# tc08-6u.net
KiCad netlist of a schematic drawn in EAGLE
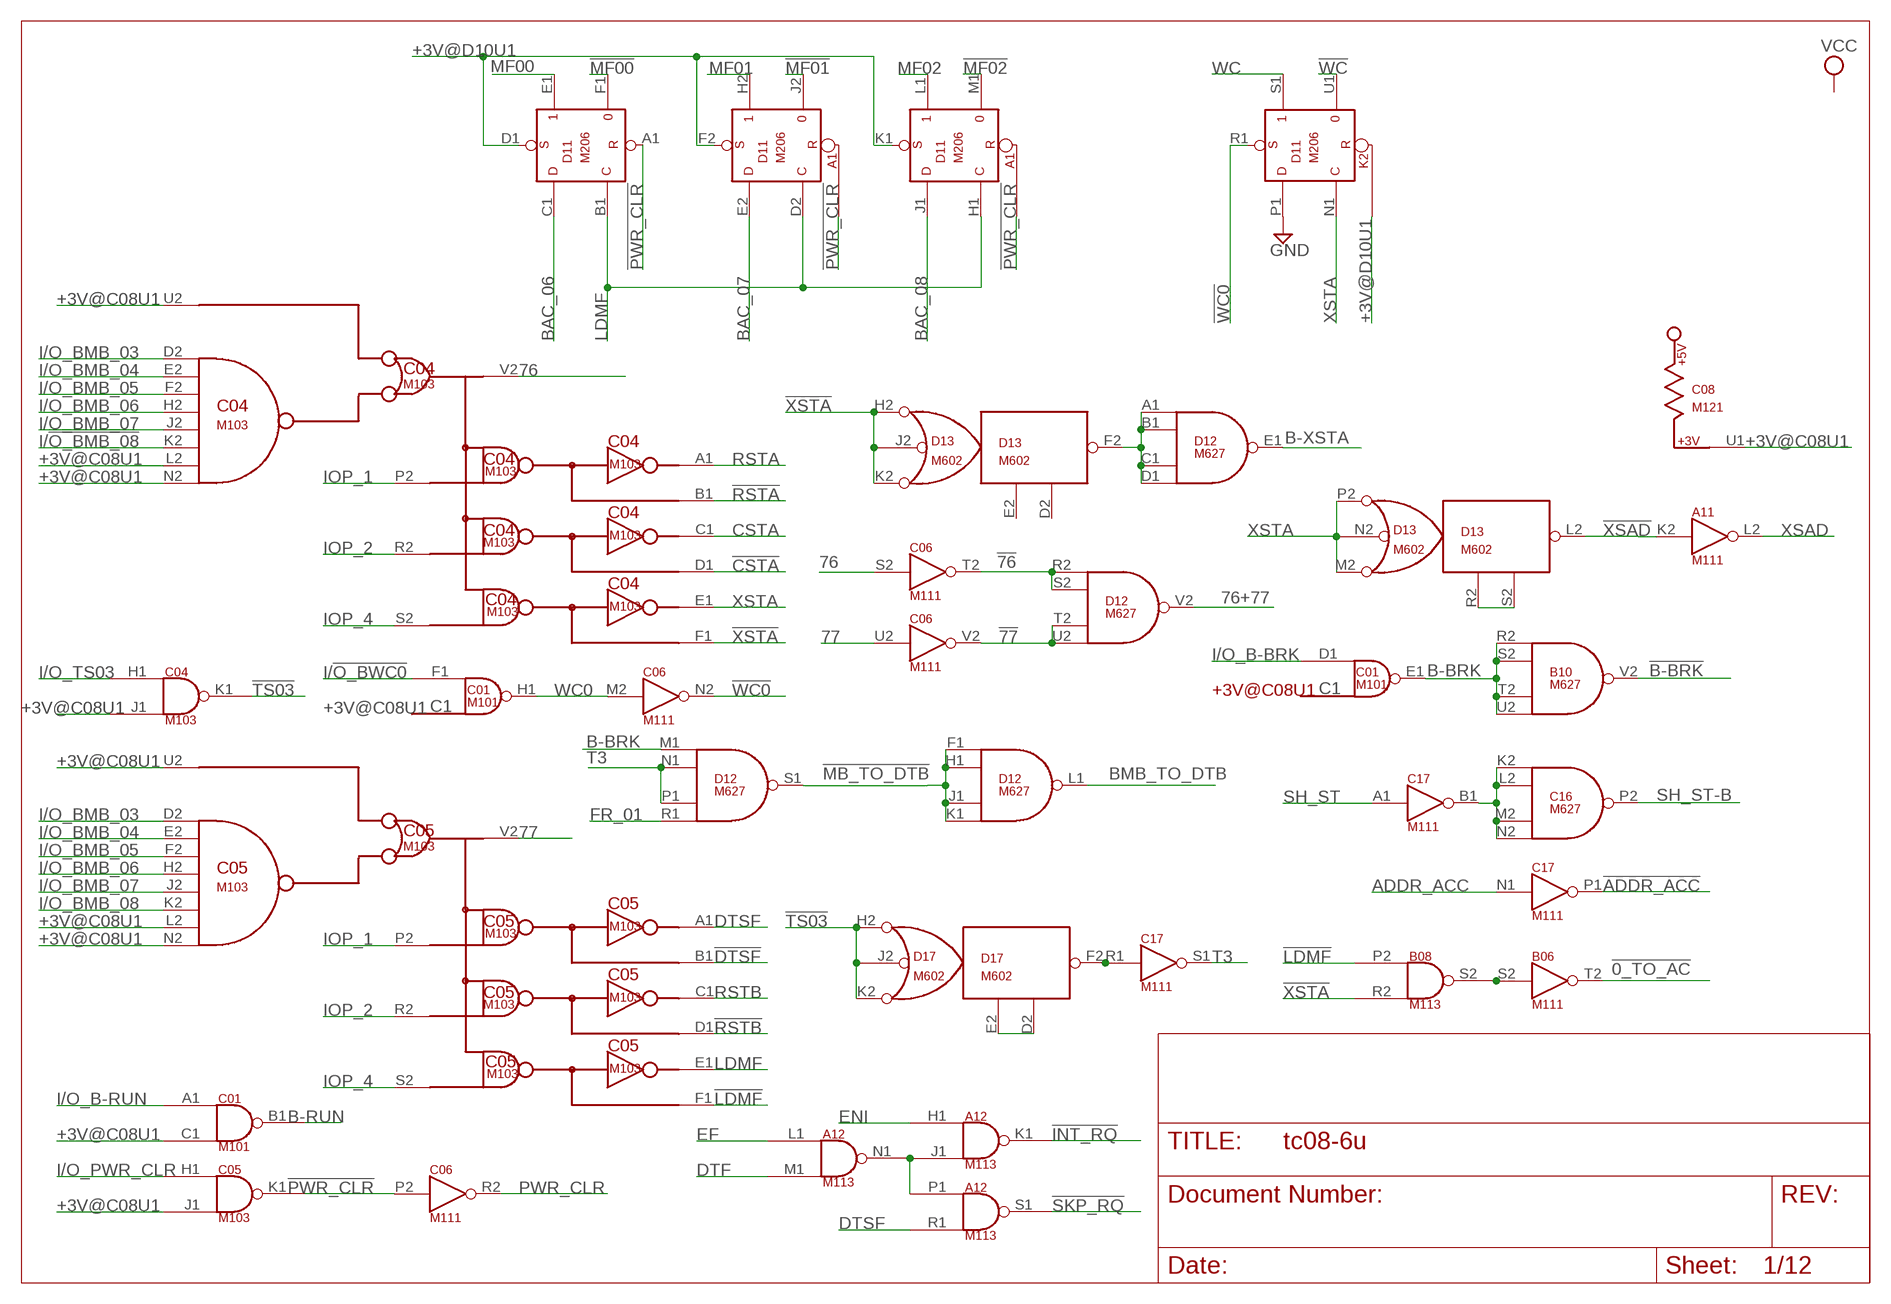
[diagram p0: schematic, sheet 1]
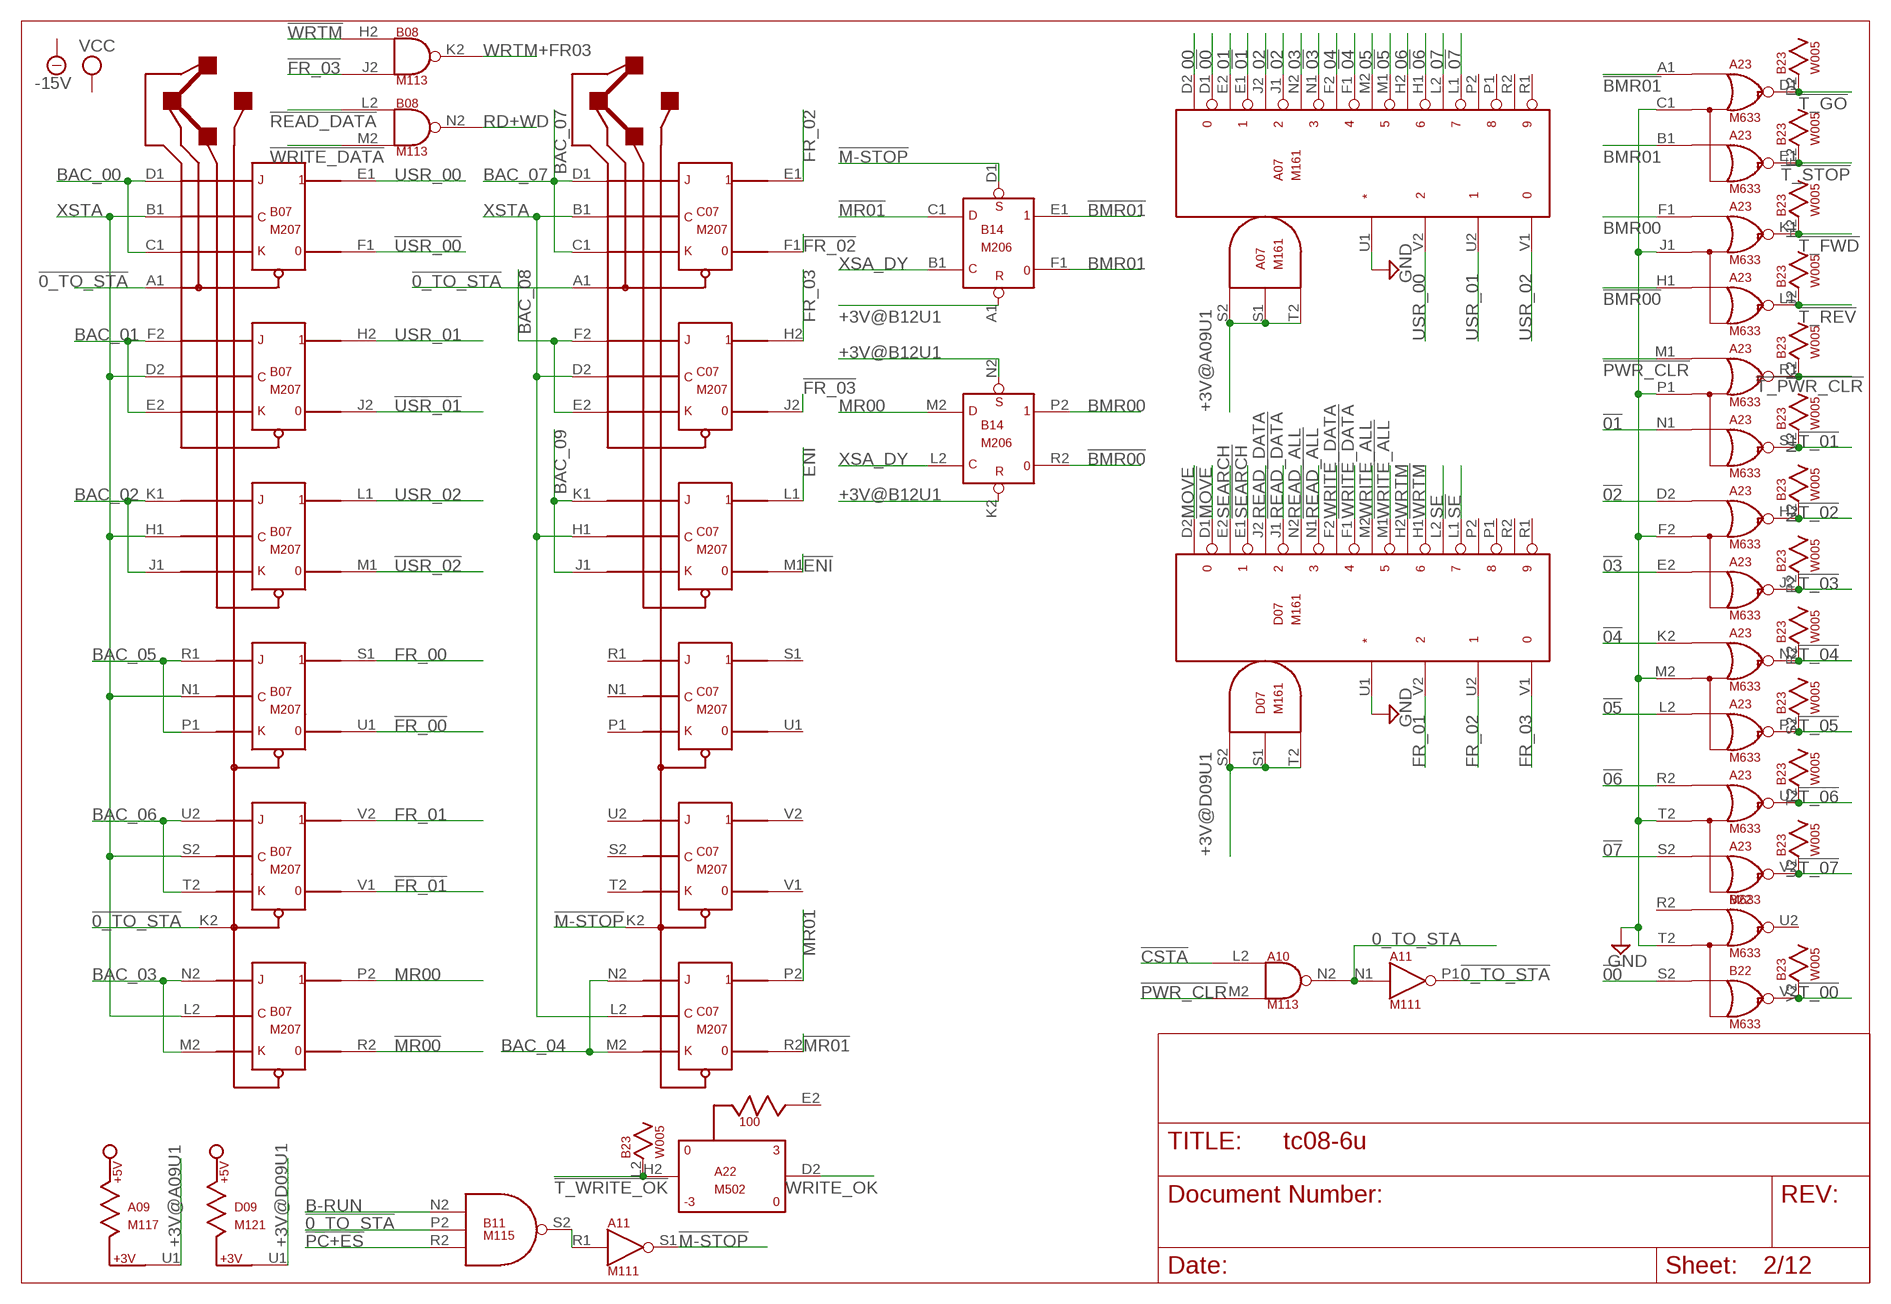
[diagram p1: schematic, sheet 2]
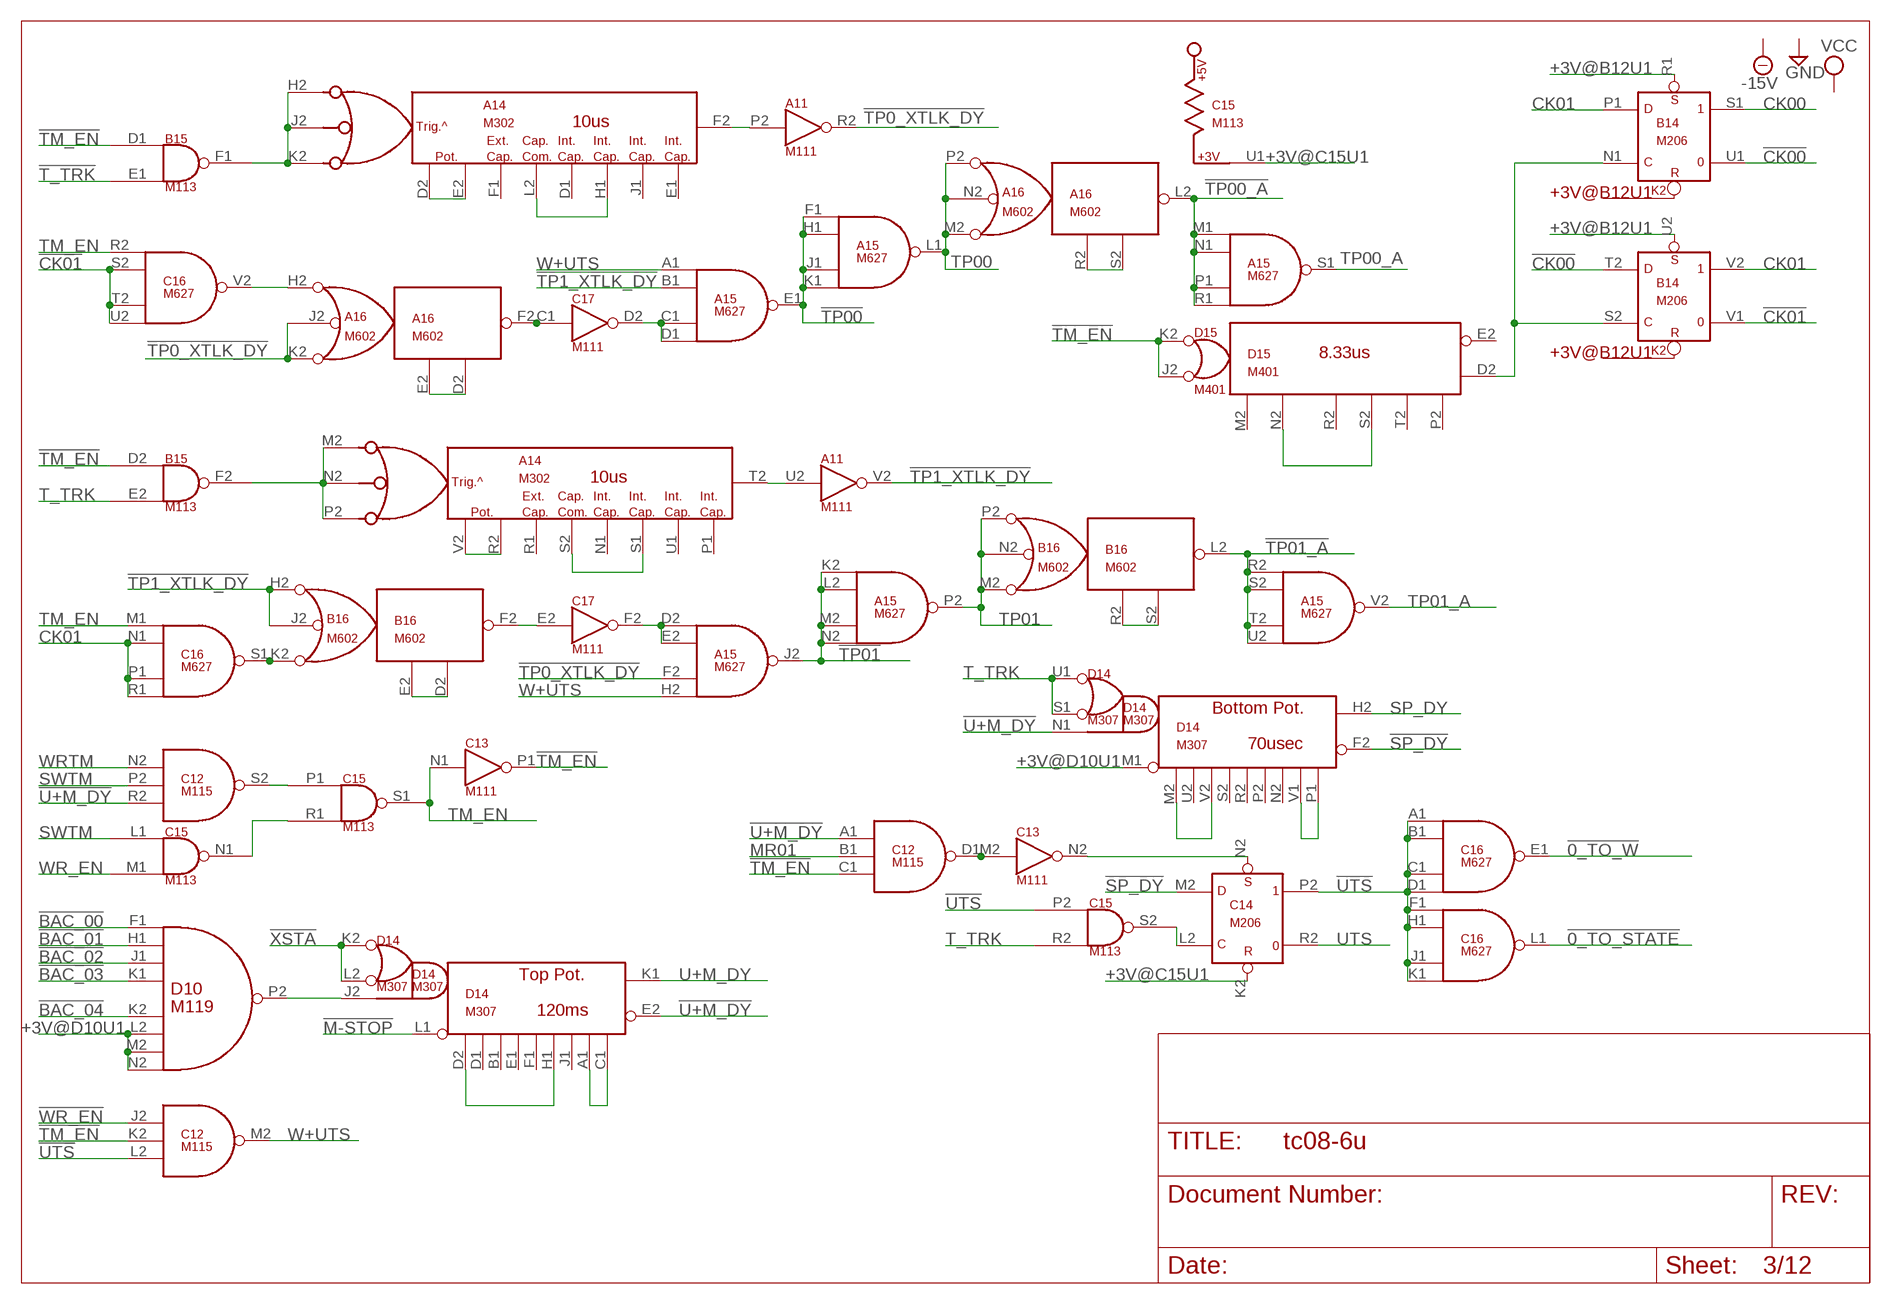
[diagram p2: schematic, sheet 3]
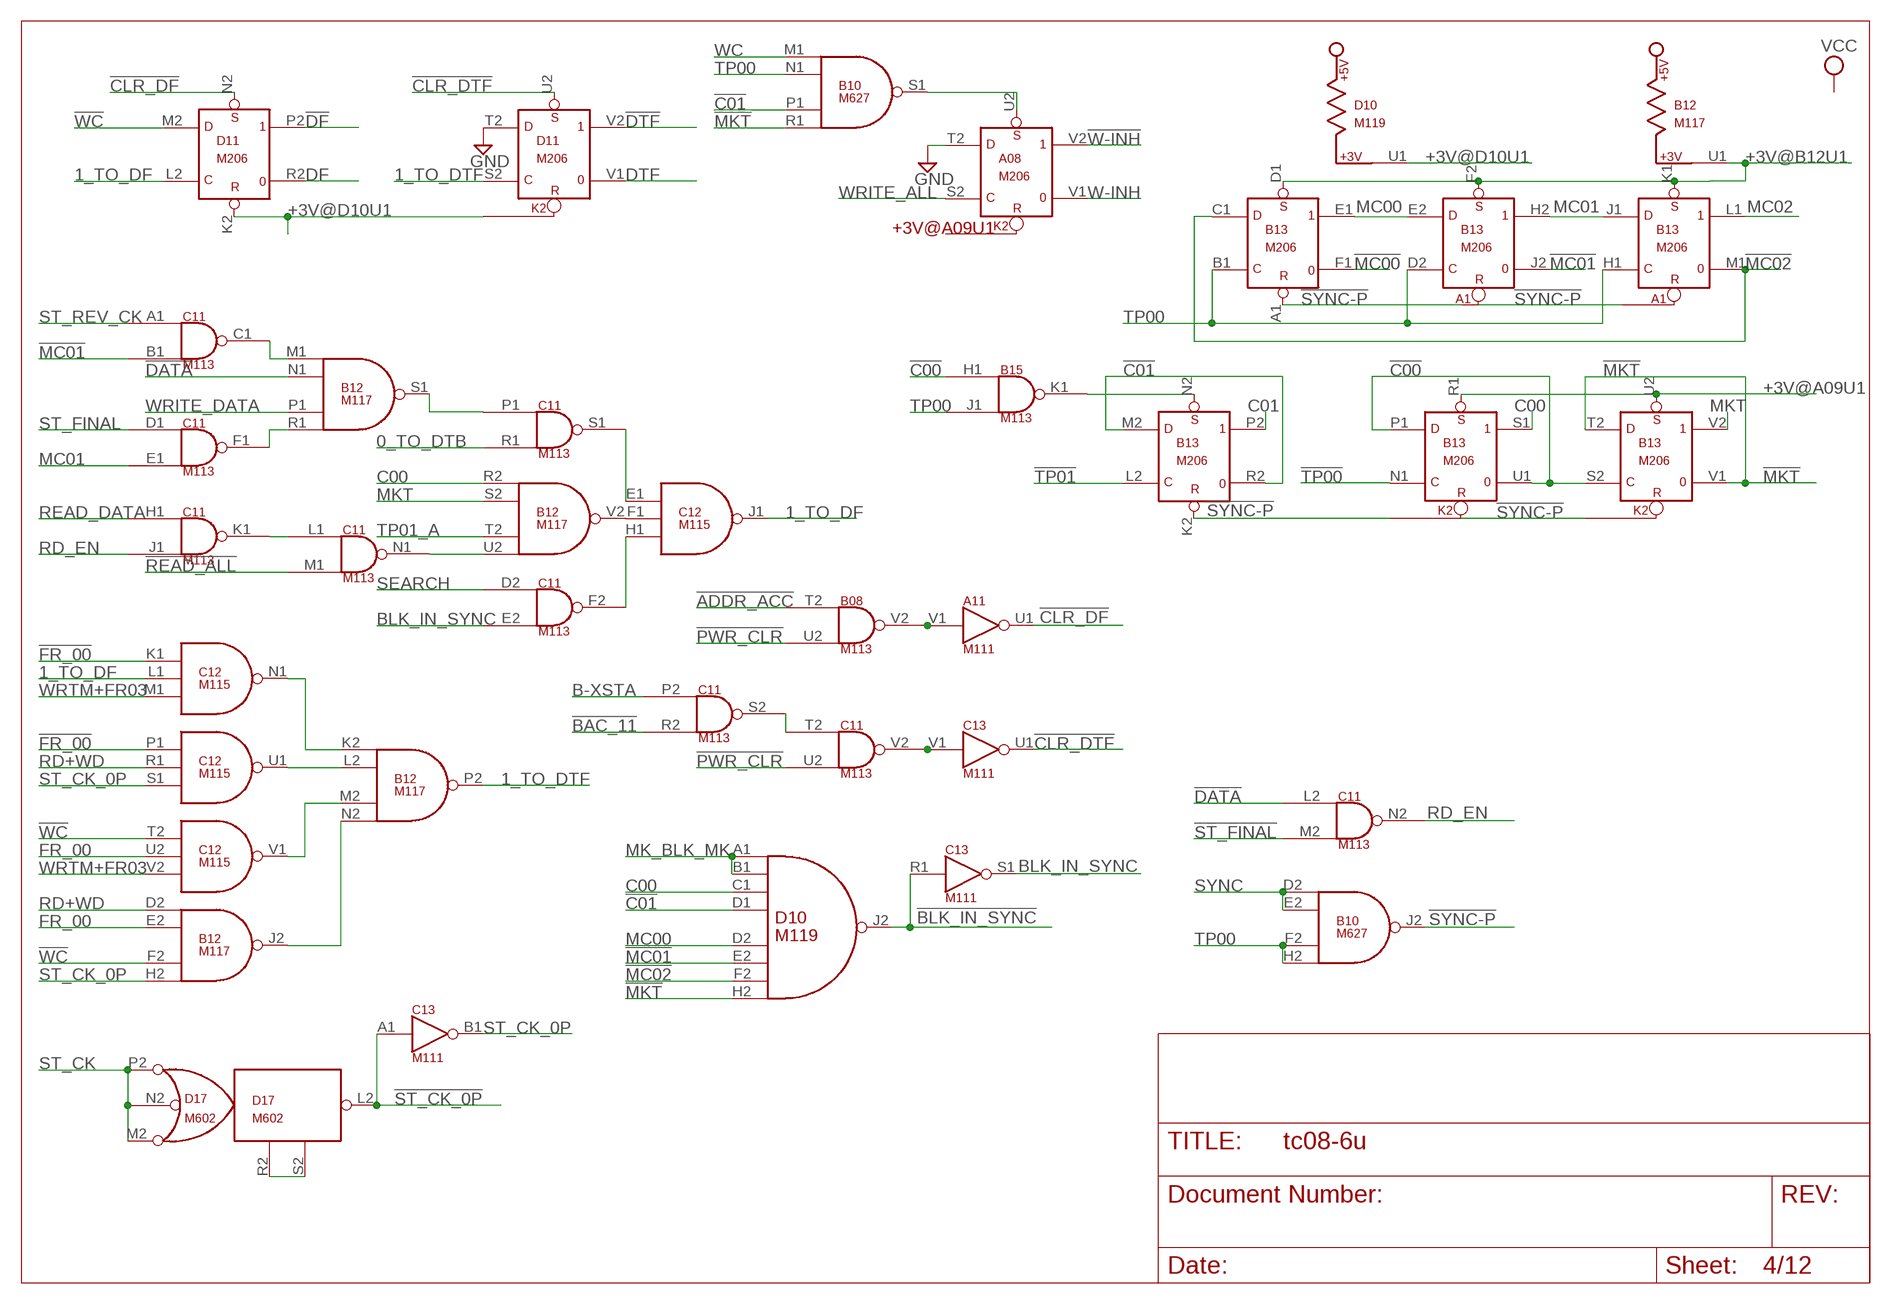
[diagram p3: schematic, sheet 4]
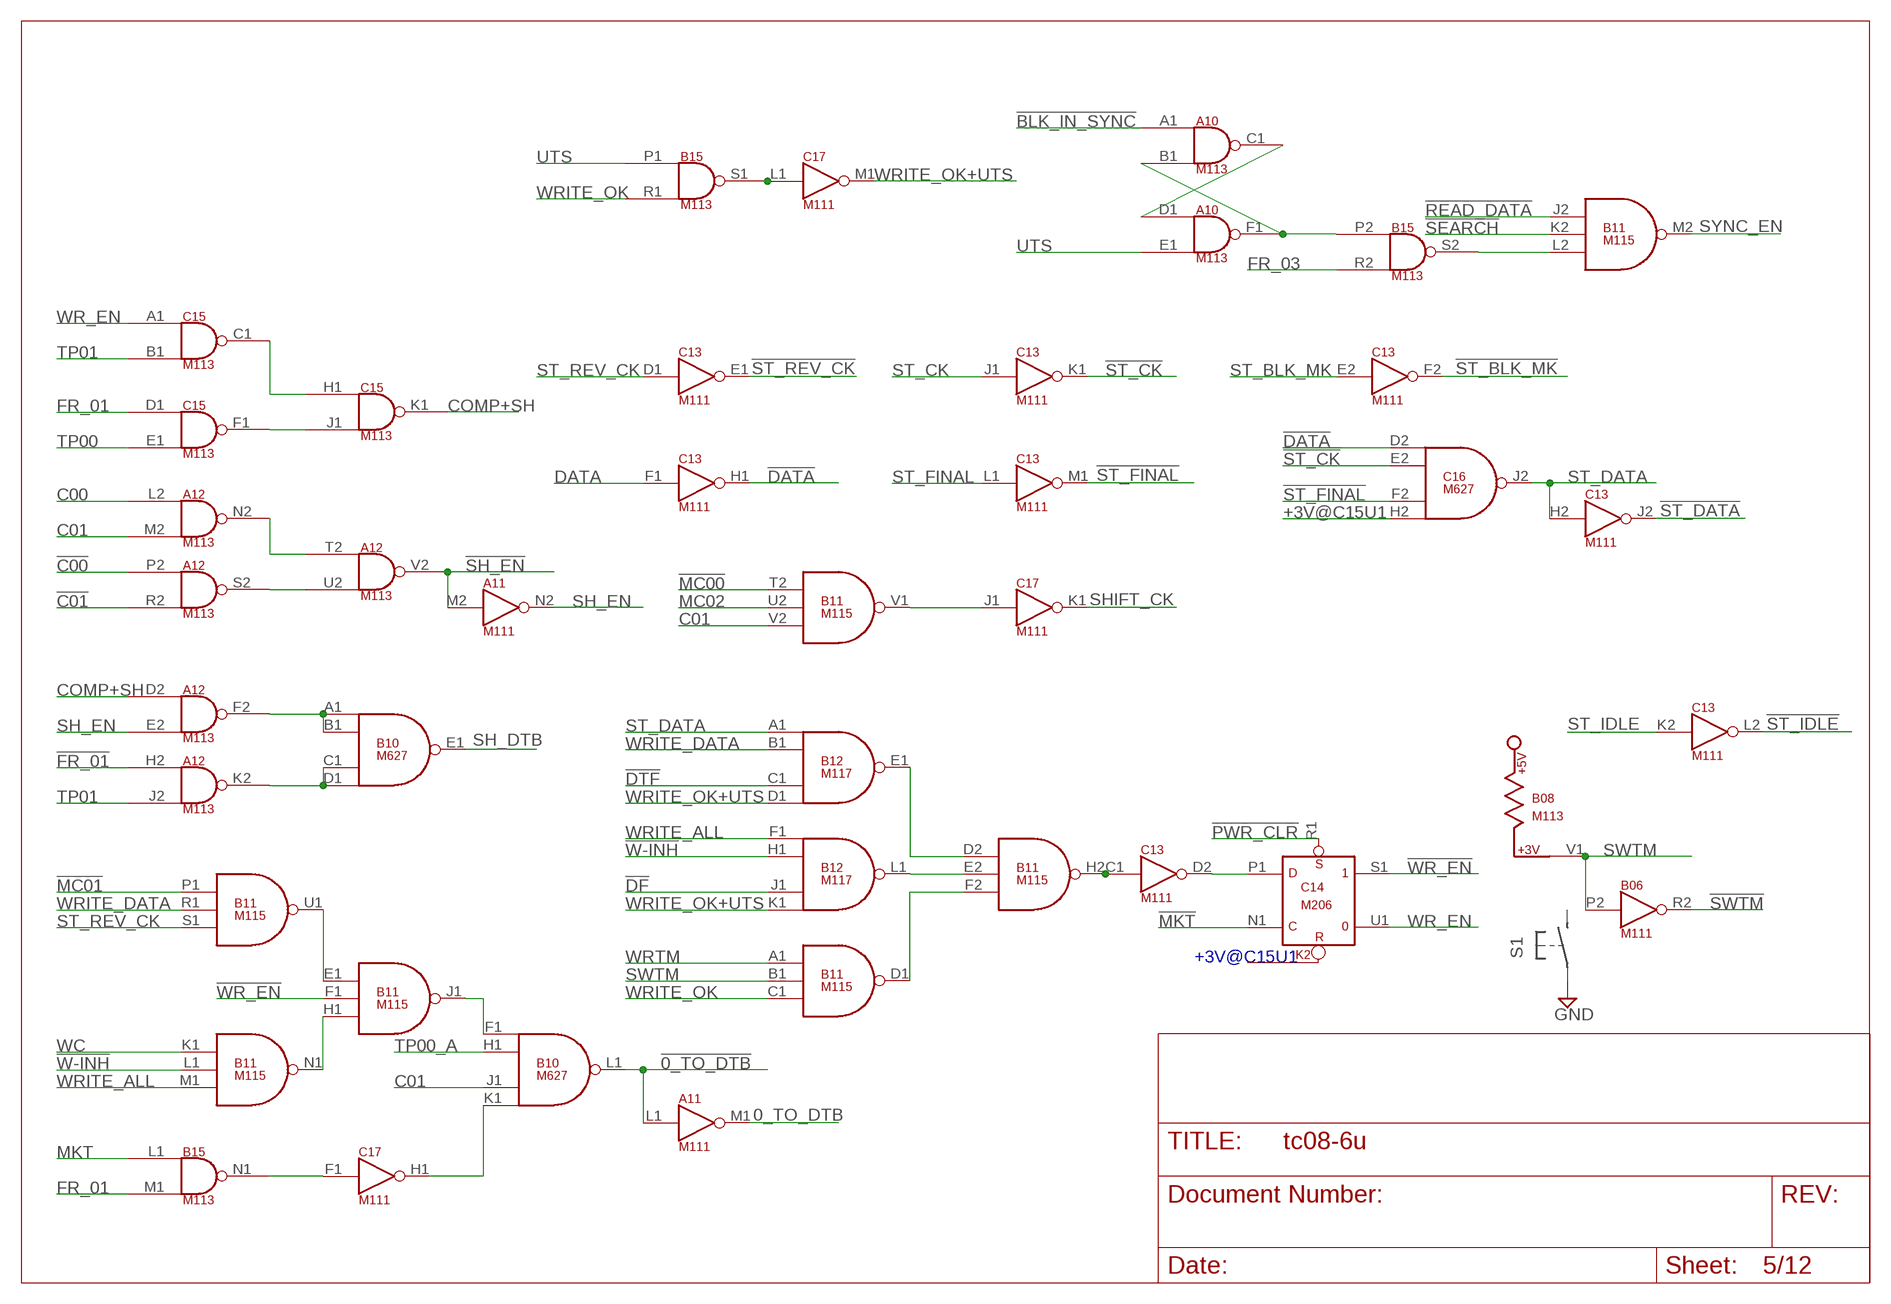
[diagram p4: schematic, sheet 5]
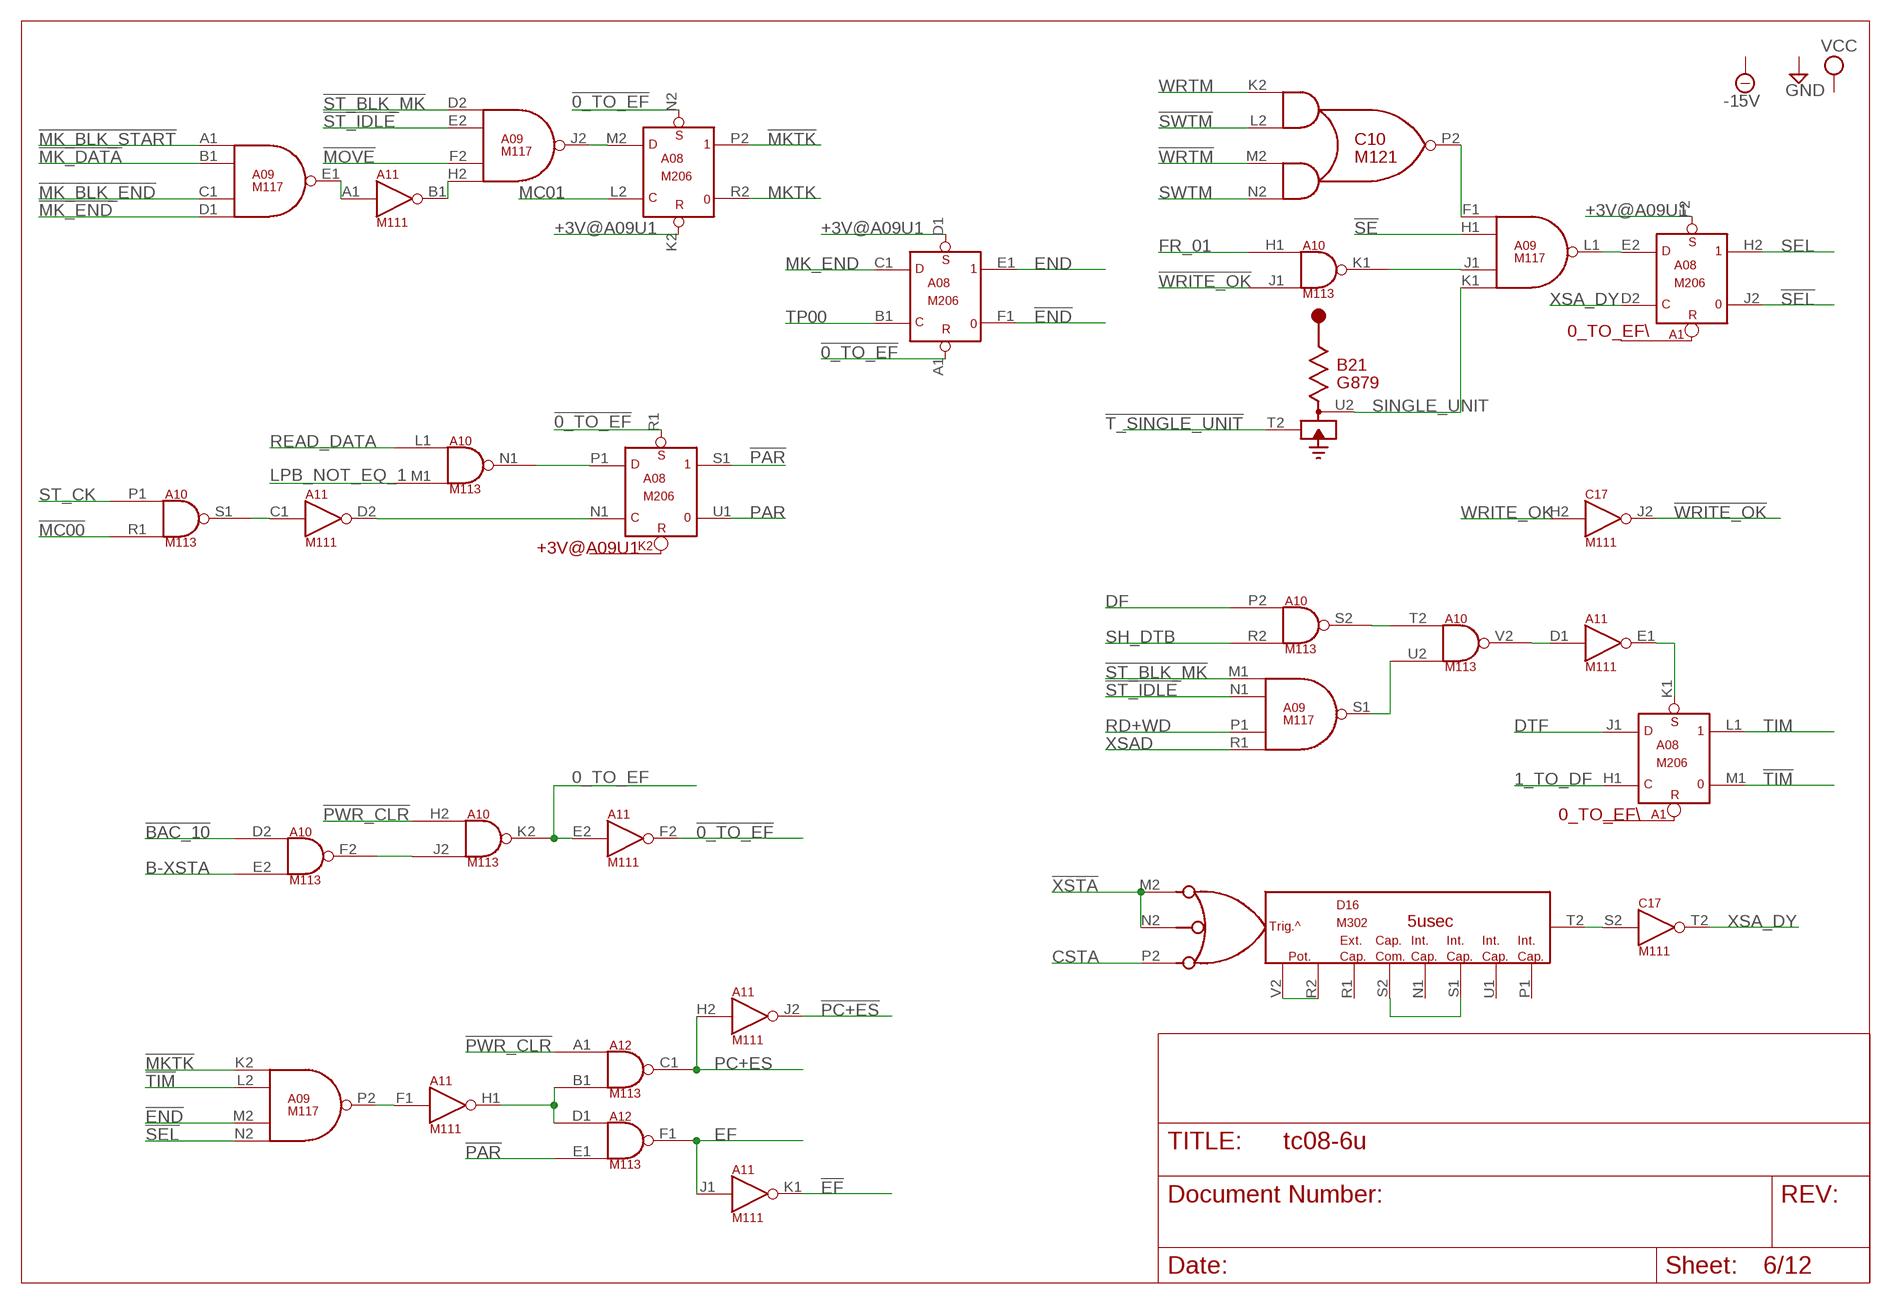
[diagram p5: schematic, sheet 6]
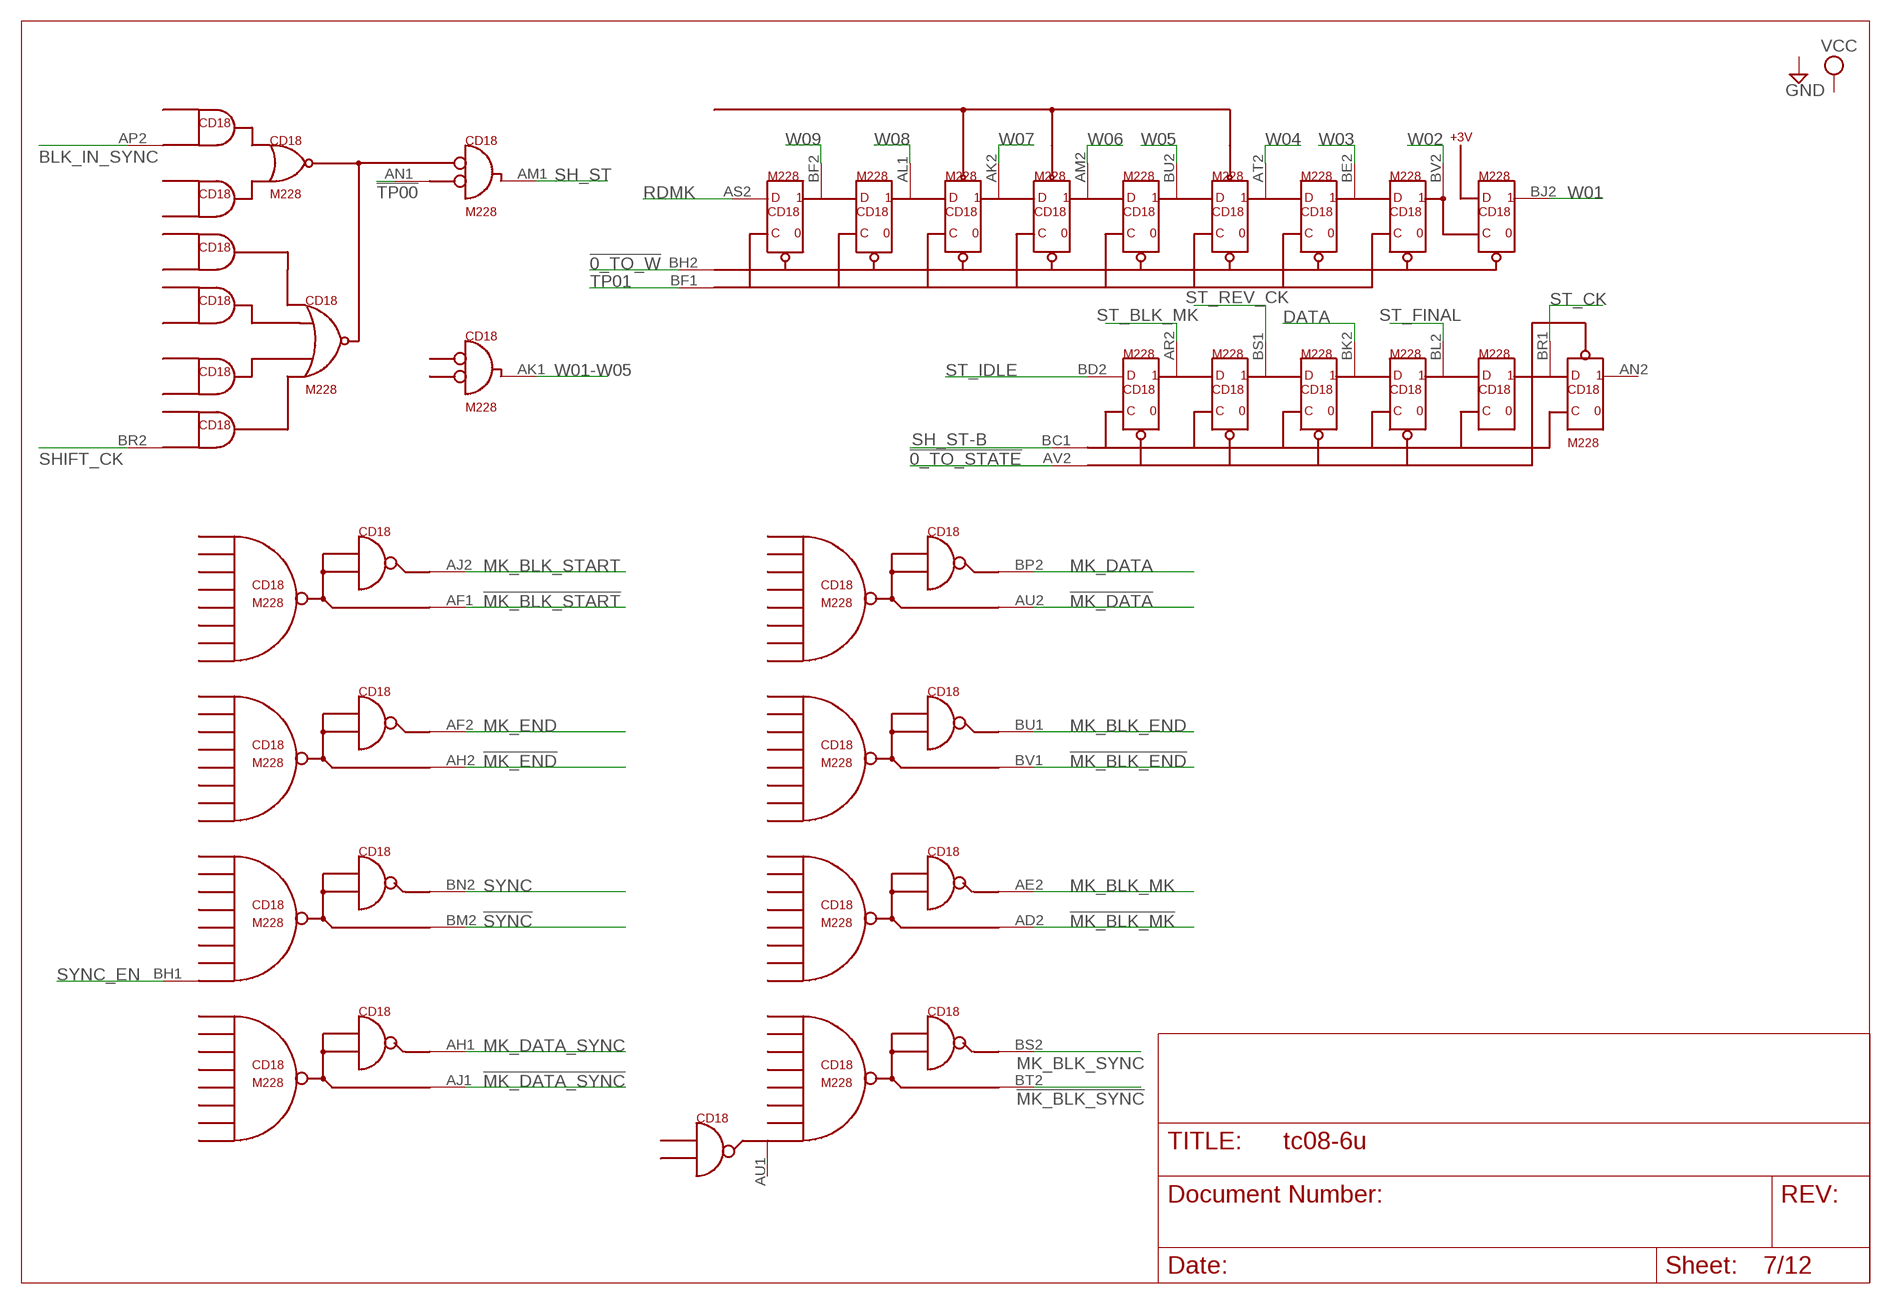
[diagram p6: schematic, sheet 7]
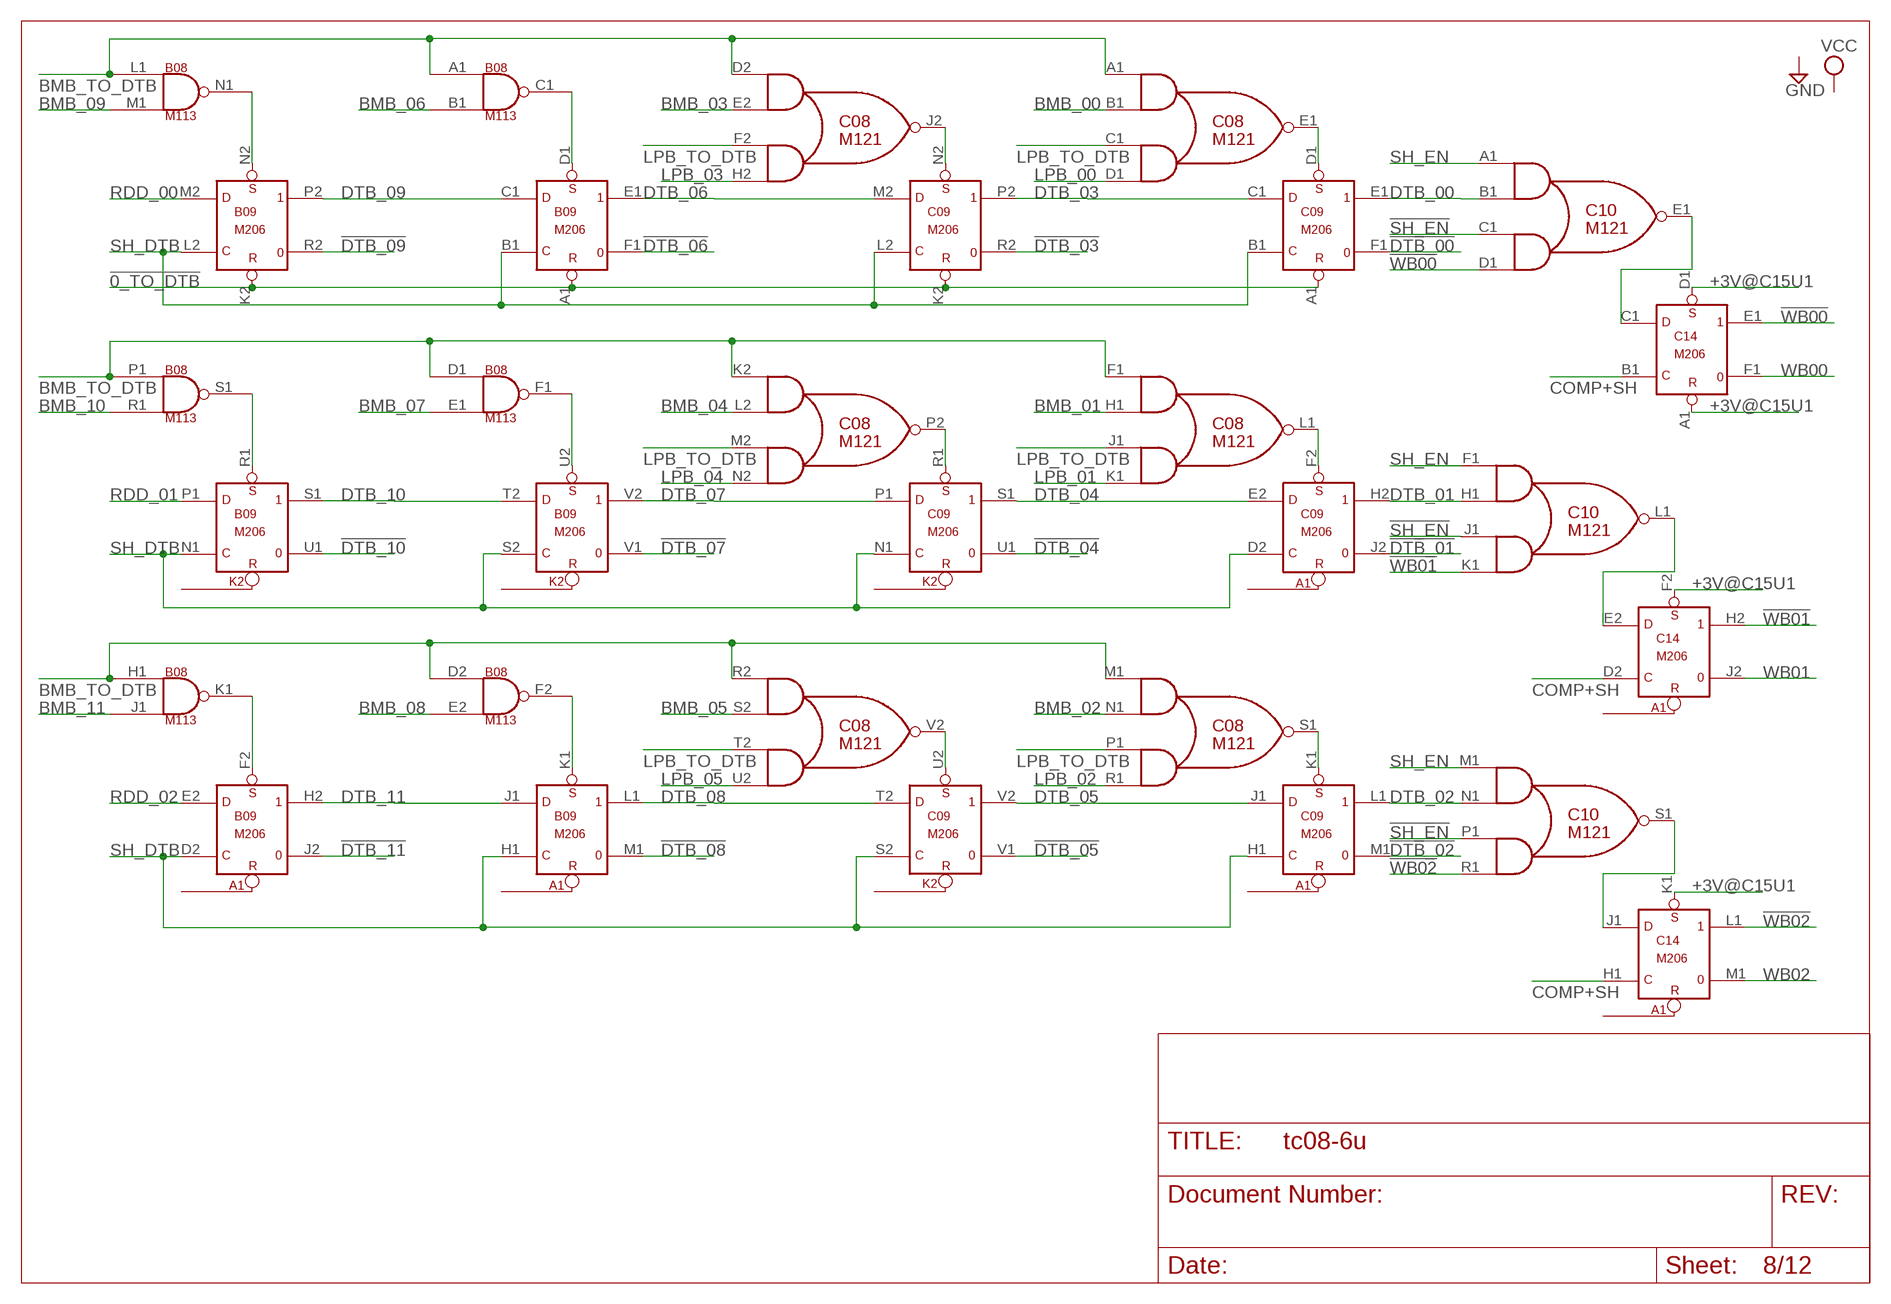
[diagram p7: schematic, sheet 8]
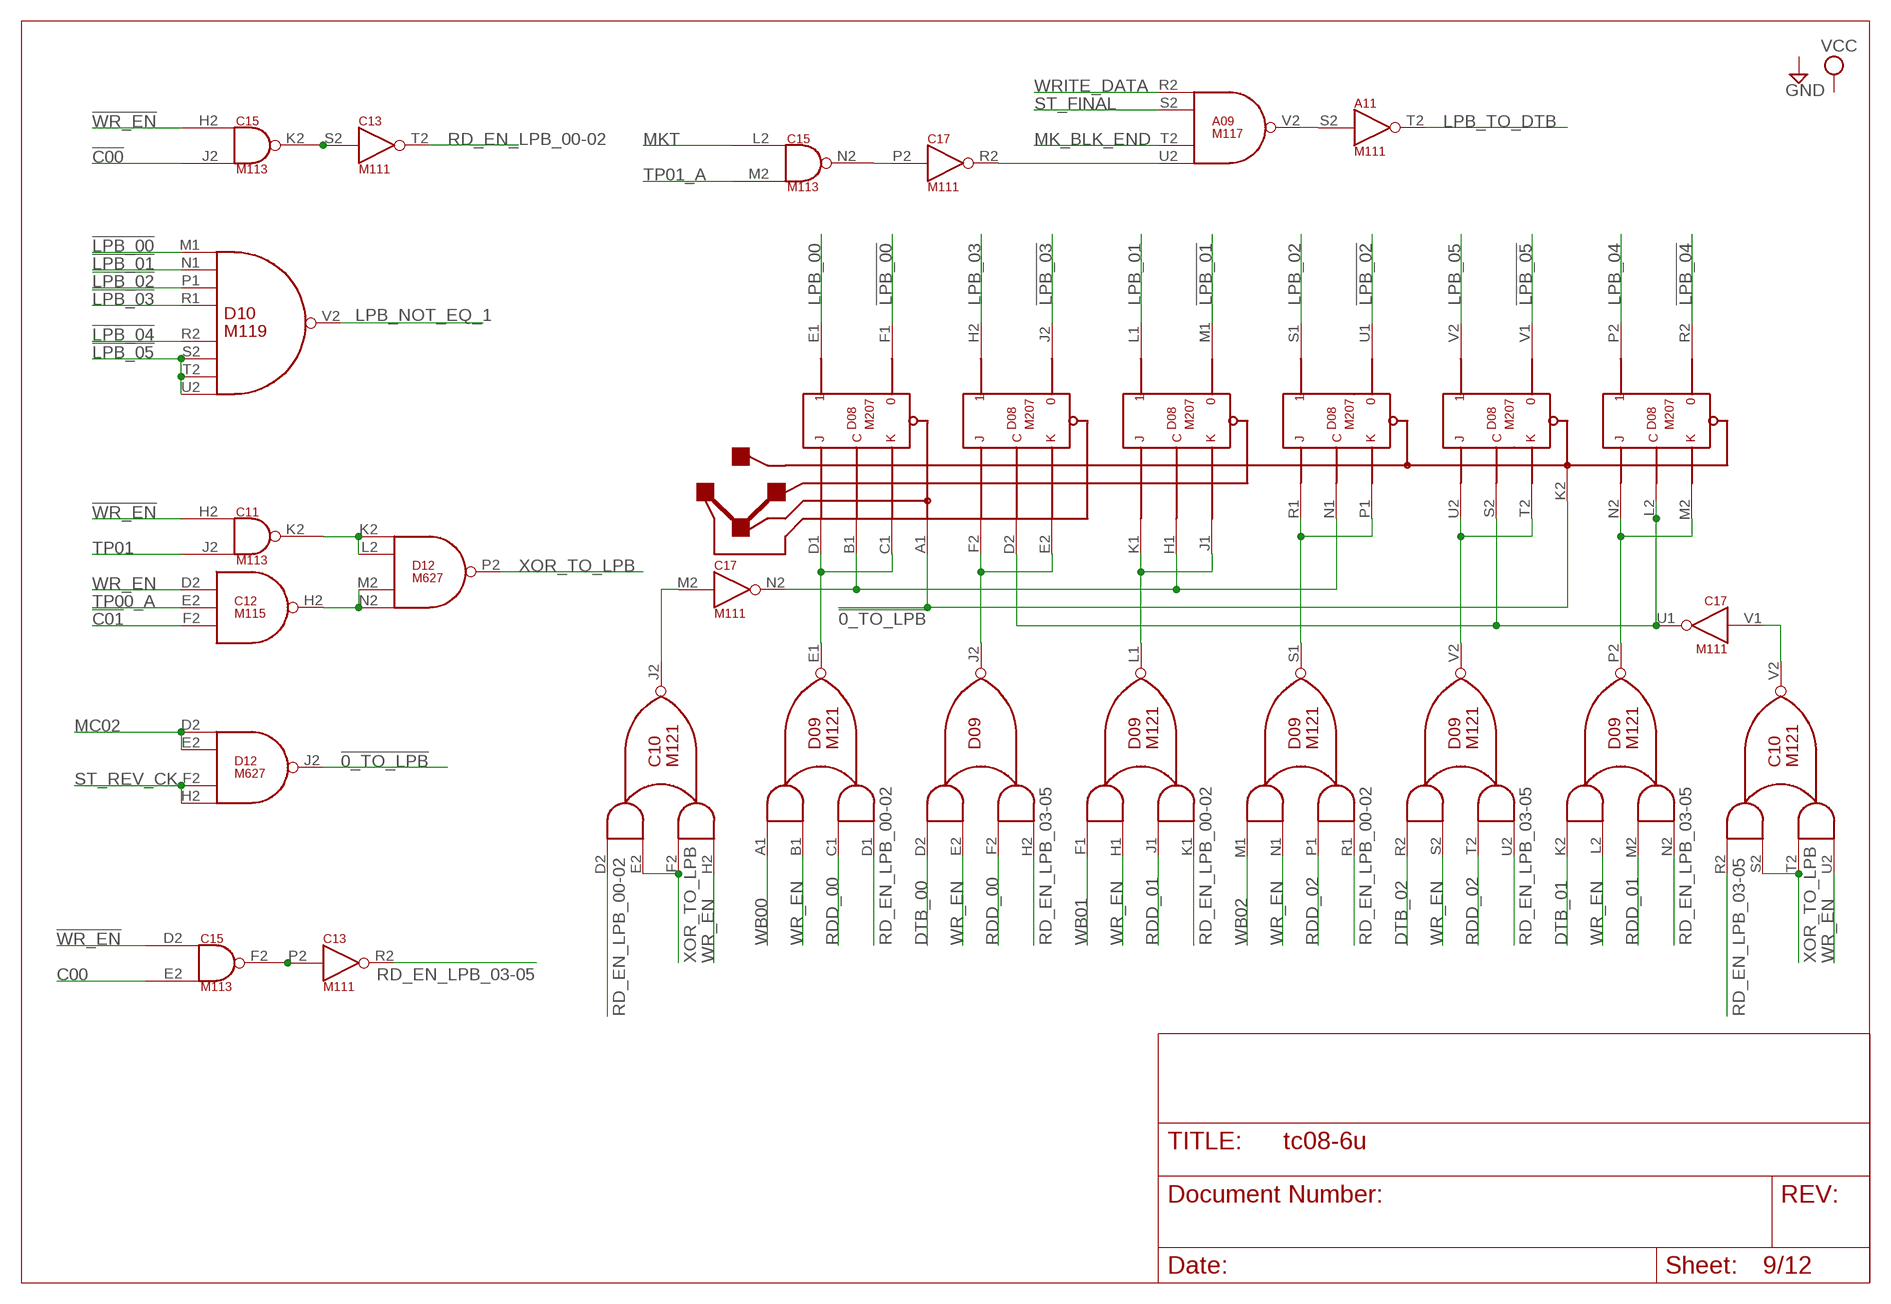
[diagram p8: schematic, sheet 9]
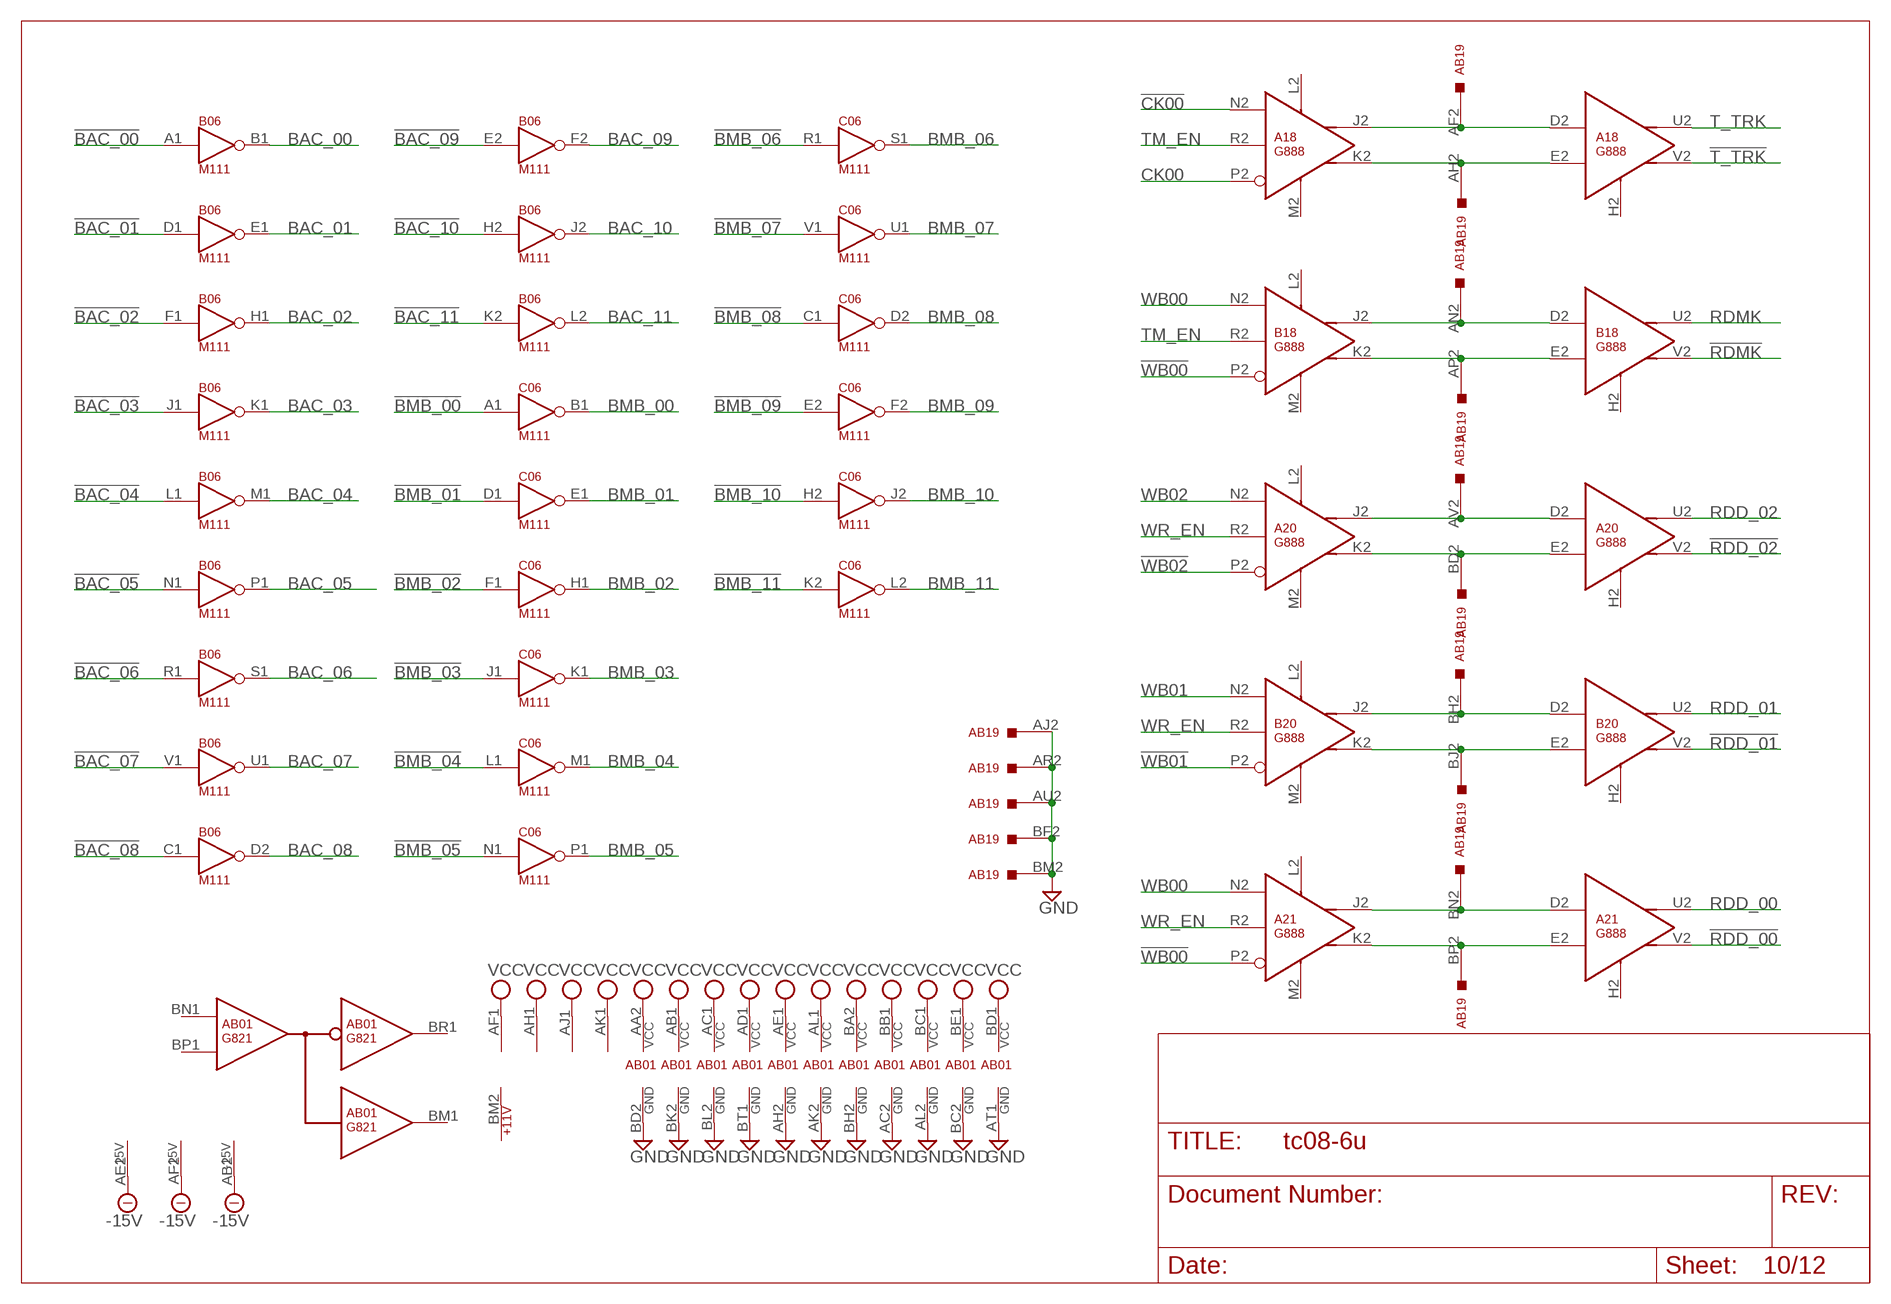
[diagram p9: schematic, sheet 10]
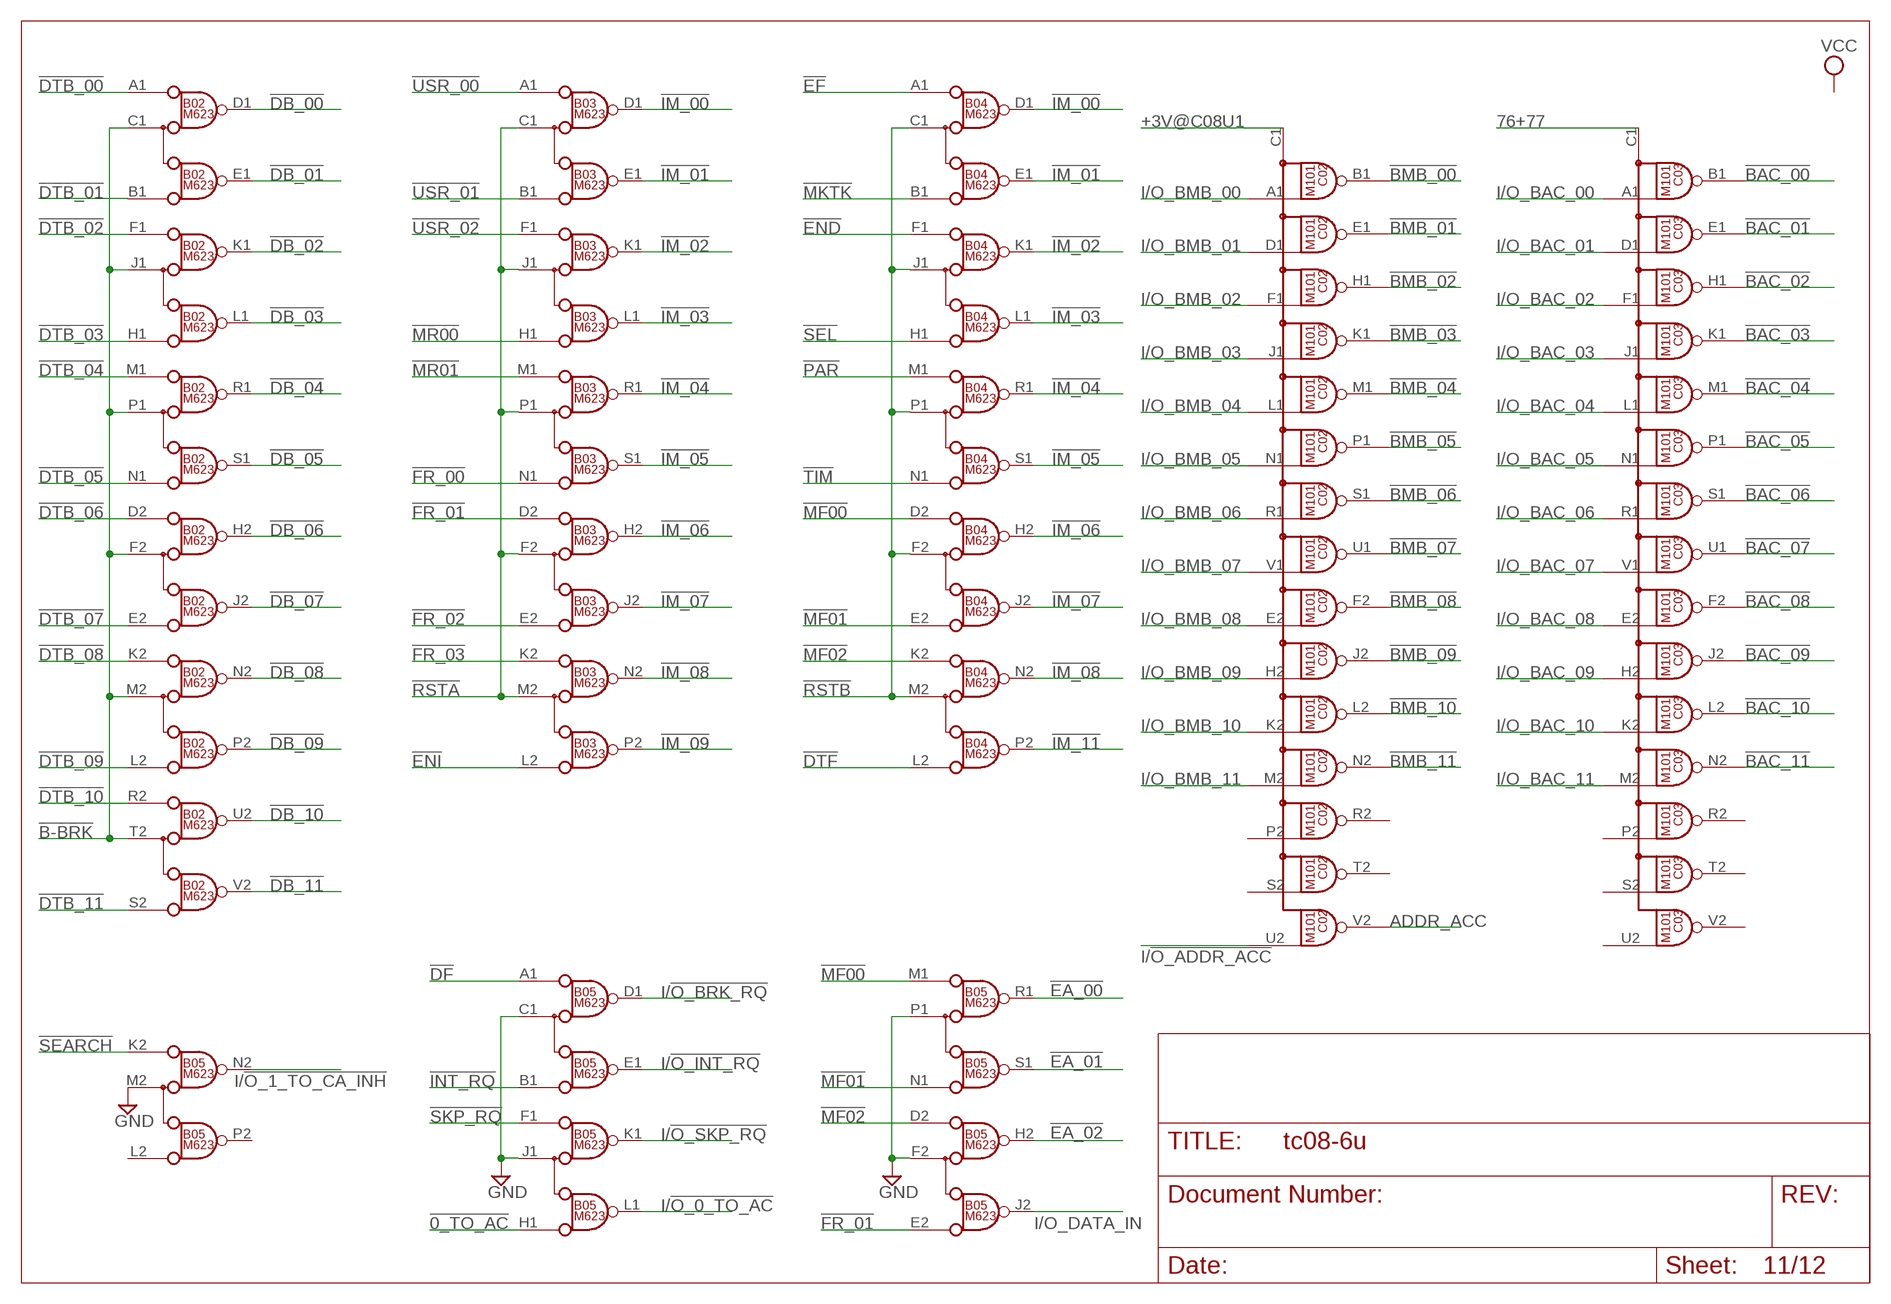
[diagram p10: schematic, sheet 11]
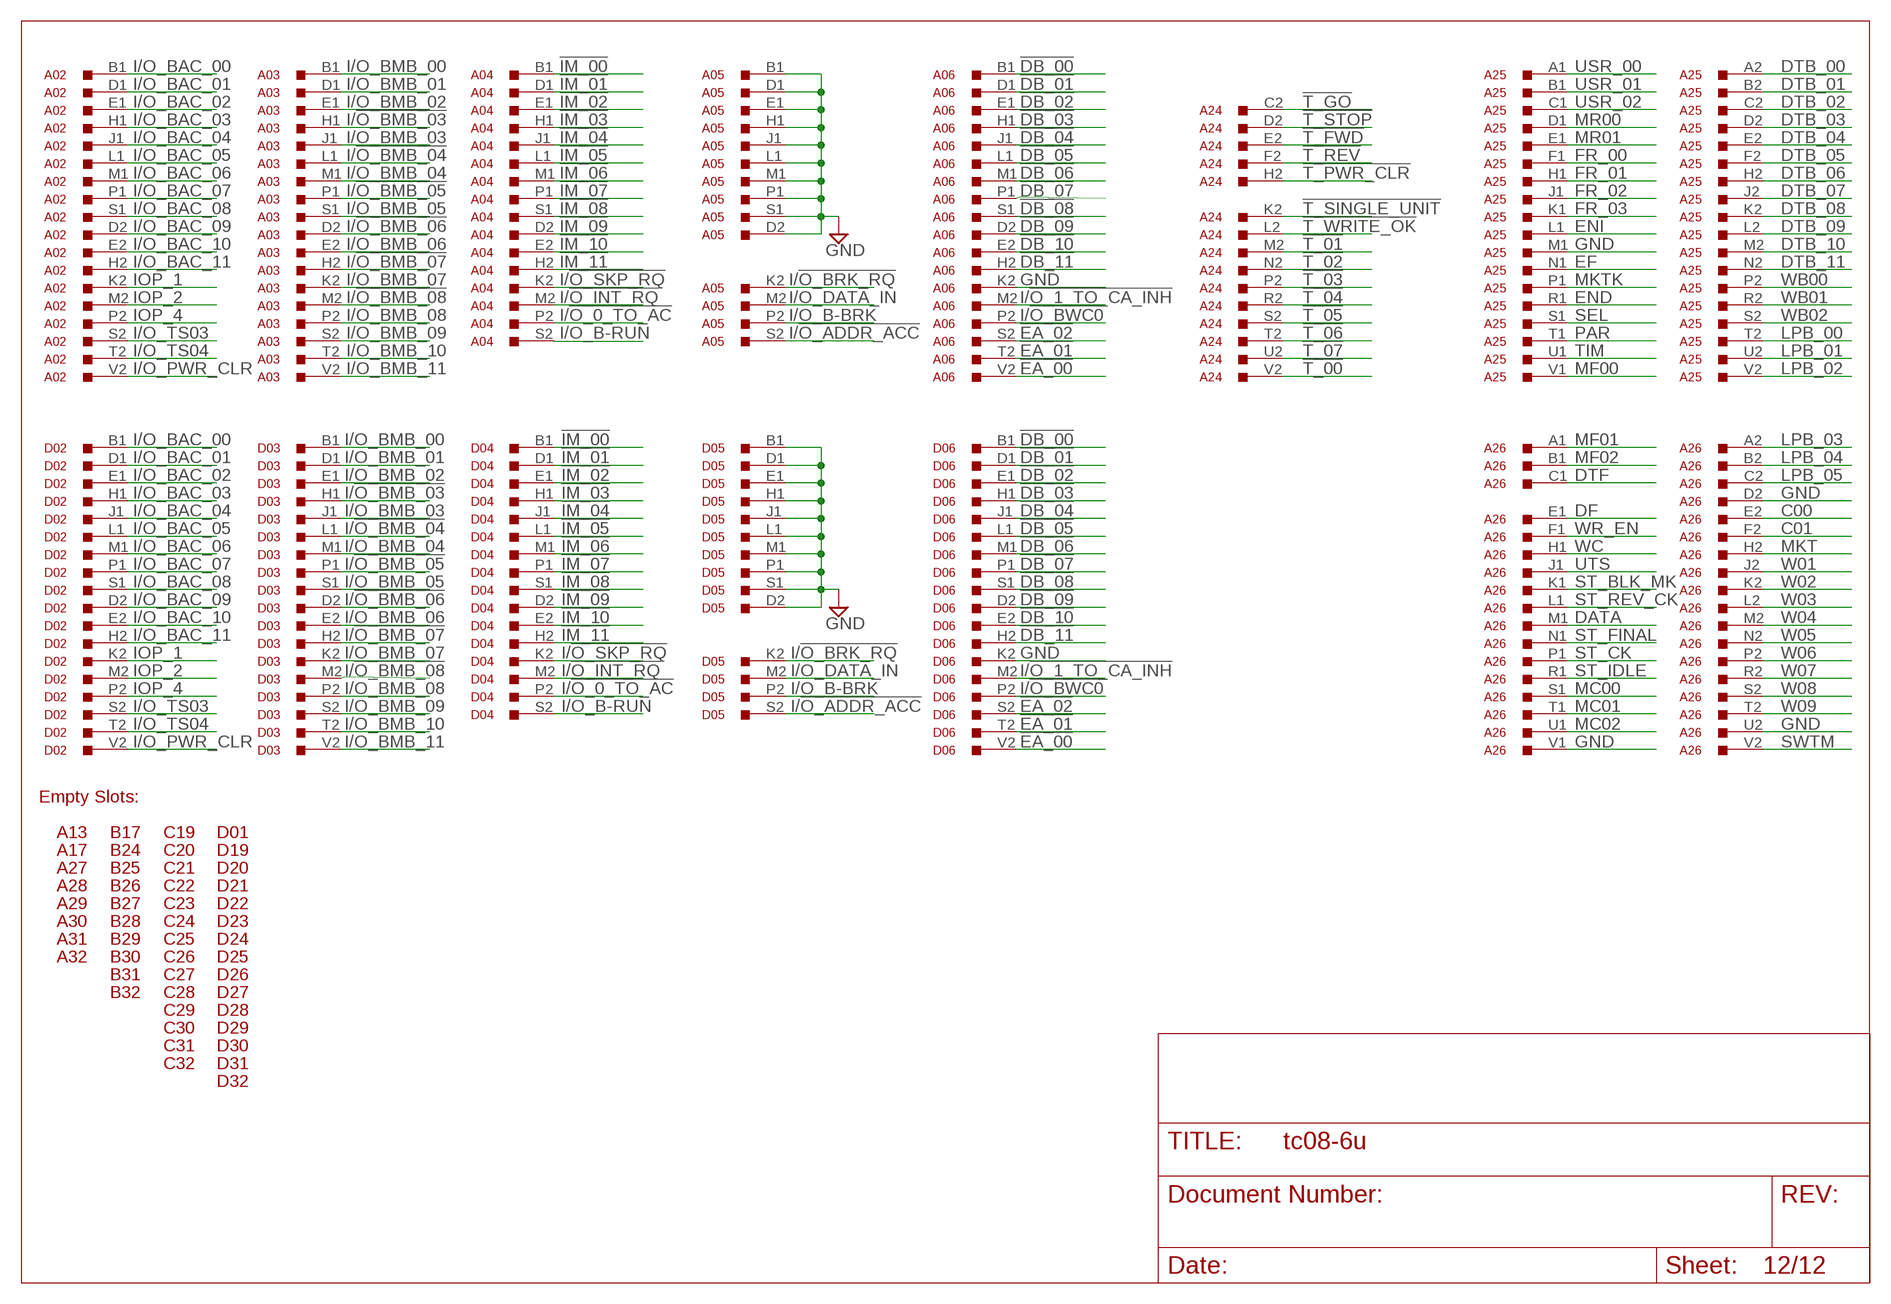
[diagram p11: schematic, sheet 12]

(export (version "E")
  (design (tool "Eeschema 10.0.6"))
  (components
    (comp (ref "A11")
      (value "M111")
      (footprint "eagle-import:H807")
      (libsource (lib "eagle-import") (part "M111"))
    )
    (comp (ref "A12")
      (value "M113")
      (footprint "eagle-import:H807")
      (libsource (lib "eagle-import") (part "M113"))
    )
    (comp (ref "B06")
      (value "M111")
      (footprint "eagle-import:H807")
      (libsource (lib "eagle-import") (part "M111"))
    )
    (comp (ref "B08")
      (value "M113")
      (footprint "eagle-import:H807")
      (libsource (lib "eagle-import") (part "M113"))
    )
    (comp (ref "B10")
      (value "M627")
      (footprint "eagle-import:H807")
      (libsource (lib "eagle-import") (part "M627"))
    )
    (comp (ref "C01")
      (value "M101")
      (footprint "eagle-import:H807")
      (libsource (lib "eagle-import") (part "M101"))
    )
    (comp (ref "C04")
      (value "M103")
      (footprint "eagle-import:H807")
      (libsource (lib "eagle-import") (part "M103"))
    )
    (comp (ref "C05")
      (value "M103")
      (footprint "eagle-import:H807")
      (libsource (lib "eagle-import") (part "M103"))
    )
    (comp (ref "C06")
      (value "M111")
      (footprint "eagle-import:H807")
      (libsource (lib "eagle-import") (part "M111"))
    )
    (comp (ref "C08")
      (value "M121")
      (footprint "eagle-import:H807")
      (libsource (lib "eagle-import") (part "M121"))
    )
    (comp (ref "C16")
      (value "M627")
      (footprint "eagle-import:H807")
      (libsource (lib "eagle-import") (part "M627"))
    )
    (comp (ref "C17")
      (value "M111")
      (footprint "eagle-import:H807")
      (libsource (lib "eagle-import") (part "M111"))
    )
    (comp (ref "D11")
      (value "M206")
      (footprint "eagle-import:H807")
      (libsource (lib "eagle-import") (part "M206X"))
    )
    (comp (ref "D12")
      (value "M627")
      (footprint "eagle-import:H807")
      (libsource (lib "eagle-import") (part "M627"))
    )
    (comp (ref "D13")
      (value "M602")
      (footprint "eagle-import:H807")
      (libsource (lib "eagle-import") (part "M602"))
    )
    (comp (ref "D17")
      (value "M602")
      (footprint "eagle-import:H807")
      (libsource (lib "eagle-import") (part "M602"))
    )
    (comp (ref "A14")
      (value "M302")
      (footprint "eagle-import:H807")
      (libsource (lib "eagle-import") (part "M302"))
    )
    (comp (ref "A15")
      (value "M627")
      (footprint "eagle-import:H807")
      (libsource (lib "eagle-import") (part "M627"))
    )
    (comp (ref "A16")
      (value "M602")
      (footprint "eagle-import:H807")
      (libsource (lib "eagle-import") (part "M602"))
    )
    (comp (ref "B14")
      (value "M206")
      (footprint "eagle-import:H807")
      (libsource (lib "eagle-import") (part "M206X"))
    )
    (comp (ref "B15")
      (value "M113")
      (footprint "eagle-import:H807")
      (libsource (lib "eagle-import") (part "M113"))
    )
    (comp (ref "B16")
      (value "M602")
      (footprint "eagle-import:H807")
      (libsource (lib "eagle-import") (part "M602"))
    )
    (comp (ref "C12")
      (value "M115")
      (footprint "eagle-import:H807")
      (libsource (lib "eagle-import") (part "M115"))
    )
    (comp (ref "C13")
      (value "M111")
      (footprint "eagle-import:H807")
      (libsource (lib "eagle-import") (part "M111"))
    )
    (comp (ref "C14")
      (value "M206")
      (footprint "eagle-import:H807")
      (libsource (lib "eagle-import") (part "M206X"))
    )
    (comp (ref "C15")
      (value "M113")
      (footprint "eagle-import:H807")
      (libsource (lib "eagle-import") (part "M113"))
    )
    (comp (ref "D10")
      (value "M119")
      (footprint "eagle-import:H807")
      (libsource (lib "eagle-import") (part "M119"))
    )
    (comp (ref "D14")
      (value "M307")
      (footprint "eagle-import:H807")
      (libsource (lib "eagle-import") (part "M307"))
    )
    (comp (ref "D15")
      (value "M401")
      (footprint "eagle-import:H807")
      (libsource (lib "eagle-import") (part "M401"))
    )
    (comp (ref "B09")
      (value "M206")
      (footprint "eagle-import:H807")
      (libsource (lib "eagle-import") (part "M206X"))
    )
    (comp (ref "C09")
      (value "M206")
      (footprint "eagle-import:H807")
      (libsource (lib "eagle-import") (part "M206X"))
    )
    (comp (ref "C10")
      (value "M121")
      (footprint "eagle-import:H807")
      (libsource (lib "eagle-import") (part "M121"))
    )
    (comp (ref "A10")
      (value "M113")
      (footprint "eagle-import:H807")
      (libsource (lib "eagle-import") (part "M113"))
    )
    (comp (ref "B11")
      (value "M115")
      (footprint "eagle-import:H807")
      (libsource (lib "eagle-import") (part "M115"))
    )
    (comp (ref "B12")
      (value "M117")
      (footprint "eagle-import:H807")
      (libsource (lib "eagle-import") (part "M117"))
    )
    (comp (ref "A08")
      (value "M206")
      (footprint "eagle-import:H807")
      (libsource (lib "eagle-import") (part "M206X"))
    )
    (comp (ref "A09")
      (value "M117")
      (footprint "eagle-import:H807")
      (libsource (lib "eagle-import") (part "M117"))
    )
    (comp (ref "B21")
      (value "G879")
      (footprint "eagle-import:H807")
      (libsource (lib "eagle-import") (part "G879"))
    )
    (comp (ref "D16")
      (value "M302")
      (footprint "eagle-import:H807")
      (libsource (lib "eagle-import") (part "M302"))
    )
    (comp (ref "A02")
      (value "M903")
      (footprint "eagle-import:H807")
      (libsource (lib "eagle-import") (part "M903"))
    )
    (comp (ref "A03")
      (value "M903")
      (footprint "eagle-import:H807")
      (libsource (lib "eagle-import") (part "M903"))
    )
    (comp (ref "A04")
      (value "M903")
      (footprint "eagle-import:H807")
      (libsource (lib "eagle-import") (part "M903"))
    )
    (comp (ref "A05")
      (value "M903")
      (footprint "eagle-import:H807")
      (libsource (lib "eagle-import") (part "M903"))
    )
    (comp (ref "A06")
      (value "M903")
      (footprint "eagle-import:H807")
      (libsource (lib "eagle-import") (part "M903"))
    )
    (comp (ref "A13")
      (value "H807")
      (footprint "eagle-import:H807")
      (libsource (lib "eagle-import") (part "H807"))
    )
    (comp (ref "A17")
      (value "H807")
      (footprint "eagle-import:H807")
      (libsource (lib "eagle-import") (part "H807"))
    )
    (comp (ref "A24")
      (value "W023")
      (footprint "eagle-import:H807")
      (libsource (lib "eagle-import") (part "W023"))
    )
    (comp (ref "A25")
      (value "M916")
      (footprint "eagle-import:H807")
      (libsource (lib "eagle-import") (part "M916"))
    )
    (comp (ref "A26")
      (value "M916")
      (footprint "eagle-import:H807")
      (libsource (lib "eagle-import") (part "M916"))
    )
    (comp (ref "A27")
      (value "H807")
      (footprint "eagle-import:H807")
      (libsource (lib "eagle-import") (part "H807"))
    )
    (comp (ref "A28")
      (value "H807")
      (footprint "eagle-import:H807")
      (libsource (lib "eagle-import") (part "H807"))
    )
    (comp (ref "A29")
      (value "H807")
      (footprint "eagle-import:H807")
      (libsource (lib "eagle-import") (part "H807"))
    )
    (comp (ref "A30")
      (value "H807")
      (footprint "eagle-import:H807")
      (libsource (lib "eagle-import") (part "H807"))
    )
    (comp (ref "A31")
      (value "H807")
      (footprint "eagle-import:H807")
      (libsource (lib "eagle-import") (part "H807"))
    )
    (comp (ref "A32")
      (value "H807")
      (footprint "eagle-import:H807")
      (libsource (lib "eagle-import") (part "H807"))
    )
    (comp (ref "B17")
      (value "H807")
      (footprint "eagle-import:H807")
      (libsource (lib "eagle-import") (part "H807"))
    )
    (comp (ref "B24")
      (value "H807")
      (footprint "eagle-import:H807")
      (libsource (lib "eagle-import") (part "H807"))
    )
    (comp (ref "B25")
      (value "H807")
      (footprint "eagle-import:H807")
      (libsource (lib "eagle-import") (part "H807"))
    )
    (comp (ref "B26")
      (value "H807")
      (footprint "eagle-import:H807")
      (libsource (lib "eagle-import") (part "H807"))
    )
    (comp (ref "B27")
      (value "H807")
      (footprint "eagle-import:H807")
      (libsource (lib "eagle-import") (part "H807"))
    )
    (comp (ref "B28")
      (value "H807")
      (footprint "eagle-import:H807")
      (libsource (lib "eagle-import") (part "H807"))
    )
    (comp (ref "B29")
      (value "H807")
      (footprint "eagle-import:H807")
      (libsource (lib "eagle-import") (part "H807"))
    )
    (comp (ref "B30")
      (value "H807")
      (footprint "eagle-import:H807")
      (libsource (lib "eagle-import") (part "H807"))
    )
    (comp (ref "B31")
      (value "H807")
      (footprint "eagle-import:H807")
      (libsource (lib "eagle-import") (part "H807"))
    )
    (comp (ref "B32")
      (value "H807")
      (footprint "eagle-import:H807")
      (libsource (lib "eagle-import") (part "H807"))
    )
    (comp (ref "C19")
      (value "H807")
      (footprint "eagle-import:H807")
      (libsource (lib "eagle-import") (part "H807"))
    )
    (comp (ref "C20")
      (value "H807")
      (footprint "eagle-import:H807")
      (libsource (lib "eagle-import") (part "H807"))
    )
    (comp (ref "C21")
      (value "H807")
      (footprint "eagle-import:H807")
      (libsource (lib "eagle-import") (part "H807"))
    )
    (comp (ref "C22")
      (value "H807")
      (footprint "eagle-import:H807")
      (libsource (lib "eagle-import") (part "H807"))
    )
    (comp (ref "C23")
      (value "H807")
      (footprint "eagle-import:H807")
      (libsource (lib "eagle-import") (part "H807"))
    )
    (comp (ref "C24")
      (value "H807")
      (footprint "eagle-import:H807")
      (libsource (lib "eagle-import") (part "H807"))
    )
    (comp (ref "C25")
      (value "H807")
      (footprint "eagle-import:H807")
      (libsource (lib "eagle-import") (part "H807"))
    )
    (comp (ref "C26")
      (value "H807")
      (footprint "eagle-import:H807")
      (libsource (lib "eagle-import") (part "H807"))
    )
    (comp (ref "C27")
      (value "H807")
      (footprint "eagle-import:H807")
      (libsource (lib "eagle-import") (part "H807"))
    )
    (comp (ref "C28")
      (value "H807")
      (footprint "eagle-import:H807")
      (libsource (lib "eagle-import") (part "H807"))
    )
    (comp (ref "C29")
      (value "H807")
      (footprint "eagle-import:H807")
      (libsource (lib "eagle-import") (part "H807"))
    )
    (comp (ref "C30")
      (value "H807")
      (footprint "eagle-import:H807")
      (libsource (lib "eagle-import") (part "H807"))
    )
    (comp (ref "C31")
      (value "H807")
      (footprint "eagle-import:H807")
      (libsource (lib "eagle-import") (part "H807"))
    )
    (comp (ref "C32")
      (value "H807")
      (footprint "eagle-import:H807")
      (libsource (lib "eagle-import") (part "H807"))
    )
    (comp (ref "D01")
      (value "H807")
      (footprint "eagle-import:H807")
      (libsource (lib "eagle-import") (part "H807"))
    )
    (comp (ref "D02")
      (value "M903")
      (footprint "eagle-import:H807")
      (libsource (lib "eagle-import") (part "M903"))
    )
    (comp (ref "D03")
      (value "M903")
      (footprint "eagle-import:H807")
      (libsource (lib "eagle-import") (part "M903"))
    )
    (comp (ref "D04")
      (value "M903")
      (footprint "eagle-import:H807")
      (libsource (lib "eagle-import") (part "M903"))
    )
    (comp (ref "D05")
      (value "M903")
      (footprint "eagle-import:H807")
      (libsource (lib "eagle-import") (part "M903"))
    )
    (comp (ref "D06")
      (value "M903")
      (footprint "eagle-import:H807")
      (libsource (lib "eagle-import") (part "M903"))
    )
    (comp (ref "D19")
      (value "H807")
      (footprint "eagle-import:H807")
      (libsource (lib "eagle-import") (part "H807"))
    )
    (comp (ref "D20")
      (value "H807")
      (footprint "eagle-import:H807")
      (libsource (lib "eagle-import") (part "H807"))
    )
    (comp (ref "D21")
      (value "H807")
      (footprint "eagle-import:H807")
      (libsource (lib "eagle-import") (part "H807"))
    )
    (comp (ref "D22")
      (value "H807")
      (footprint "eagle-import:H807")
      (libsource (lib "eagle-import") (part "H807"))
    )
    (comp (ref "D23")
      (value "H807")
      (footprint "eagle-import:H807")
      (libsource (lib "eagle-import") (part "H807"))
    )
    (comp (ref "D24")
      (value "H807")
      (footprint "eagle-import:H807")
      (libsource (lib "eagle-import") (part "H807"))
    )
    (comp (ref "D25")
      (value "H807")
      (footprint "eagle-import:H807")
      (libsource (lib "eagle-import") (part "H807"))
    )
    (comp (ref "D26")
      (value "H807")
      (footprint "eagle-import:H807")
      (libsource (lib "eagle-import") (part "H807"))
    )
    (comp (ref "D27")
      (value "H807")
      (footprint "eagle-import:H807")
      (libsource (lib "eagle-import") (part "H807"))
    )
    (comp (ref "D28")
      (value "H807")
      (footprint "eagle-import:H807")
      (libsource (lib "eagle-import") (part "H807"))
    )
    (comp (ref "D29")
      (value "H807")
      (footprint "eagle-import:H807")
      (libsource (lib "eagle-import") (part "H807"))
    )
    (comp (ref "D30")
      (value "H807")
      (footprint "eagle-import:H807")
      (libsource (lib "eagle-import") (part "H807"))
    )
    (comp (ref "D31")
      (value "H807")
      (footprint "eagle-import:H807")
      (libsource (lib "eagle-import") (part "H807"))
    )
    (comp (ref "D32")
      (value "H807")
      (footprint "eagle-import:H807")
      (libsource (lib "eagle-import") (part "H807"))
    )
    (comp (ref "A07")
      (value "M161")
      (footprint "eagle-import:H807")
      (libsource (lib "eagle-import") (part "M161"))
    )
    (comp (ref "A22")
      (value "M502")
      (footprint "eagle-import:H807")
      (libsource (lib "eagle-import") (part "M502"))
    )
    (comp (ref "A23")
      (value "M633")
      (footprint "eagle-import:H807")
      (libsource (lib "eagle-import") (part "M633"))
    )
    (comp (ref "B07")
      (value "M207")
      (footprint "eagle-import:H807")
      (libsource (lib "eagle-import") (part "M207"))
    )
    (comp (ref "B22")
      (value "M633")
      (footprint "eagle-import:H807")
      (libsource (lib "eagle-import") (part "M633"))
    )
    (comp (ref "B23")
      (value "W005")
      (footprint "eagle-import:H807")
      (libsource (lib "eagle-import") (part "W005"))
    )
    (comp (ref "C07")
      (value "M207")
      (footprint "eagle-import:H807")
      (libsource (lib "eagle-import") (part "M207"))
    )
    (comp (ref "D07")
      (value "M161")
      (footprint "eagle-import:H807")
      (libsource (lib "eagle-import") (part "M161"))
    )
    (comp (ref "D09")
      (value "M121")
      (footprint "eagle-import:H807")
      (libsource (lib "eagle-import") (part "M121"))
    )
    (comp (ref "A18")
      (value "G888")
      (footprint "eagle-import:H807")
      (libsource (lib "eagle-import") (part "G888"))
    )
    (comp (ref "A20")
      (value "G888")
      (footprint "eagle-import:H807")
      (libsource (lib "eagle-import") (part "G888"))
    )
    (comp (ref "A21")
      (value "G888")
      (footprint "eagle-import:H807")
      (libsource (lib "eagle-import") (part "G888"))
    )
    (comp (ref "AB01")
      (value "G821")
      (footprint "eagle-import:H807-2")
      (libsource (lib "eagle-import") (part "G821"))
    )
    (comp (ref "AB19")
      (value "W032")
      (footprint "eagle-import:H807-2")
      (libsource (lib "eagle-import") (part "W032"))
    )
    (comp (ref "B18")
      (value "G888")
      (footprint "eagle-import:H807")
      (libsource (lib "eagle-import") (part "G888"))
    )
    (comp (ref "B20")
      (value "G888")
      (footprint "eagle-import:H807")
      (libsource (lib "eagle-import") (part "G888"))
    )
    (comp (ref "B13")
      (value "M206")
      (footprint "eagle-import:H807")
      (libsource (lib "eagle-import") (part "M206X"))
    )
    (comp (ref "C11")
      (value "M113")
      (footprint "eagle-import:H807")
      (libsource (lib "eagle-import") (part "M113"))
    )
    (comp (ref "D08")
      (value "M207")
      (footprint "eagle-import:H807")
      (libsource (lib "eagle-import") (part "M207"))
    )
    (comp (ref "CD18")
      (value "M228")
      (footprint "eagle-import:H807-2")
      (libsource (lib "eagle-import") (part "M228"))
    )
    (comp (ref "B02")
      (value "M623")
      (footprint "eagle-import:H807")
      (libsource (lib "eagle-import") (part "M623"))
    )
    (comp (ref "B03")
      (value "M623")
      (footprint "eagle-import:H807")
      (libsource (lib "eagle-import") (part "M623"))
    )
    (comp (ref "B04")
      (value "M623")
      (footprint "eagle-import:H807")
      (libsource (lib "eagle-import") (part "M623"))
    )
    (comp (ref "B05")
      (value "M623")
      (footprint "eagle-import:H807")
      (libsource (lib "eagle-import") (part "M623"))
    )
    (comp (ref "C02")
      (value "M101")
      (footprint "eagle-import:H807")
      (libsource (lib "eagle-import") (part "M101-ARRAY"))
    )
    (comp (ref "C03")
      (value "M101")
      (footprint "eagle-import:H807")
      (libsource (lib "eagle-import") (part "M101-ARRAY"))
    )
  )
  (nets
    (net (code "1") (name "+3V@A09U1") (class "Default")
      (node (ref "A07") (pin "S1") (pinfunction "EN2_S1") (pintype "input"))
      (node (ref "A07") (pin "S2") (pinfunction "EN1_S2") (pintype "input"))
      (node (ref "A07") (pin "T2") (pinfunction "EN3_T2") (pintype "input"))
      (node (ref "A08") (pin "D1") (pinfunction "S_D1") (pintype "input"))
      (node (ref "A08") (pin "F2") (pinfunction "S_F2") (pintype "input"))
      (node (ref "A08") (pin "K2") (pinfunction "R_K2") (pintype "input"))
      (node (ref "A09") (pin "U1") (pinfunction "P$1_U1") (pintype "passive"))
      (node (ref "B13") (pin "R1") (pinfunction "S_R1") (pintype "input"))
      (node (ref "B13") (pin "U2") (pinfunction "S_U2") (pintype "input"))
    )
    (net (code "2") (name "+3V@B12U1") (class "Default")
      (node (ref "B12") (pin "U1") (pinfunction "P$1_U1") (pintype "passive"))
      (node (ref "B13") (pin "D1") (pinfunction "S_D1") (pintype "input"))
      (node (ref "B13") (pin "F2") (pinfunction "S_F2") (pintype "input"))
      (node (ref "B13") (pin "K1") (pinfunction "S_K1") (pintype "input"))
      (node (ref "B14") (pin "A1") (pinfunction "R_A1") (pintype "input"))
      (node (ref "B14") (pin "K2") (pinfunction "R_K2") (pintype "input"))
      (node (ref "B14") (pin "N2") (pinfunction "S_N2") (pintype "input"))
      (node (ref "B14") (pin "R1") (pinfunction "S_R1") (pintype "input"))
      (node (ref "B14") (pin "U2") (pinfunction "S_U2") (pintype "input"))
    )
    (net (code "3") (name "+3V@C08U1") (class "Default")
      (node (ref "C01") (pin "C1") (pinfunction "IN2_C1") (pintype "input"))
      (node (ref "C02") (pin "C1") (pinfunction "ENABLE_C1") (pintype "input"))
      (node (ref "C04") (pin "J1") (pinfunction "IN2_J1") (pintype "input"))
      (node (ref "C04") (pin "L2") (pinfunction "L2_L2") (pintype "input"))
      (node (ref "C04") (pin "N2") (pinfunction "N2_N2") (pintype "input"))
      (node (ref "C04") (pin "U2") (pinfunction "U2_U2") (pintype "input"))
      (node (ref "C05") (pin "J1") (pinfunction "IN2_J1") (pintype "input"))
      (node (ref "C05") (pin "L2") (pinfunction "L2_L2") (pintype "input"))
      (node (ref "C05") (pin "N2") (pinfunction "N2_N2") (pintype "input"))
      (node (ref "C05") (pin "U2") (pinfunction "U2_U2") (pintype "input"))
      (node (ref "C08") (pin "U1") (pinfunction "P$1_U1") (pintype "passive"))
    )
    (net (code "4") (name "+3V@C15U1") (class "Default")
      (node (ref "C14") (pin "A1") (pinfunction "R_A1") (pintype "input"))
      (node (ref "C14") (pin "D1") (pinfunction "S_D1") (pintype "input"))
      (node (ref "C14") (pin "F2") (pinfunction "S_F2") (pintype "input"))
      (node (ref "C14") (pin "K1") (pinfunction "S_K1") (pintype "input"))
      (node (ref "C14") (pin "K2") (pinfunction "R_K2") (pintype "input"))
      (node (ref "C15") (pin "U1") (pinfunction "P$1_U1") (pintype "passive"))
      (node (ref "C16") (pin "H2") (pinfunction "IN4_H2") (pintype "input"))
    )
    (net (code "5") (name "+3V@D09U1") (class "Default")
      (node (ref "D07") (pin "S1") (pinfunction "EN2_S1") (pintype "input"))
      (node (ref "D07") (pin "S2") (pinfunction "EN1_S2") (pintype "input"))
      (node (ref "D07") (pin "T2") (pinfunction "EN3_T2") (pintype "input"))
      (node (ref "D09") (pin "U1") (pinfunction "P$1_U1") (pintype "passive"))
    )
    (net (code "6") (name "+3V@D10U1") (class "Default")
      (node (ref "D10") (pin "L2") (pinfunction "IN6_L2") (pintype "input"))
      (node (ref "D10") (pin "M2") (pinfunction "IN7_M2") (pintype "input"))
      (node (ref "D10") (pin "N2") (pinfunction "IN8_N2") (pintype "input"))
      (node (ref "D10") (pin "U1") (pinfunction "P$1_U1") (pintype "passive"))
      (node (ref "D11") (pin "D1") (pinfunction "S_D1") (pintype "input"))
      (node (ref "D11") (pin "F2") (pinfunction "S_F2") (pintype "input"))
      (node (ref "D11") (pin "K1") (pinfunction "S_K1") (pintype "input"))
      (node (ref "D11") (pin "K2") (pinfunction "R_K2") (pintype "input"))
      (node (ref "D14") (pin "M1") (pinfunction "M1_M1") (pintype "input"))
    )
    (net (code "7") (name "+11V") (class "Default")
      (node (ref "AB01") (pin "BM2") (pinfunction "+11V_BM2") (pintype "power_in"))
    )
    (net (code "8") (name "-15V") (class "Default")
      (node (ref "AB01") (pin "AB2") (pinfunction "-15V_AB2") (pintype "power_in"))
      (node (ref "AB01") (pin "AE2") (pinfunction "-15V_AE2") (pintype "power_in"))
      (node (ref "AB01") (pin "AF2") (pinfunction "-15V_AF2") (pintype "power_in"))
    )
    (net (code "9") (name "00") (class "Default")
      (node (ref "A07") (pin "D2") (pinfunction "O0_D2") (pintype "output"))
    )
    (net (code "10") (name "0_TO_DTB") (class "Default")
      (node (ref "A11") (pin "M1") (pinfunction "OUT_M1") (pintype "output"))
      (node (ref "C11") (pin "R1") (pinfunction "IN2_R1") (pintype "input"))
    )
    (net (code "11") (name "0_TO_EF") (class "Default")
      (node (ref "A10") (pin "K2") (pinfunction "OUT_K2") (pintype "output"))
      (node (ref "A11") (pin "E2") (pinfunction "IN_E2") (pintype "input"))
    )
    (net (code "12") (name "0_TO_STA") (class "Default")
      (node (ref "A10") (pin "N2") (pinfunction "OUT_N2") (pintype "output"))
      (node (ref "A11") (pin "N1") (pinfunction "IN_N1") (pintype "input"))
    )
    (net (code "13") (name "01") (class "Default")
      (node (ref "A07") (pin "E2") (pinfunction "O1_E2") (pintype "output"))
    )
    (net (code "14") (name "1_TO_DF") (class "Default")
      (node (ref "A08") (pin "H1") (pinfunction "C_H1") (pintype "input"))
      (node (ref "C12") (pin "J1") (pinfunction "OUT_J1") (pintype "output"))
      (node (ref "C12") (pin "L1") (pinfunction "IN2_L1") (pintype "input"))
      (node (ref "D11") (pin "L2") (pinfunction "C_L2") (pintype "input"))
    )
    (net (code "15") (name "1_TO_DTF") (class "Default")
      (node (ref "B12") (pin "P2") (pinfunction "OUT_P2") (pintype "output"))
      (node (ref "D11") (pin "S2") (pinfunction "C_S2") (pintype "input"))
    )
    (net (code "16") (name "02") (class "Default")
      (node (ref "A07") (pin "J2") (pinfunction "O2_J2") (pintype "output"))
    )
    (net (code "17") (name "03") (class "Default")
      (node (ref "A07") (pin "N2") (pinfunction "O3_N2") (pintype "output"))
    )
    (net (code "18") (name "04") (class "Default")
      (node (ref "A07") (pin "F2") (pinfunction "O4_F2") (pintype "output"))
    )
    (net (code "19") (name "05") (class "Default")
      (node (ref "A07") (pin "M2") (pinfunction "O5_M2") (pintype "output"))
    )
    (net (code "20") (name "06") (class "Default")
      (node (ref "A07") (pin "H2") (pinfunction "O6_H2") (pintype "output"))
    )
    (net (code "21") (name "07") (class "Default")
      (node (ref "A07") (pin "L2") (pinfunction "O7_L2") (pintype "output"))
    )
    (net (code "22") (name "76") (class "Default")
      (node (ref "C04") (pin "V2") (pinfunction "V2_V2") (pintype "output"))
      (node (ref "C06") (pin "S2") (pinfunction "IN_S2") (pintype "input"))
    )
    (net (code "23") (name "76+77") (class "Default")
      (node (ref "C03") (pin "C1") (pinfunction "ENABLE_C1") (pintype "input"))
      (node (ref "D12") (pin "V2") (pinfunction "OUT_V2") (pintype "output"))
    )
    (net (code "24") (name "77") (class "Default")
      (node (ref "C05") (pin "V2") (pinfunction "V2_V2") (pintype "output"))
      (node (ref "C06") (pin "U2") (pinfunction "IN_U2") (pintype "input"))
    )
    (net (code "25") (name "ADDR_ACC") (class "Default")
      (node (ref "C02") (pin "V2") (pinfunction "O15_V2") (pintype "output"))
      (node (ref "C17") (pin "N1") (pinfunction "IN_N1") (pintype "input"))
    )
    (net (code "26") (name "B-BRK") (class "Default")
      (node (ref "B10") (pin "R2") (pinfunction "IN1_R2") (pintype "input"))
      (node (ref "B10") (pin "S2") (pinfunction "IN2_S2") (pintype "input"))
      (node (ref "B10") (pin "T2") (pinfunction "IN3_T2") (pintype "input"))
      (node (ref "B10") (pin "U2") (pinfunction "IN4_U2") (pintype "input"))
      (node (ref "C01") (pin "E1") (pinfunction "OUT_E1") (pintype "output"))
      (node (ref "D12") (pin "M1") (pinfunction "IN1_M1") (pintype "input"))
    )
    (net (code "27") (name "B-RUN") (class "Default")
      (node (ref "B11") (pin "N2") (pinfunction "IN1_N2") (pintype "input"))
      (node (ref "C01") (pin "B1") (pinfunction "OUT_B1") (pintype "output"))
    )
    (net (code "28") (name "B-XSTA") (class "Default")
      (node (ref "A10") (pin "E2") (pinfunction "IN2_E2") (pintype "input"))
      (node (ref "C11") (pin "P2") (pinfunction "IN1_P2") (pintype "input"))
      (node (ref "D12") (pin "E1") (pinfunction "OUT_E1") (pintype "output"))
    )
    (net (code "29") (name "BAC_00") (class "Default")
      (node (ref "B06") (pin "B1") (pinfunction "OUT_B1") (pintype "output"))
      (node (ref "B07") (pin "C1") (pinfunction "C1_C1") (pintype "input"))
      (node (ref "B07") (pin "D1") (pinfunction "D1_D1") (pintype "input"))
    )
    (net (code "30") (name "BAC_01") (class "Default")
      (node (ref "B06") (pin "E1") (pinfunction "OUT_E1") (pintype "output"))
      (node (ref "B07") (pin "E2") (pinfunction "E2_E2") (pintype "input"))
      (node (ref "B07") (pin "F2") (pinfunction "F2_F2") (pintype "input"))
    )
    (net (code "31") (name "BAC_02") (class "Default")
      (node (ref "B06") (pin "H1") (pinfunction "OUT_H1") (pintype "output"))
      (node (ref "B07") (pin "J1") (pinfunction "J1_J1") (pintype "input"))
      (node (ref "B07") (pin "K1") (pinfunction "K1_K1") (pintype "input"))
    )
    (net (code "32") (name "BAC_03") (class "Default")
      (node (ref "B06") (pin "K1") (pinfunction "OUT_K1") (pintype "output"))
      (node (ref "B07") (pin "M2") (pinfunction "M2_M2") (pintype "input"))
      (node (ref "B07") (pin "N2") (pinfunction "N2_N2") (pintype "input"))
    )
    (net (code "33") (name "BAC_04") (class "Default")
      (node (ref "B06") (pin "M1") (pinfunction "OUT_M1") (pintype "output"))
      (node (ref "C07") (pin "M2") (pinfunction "M2_M2") (pintype "input"))
      (node (ref "C07") (pin "N2") (pinfunction "N2_N2") (pintype "input"))
    )
    (net (code "34") (name "BAC_05") (class "Default")
      (node (ref "B06") (pin "P1") (pinfunction "OUT_P1") (pintype "output"))
      (node (ref "B07") (pin "P1") (pinfunction "P1_P1") (pintype "input"))
      (node (ref "B07") (pin "R1") (pinfunction "R1_R1") (pintype "input"))
    )
    (net (code "35") (name "BAC_06") (class "Default")
      (node (ref "B06") (pin "S1") (pinfunction "OUT_S1") (pintype "output"))
      (node (ref "B07") (pin "T2") (pinfunction "T2_T2") (pintype "input"))
      (node (ref "B07") (pin "U2") (pinfunction "U2_U2") (pintype "input"))
      (node (ref "D11") (pin "C1") (pinfunction "D_C1") (pintype "input"))
    )
    (net (code "36") (name "BAC_07") (class "Default")
      (node (ref "B06") (pin "U1") (pinfunction "OUT_U1") (pintype "output"))
      (node (ref "C07") (pin "C1") (pinfunction "C1_C1") (pintype "input"))
      (node (ref "C07") (pin "D1") (pinfunction "D1_D1") (pintype "input"))
      (node (ref "D11") (pin "E2") (pinfunction "D_E2") (pintype "input"))
    )
    (net (code "37") (name "BAC_08") (class "Default")
      (node (ref "B06") (pin "D2") (pinfunction "OUT_D2") (pintype "output"))
      (node (ref "C07") (pin "E2") (pinfunction "E2_E2") (pintype "input"))
      (node (ref "C07") (pin "F2") (pinfunction "F2_F2") (pintype "input"))
      (node (ref "D11") (pin "J1") (pinfunction "D_J1") (pintype "input"))
    )
    (net (code "38") (name "BAC_09") (class "Default")
      (node (ref "B06") (pin "F2") (pinfunction "OUT_F2") (pintype "output"))
      (node (ref "C07") (pin "J1") (pinfunction "J1_J1") (pintype "input"))
      (node (ref "C07") (pin "K1") (pinfunction "K1_K1") (pintype "input"))
    )
    (net (code "39") (name "BAC_10") (class "Default")
      (node (ref "B06") (pin "J2") (pinfunction "OUT_J2") (pintype "output"))
    )
    (net (code "40") (name "BAC_11") (class "Default")
      (node (ref "B06") (pin "L2") (pinfunction "OUT_L2") (pintype "output"))
    )
    (net (code "41") (name "BLK_IN_SYNC") (class "Default")
      (node (ref "C11") (pin "E2") (pinfunction "IN2_E2") (pintype "input"))
      (node (ref "C13") (pin "S1") (pinfunction "OUT_S1") (pintype "output"))
      (node (ref "CD18") (pin "AP2") (pinfunction "AP2_AP2") (pintype "input"))
    )
    (net (code "42") (name "BMB_00") (class "Default")
      (node (ref "C06") (pin "B1") (pinfunction "OUT_B1") (pintype "output"))
      (node (ref "C08") (pin "B1") (pinfunction "IN1B_B1") (pintype "input"))
    )
    (net (code "43") (name "BMB_01") (class "Default")
      (node (ref "C06") (pin "E1") (pinfunction "OUT_E1") (pintype "output"))
      (node (ref "C08") (pin "H1") (pinfunction "IN1B_H1") (pintype "input"))
    )
    (net (code "44") (name "BMB_02") (class "Default")
      (node (ref "C06") (pin "H1") (pinfunction "OUT_H1") (pintype "output"))
      (node (ref "C08") (pin "N1") (pinfunction "IN1B_N1") (pintype "input"))
    )
    (net (code "45") (name "BMB_03") (class "Default")
      (node (ref "C06") (pin "K1") (pinfunction "OUT_K1") (pintype "output"))
      (node (ref "C08") (pin "E2") (pinfunction "IN1B_E2") (pintype "input"))
    )
    (net (code "46") (name "BMB_04") (class "Default")
      (node (ref "C06") (pin "M1") (pinfunction "OUT_M1") (pintype "output"))
      (node (ref "C08") (pin "L2") (pinfunction "IN1B_L2") (pintype "input"))
    )
    (net (code "47") (name "BMB_05") (class "Default")
      (node (ref "C06") (pin "P1") (pinfunction "OUT_P1") (pintype "output"))
      (node (ref "C08") (pin "S2") (pinfunction "IN1B_S2") (pintype "input"))
    )
    (net (code "48") (name "BMB_06") (class "Default")
      (node (ref "B08") (pin "B1") (pinfunction "IN2_B1") (pintype "input"))
      (node (ref "C06") (pin "S1") (pinfunction "OUT_S1") (pintype "output"))
    )
    (net (code "49") (name "BMB_07") (class "Default")
      (node (ref "B08") (pin "E1") (pinfunction "IN2_E1") (pintype "input"))
      (node (ref "C06") (pin "U1") (pinfunction "OUT_U1") (pintype "output"))
    )
    (net (code "50") (name "BMB_08") (class "Default")
      (node (ref "B08") (pin "E2") (pinfunction "IN2_E2") (pintype "input"))
      (node (ref "C06") (pin "D2") (pinfunction "OUT_D2") (pintype "output"))
    )
    (net (code "51") (name "BMB_09") (class "Default")
      (node (ref "B08") (pin "M1") (pinfunction "IN2_M1") (pintype "input"))
      (node (ref "C06") (pin "F2") (pinfunction "OUT_F2") (pintype "output"))
    )
    (net (code "52") (name "BMB_10") (class "Default")
      (node (ref "B08") (pin "R1") (pinfunction "IN2_R1") (pintype "input"))
      (node (ref "C06") (pin "J2") (pinfunction "OUT_J2") (pintype "output"))
    )
    (net (code "53") (name "BMB_11") (class "Default")
      (node (ref "B08") (pin "J1") (pinfunction "IN2_J1") (pintype "input"))
      (node (ref "C06") (pin "L2") (pinfunction "OUT_L2") (pintype "output"))
    )
    (net (code "54") (name "BMB_TO_DTB") (class "Default")
      (node (ref "B08") (pin "A1") (pinfunction "IN1_A1") (pintype "input"))
      (node (ref "B08") (pin "D1") (pinfunction "IN1_D1") (pintype "input"))
      (node (ref "B08") (pin "D2") (pinfunction "IN1_D2") (pintype "input"))
      (node (ref "B08") (pin "H1") (pinfunction "IN1_H1") (pintype "input"))
      (node (ref "B08") (pin "L1") (pinfunction "IN1_L1") (pintype "input"))
      (node (ref "B08") (pin "P1") (pinfunction "IN1_P1") (pintype "input"))
      (node (ref "C08") (pin "A1") (pinfunction "IN1A_A1") (pintype "input"))
      (node (ref "C08") (pin "D2") (pinfunction "IN1A_D2") (pintype "input"))
      (node (ref "C08") (pin "F1") (pinfunction "IN1A_F1") (pintype "input"))
      (node (ref "C08") (pin "K2") (pinfunction "IN1A_K2") (pintype "input"))
      (node (ref "C08") (pin "M1") (pinfunction "IN1A_M1") (pintype "input"))
      (node (ref "C08") (pin "R2") (pinfunction "IN1A_R2") (pintype "input"))
      (node (ref "D12") (pin "L1") (pinfunction "OUT_L1") (pintype "output"))
    )
    (net (code "55") (name "BMR00") (class "Default")
      (node (ref "A23") (pin "F1") (pinfunction "A_F1") (pintype "input"))
      (node (ref "B14") (pin "P2") (pinfunction "1_P2") (pintype "output"))
    )
    (net (code "56") (name "BMR01") (class "Default")
      (node (ref "A23") (pin "B1") (pinfunction "B_B1") (pintype "input"))
      (node (ref "B14") (pin "F1") (pinfunction "0_F1") (pintype "output"))
    )
    (net (code "57") (name "C00") (class "Default")
      (node (ref "A12") (pin "L2") (pinfunction "IN1_L2") (pintype "input"))
      (node (ref "A26") (pin "E2") (pinfunction "P$2_E2") (pintype "bidirectional"))
      (node (ref "B12") (pin "R2") (pinfunction "IN1_R2") (pintype "input"))
      (node (ref "B13") (pin "S1") (pinfunction "1_S1") (pintype "output"))
      (node (ref "C15") (pin "E2") (pinfunction "IN2_E2") (pintype "input"))
      (node (ref "D10") (pin "C1") (pinfunction "IN3_C1") (pintype "input"))
    )
    (net (code "58") (name "C01") (class "Default")
      (node (ref "A12") (pin "M2") (pinfunction "IN2_M2") (pintype "input"))
      (node (ref "A26") (pin "F2") (pinfunction "P$2_F2") (pintype "bidirectional"))
      (node (ref "B10") (pin "J1") (pinfunction "IN3_J1") (pintype "input"))
      (node (ref "B11") (pin "V2") (pinfunction "IN3_V2") (pintype "input"))
      (node (ref "B13") (pin "P2") (pinfunction "1_P2") (pintype "output"))
    )
    (net (code "59") (name "CK00") (class "Default")
      (node (ref "A18") (pin "P2") (pinfunction "P2_P2") (pintype "input"))
      (node (ref "B14") (pin "S1") (pinfunction "1_S1") (pintype "output"))
    )
    (net (code "60") (name "CK01") (class "Default")
      (node (ref "B14") (pin "P1") (pinfunction "D_P1") (pintype "input"))
      (node (ref "B14") (pin "V2") (pinfunction "1_V2") (pintype "output"))
      (node (ref "C16") (pin "N1") (pinfunction "IN2_N1") (pintype "input"))
      (node (ref "C16") (pin "P1") (pinfunction "IN3_P1") (pintype "input"))
      (node (ref "C16") (pin "R1") (pinfunction "IN4_R1") (pintype "input"))
    )
    (net (code "61") (name "COMP+SH") (class "Default")
      (node (ref "A12") (pin "D2") (pinfunction "IN1_D2") (pintype "input"))
      (node (ref "C14") (pin "B1") (pinfunction "C_B1") (pintype "input"))
      (node (ref "C14") (pin "D2") (pinfunction "C_D2") (pintype "input"))
      (node (ref "C14") (pin "H1") (pinfunction "C_H1") (pintype "input"))
      (node (ref "C15") (pin "K1") (pinfunction "OUT_K1") (pintype "output"))
    )
    (net (code "62") (name "CSTA") (class "Default")
      (node (ref "C04") (pin "C1") (pinfunction "C1_C1") (pintype "output"))
      (node (ref "D16") (pin "P2") (pinfunction "K2_P2") (pintype "input"))
    )
    (net (code "63") (name "DATA") (class "Default")
      (node (ref "A26") (pin "M1") (pinfunction "P$2_M1") (pintype "bidirectional"))
      (node (ref "C13") (pin "F1") (pinfunction "IN_F1") (pintype "input"))
      (node (ref "CD18") (pin "BK2") (pinfunction "BK2_BK2") (pintype "output"))
    )
    (net (code "64") (name "DF") (class "Default")
      (node (ref "A10") (pin "P2") (pinfunction "IN1_P2") (pintype "input"))
      (node (ref "A26") (pin "E1") (pinfunction "P$2_E1") (pintype "bidirectional"))
      (node (ref "D11") (pin "R2") (pinfunction "0_R2") (pintype "output"))
    )
    (net (code "65") (name "DTB_00") (class "Default")
      (node (ref "A25") (pin "A2") (pinfunction "P$2_A2") (pintype "bidirectional"))
      (node (ref "C09") (pin "E1") (pinfunction "1_E1") (pintype "output"))
      (node (ref "C10") (pin "B1") (pinfunction "IN1B_B1") (pintype "input"))
      (node (ref "D09") (pin "D2") (pinfunction "IN1A_D2") (pintype "input"))
    )
    (net (code "66") (name "DTB_01") (class "Default")
      (node (ref "A25") (pin "B2") (pinfunction "P$2_B2") (pintype "bidirectional"))
      (node (ref "C09") (pin "H2") (pinfunction "1_H2") (pintype "output"))
      (node (ref "C10") (pin "H1") (pinfunction "IN1B_H1") (pintype "input"))
      (node (ref "D09") (pin "K2") (pinfunction "IN1A_K2") (pintype "input"))
    )
    (net (code "67") (name "DTB_02") (class "Default")
      (node (ref "A25") (pin "C2") (pinfunction "P$2_C2") (pintype "bidirectional"))
      (node (ref "C09") (pin "L1") (pinfunction "1_L1") (pintype "output"))
      (node (ref "C10") (pin "N1") (pinfunction "IN1B_N1") (pintype "input"))
      (node (ref "D09") (pin "R2") (pinfunction "IN1A_R2") (pintype "input"))
    )
    (net (code "68") (name "DTB_03") (class "Default")
      (node (ref "A25") (pin "D2") (pinfunction "P$2_D2") (pintype "bidirectional"))
      (node (ref "C09") (pin "C1") (pinfunction "D_C1") (pintype "input"))
      (node (ref "C09") (pin "P2") (pinfunction "1_P2") (pintype "output"))
    )
    (net (code "69") (name "DTB_04") (class "Default")
      (node (ref "A25") (pin "E2") (pinfunction "P$2_E2") (pintype "bidirectional"))
      (node (ref "C09") (pin "E2") (pinfunction "D_E2") (pintype "input"))
      (node (ref "C09") (pin "S1") (pinfunction "1_S1") (pintype "output"))
    )
    (net (code "70") (name "DTB_05") (class "Default")
      (node (ref "A25") (pin "F2") (pinfunction "P$2_F2") (pintype "bidirectional"))
      (node (ref "C09") (pin "J1") (pinfunction "D_J1") (pintype "input"))
      (node (ref "C09") (pin "V2") (pinfunction "1_V2") (pintype "output"))
    )
    (net (code "71") (name "DTB_06") (class "Default")
      (node (ref "A25") (pin "H2") (pinfunction "P$2_H2") (pintype "bidirectional"))
      (node (ref "B09") (pin "E1") (pinfunction "1_E1") (pintype "output"))
      (node (ref "C09") (pin "M2") (pinfunction "D_M2") (pintype "input"))
    )
    (net (code "72") (name "DTB_07") (class "Default")
      (node (ref "A25") (pin "J2") (pinfunction "P$2_J2") (pintype "bidirectional"))
      (node (ref "B09") (pin "V2") (pinfunction "1_V2") (pintype "output"))
      (node (ref "C09") (pin "P1") (pinfunction "D_P1") (pintype "input"))
    )
    (net (code "73") (name "DTB_08") (class "Default")
      (node (ref "A25") (pin "K2") (pinfunction "P$2_K2") (pintype "bidirectional"))
      (node (ref "B09") (pin "L1") (pinfunction "1_L1") (pintype "output"))
      (node (ref "C09") (pin "T2") (pinfunction "D_T2") (pintype "input"))
    )
    (net (code "74") (name "DTB_09") (class "Default")
      (node (ref "A25") (pin "L2") (pinfunction "P$2_L2") (pintype "bidirectional"))
      (node (ref "B09") (pin "C1") (pinfunction "D_C1") (pintype "input"))
      (node (ref "B09") (pin "P2") (pinfunction "1_P2") (pintype "output"))
    )
    (net (code "75") (name "DTB_10") (class "Default")
      (node (ref "A25") (pin "M2") (pinfunction "P$2_M2") (pintype "bidirectional"))
      (node (ref "B09") (pin "S1") (pinfunction "1_S1") (pintype "output"))
      (node (ref "B09") (pin "T2") (pinfunction "D_T2") (pintype "input"))
    )
    (net (code "76") (name "DTB_11") (class "Default")
      (node (ref "A25") (pin "N2") (pinfunction "P$2_N2") (pintype "bidirectional"))
      (node (ref "B09") (pin "H2") (pinfunction "1_H2") (pintype "output"))
      (node (ref "B09") (pin "J1") (pinfunction "D_J1") (pintype "input"))
    )
    (net (code "77") (name "DTF") (class "Default")
      (node (ref "A08") (pin "J1") (pinfunction "D_J1") (pintype "input"))
      (node (ref "A12") (pin "M1") (pinfunction "IN2_M1") (pintype "input"))
      (node (ref "A26") (pin "C1") (pinfunction "P$2_C1") (pintype "bidirectional"))
      (node (ref "D11") (pin "V1") (pinfunction "0_V1") (pintype "output"))
    )
    (net (code "78") (name "DTSF") (class "Default")
      (node (ref "A12") (pin "R1") (pinfunction "IN2_R1") (pintype "input"))
      (node (ref "C05") (pin "A1") (pinfunction "A1_A1") (pintype "output"))
    )
    (net (code "79") (name "EF") (class "Default")
      (node (ref "A11") (pin "J1") (pinfunction "IN_J1") (pintype "input"))
      (node (ref "A12") (pin "F1") (pinfunction "OUT_F1") (pintype "output"))
      (node (ref "A12") (pin "L1") (pinfunction "IN1_L1") (pintype "input"))
      (node (ref "A25") (pin "N1") (pinfunction "P$2_N1") (pintype "bidirectional"))
    )
    (net (code "80") (name "END") (class "Default")
      (node (ref "A08") (pin "E1") (pinfunction "1_E1") (pintype "output"))
      (node (ref "A25") (pin "R1") (pinfunction "P$2_R1") (pintype "bidirectional"))
    )
    (net (code "81") (name "ENI") (class "Default")
      (node (ref "A12") (pin "H1") (pinfunction "IN1_H1") (pintype "input"))
      (node (ref "A25") (pin "L1") (pinfunction "P$2_L1") (pintype "bidirectional"))
      (node (ref "C07") (pin "L1") (pinfunction "L1_L1") (pintype "output"))
    )
    (net (code "82") (name "FR_00") (class "Default")
      (node (ref "A25") (pin "F1") (pinfunction "P$2_F1") (pintype "bidirectional"))
      (node (ref "B07") (pin "S1") (pinfunction "S1_S1") (pintype "output"))
      (node (ref "B12") (pin "E2") (pinfunction "IN2_E2") (pintype "input"))
      (node (ref "C12") (pin "U2") (pinfunction "IN2_U2") (pintype "input"))
    )
    (net (code "83") (name "FR_01") (class "Default")
      (node (ref "A10") (pin "H1") (pinfunction "IN1_H1") (pintype "input"))
      (node (ref "A25") (pin "H1") (pinfunction "P$2_H1") (pintype "bidirectional"))
      (node (ref "B07") (pin "V2") (pinfunction "V2_V2") (pintype "output"))
      (node (ref "B15") (pin "M1") (pinfunction "IN2_M1") (pintype "input"))
      (node (ref "C15") (pin "D1") (pinfunction "IN1_D1") (pintype "input"))
      (node (ref "D07") (pin "V2") (pinfunction "IN2_V2") (pintype "input"))
      (node (ref "D12") (pin "R1") (pinfunction "IN4_R1") (pintype "input"))
    )
    (net (code "84") (name "FR_02") (class "Default")
      (node (ref "A25") (pin "J1") (pinfunction "P$2_J1") (pintype "bidirectional"))
      (node (ref "C07") (pin "E1") (pinfunction "E1_E1") (pintype "output"))
      (node (ref "D07") (pin "U2") (pinfunction "IN1_U2") (pintype "input"))
    )
    (net (code "85") (name "FR_03") (class "Default")
      (node (ref "A25") (pin "K1") (pinfunction "P$2_K1") (pintype "bidirectional"))
      (node (ref "B15") (pin "R2") (pinfunction "IN2_R2") (pintype "input"))
      (node (ref "C07") (pin "H2") (pinfunction "H2_H2") (pintype "output"))
      (node (ref "D07") (pin "V1") (pinfunction "IN0_V1") (pintype "input"))
    )
    (net (code "86") (name "GND") (class "Default")
      (node (ref "A05") (pin "B1") (pinfunction "P$2_B1") (pintype "bidirectional"))
      (node (ref "A05") (pin "D1") (pinfunction "P$2_D1") (pintype "bidirectional"))
      (node (ref "A05") (pin "D2") (pinfunction "P$2_D2") (pintype "bidirectional"))
      (node (ref "A05") (pin "E1") (pinfunction "P$2_E1") (pintype "bidirectional"))
      (node (ref "A05") (pin "H1") (pinfunction "P$2_H1") (pintype "bidirectional"))
      (node (ref "A05") (pin "J1") (pinfunction "P$2_J1") (pintype "bidirectional"))
      (node (ref "A05") (pin "L1") (pinfunction "P$2_L1") (pintype "bidirectional"))
      (node (ref "A05") (pin "M1") (pinfunction "P$2_M1") (pintype "bidirectional"))
      (node (ref "A05") (pin "P1") (pinfunction "P$2_P1") (pintype "bidirectional"))
      (node (ref "A05") (pin "S1") (pinfunction "P$2_S1") (pintype "bidirectional"))
      (node (ref "A06") (pin "K2") (pinfunction "P$2_K2") (pintype "bidirectional"))
      (node (ref "A07") (pin "U1") (pinfunction "IN*_U1") (pintype "input"))
      (node (ref "A08") (pin "T2") (pinfunction "D_T2") (pintype "input"))
      (node (ref "A23") (pin "C1") (pinfunction "C_C1") (pintype "input"))
      (node (ref "A23") (pin "F2") (pinfunction "C_F2") (pintype "input"))
      (node (ref "A23") (pin "J1") (pinfunction "C_J1") (pintype "input"))
      (node (ref "A23") (pin "M2") (pinfunction "C_M2") (pintype "input"))
      (node (ref "A23") (pin "P1") (pinfunction "C_P1") (pintype "input"))
      (node (ref "A23") (pin "T2") (pinfunction "C_T2") (pintype "input"))
      (node (ref "A25") (pin "M1") (pinfunction "P$2_M1") (pintype "bidirectional"))
      (node (ref "A26") (pin "D2") (pinfunction "P$2_D2") (pintype "bidirectional"))
      (node (ref "A26") (pin "U2") (pinfunction "P$2_U2") (pintype "bidirectional"))
      (node (ref "A26") (pin "V1") (pinfunction "P$2_V1") (pintype "bidirectional"))
      (node (ref "AB01") (pin "AC2") (pinfunction "GND_AC2") (pintype "power_in"))
      (node (ref "AB01") (pin "AH2") (pinfunction "GND_AH2") (pintype "power_in"))
      (node (ref "AB01") (pin "AK2") (pinfunction "GND_AK2") (pintype "power_in"))
      (node (ref "AB01") (pin "AL2") (pinfunction "GND_AL2") (pintype "power_in"))
      (node (ref "AB01") (pin "AT1") (pinfunction "GND_AT1") (pintype "power_in"))
      (node (ref "AB01") (pin "BC2") (pinfunction "GND_BC2") (pintype "power_in"))
      (node (ref "AB01") (pin "BD2") (pinfunction "GND_BD2") (pintype "power_in"))
      (node (ref "AB01") (pin "BH2") (pinfunction "GND_BH2") (pintype "power_in"))
      (node (ref "AB01") (pin "BK2") (pinfunction "GND_BK2") (pintype "power_in"))
      (node (ref "AB01") (pin "BL2") (pinfunction "GND_BL2") (pintype "power_in"))
      (node (ref "AB01") (pin "BT1") (pinfunction "GND_BT1") (pintype "power_in"))
      (node (ref "AB19") (pin "AJ2") (pinfunction "P$2_AJ2") (pintype "bidirectional"))
      (node (ref "AB19") (pin "AR2") (pinfunction "P$2_AR2") (pintype "bidirectional"))
      (node (ref "AB19") (pin "AU2") (pinfunction "P$2_AU2") (pintype "bidirectional"))
      (node (ref "AB19") (pin "BF2") (pinfunction "P$2_BF2") (pintype "bidirectional"))
      (node (ref "AB19") (pin "BM2") (pinfunction "P$2_BM2") (pintype "bidirectional"))
      (node (ref "B05") (pin "C1") (pinfunction "C_C1") (pintype "input"))
      (node (ref "B05") (pin "F2") (pinfunction "C_F2") (pintype "input"))
      (node (ref "B05") (pin "J1") (pinfunction "C_J1") (pintype "input"))
      (node (ref "B05") (pin "M2") (pinfunction "C_M2") (pintype "input"))
      (node (ref "B05") (pin "P1") (pinfunction "C_P1") (pintype "input"))
      (node (ref "B22") (pin "T2") (pinfunction "C_T2") (pintype "input"))
      (node (ref "D05") (pin "B1") (pinfunction "P$2_B1") (pintype "bidirectional"))
      (node (ref "D05") (pin "D1") (pinfunction "P$2_D1") (pintype "bidirectional"))
      (node (ref "D05") (pin "D2") (pinfunction "P$2_D2") (pintype "bidirectional"))
      (node (ref "D05") (pin "E1") (pinfunction "P$2_E1") (pintype "bidirectional"))
      (node (ref "D05") (pin "H1") (pinfunction "P$2_H1") (pintype "bidirectional"))
      (node (ref "D05") (pin "J1") (pinfunction "P$2_J1") (pintype "bidirectional"))
      (node (ref "D05") (pin "L1") (pinfunction "P$2_L1") (pintype "bidirectional"))
      (node (ref "D05") (pin "M1") (pinfunction "P$2_M1") (pintype "bidirectional"))
      (node (ref "D05") (pin "P1") (pinfunction "P$2_P1") (pintype "bidirectional"))
      (node (ref "D05") (pin "S1") (pinfunction "P$2_S1") (pintype "bidirectional"))
      (node (ref "D06") (pin "K2") (pinfunction "P$2_K2") (pintype "bidirectional"))
      (node (ref "D07") (pin "U1") (pinfunction "IN*_U1") (pintype "input"))
      (node (ref "D11") (pin "P1") (pinfunction "D_P1") (pintype "input"))
      (node (ref "D11") (pin "T2") (pinfunction "D_T2") (pintype "input"))
    )
    (net (code "87") (name "IOP_1") (class "Default")
      (node (ref "A02") (pin "K2") (pinfunction "P$2_K2") (pintype "bidirectional"))
      (node (ref "C04") (pin "P2") (pinfunction "P2_P2") (pintype "input"))
      (node (ref "C05") (pin "P2") (pinfunction "P2_P2") (pintype "input"))
      (node (ref "D02") (pin "K2") (pinfunction "P$2_K2") (pintype "bidirectional"))
    )
    (net (code "88") (name "IOP_2") (class "Default")
      (node (ref "A02") (pin "M2") (pinfunction "P$2_M2") (pintype "bidirectional"))
      (node (ref "C04") (pin "R2") (pinfunction "R2_R2") (pintype "input"))
      (node (ref "C05") (pin "R2") (pinfunction "R2_R2") (pintype "input"))
      (node (ref "D02") (pin "M2") (pinfunction "P$2_M2") (pintype "bidirectional"))
    )
    (net (code "89") (name "IOP_4") (class "Default")
      (node (ref "A02") (pin "P2") (pinfunction "P$2_P2") (pintype "bidirectional"))
      (node (ref "C04") (pin "S2") (pinfunction "S2_S2") (pintype "input"))
      (node (ref "C05") (pin "S2") (pinfunction "S2_S2") (pintype "input"))
      (node (ref "D02") (pin "P2") (pinfunction "P$2_P2") (pintype "bidirectional"))
    )
    (net (code "90") (name "I{slash}O_B-BRK") (class "Default")
      (node (ref "A05") (pin "P2") (pinfunction "P$2_P2") (pintype "bidirectional"))
      (node (ref "C01") (pin "D1") (pinfunction "IN_D1") (pintype "input"))
      (node (ref "D05") (pin "P2") (pinfunction "P$2_P2") (pintype "bidirectional"))
    )
    (net (code "91") (name "I{slash}O_B-RUN") (class "Default")
      (node (ref "A04") (pin "S2") (pinfunction "P$2_S2") (pintype "bidirectional"))
      (node (ref "C01") (pin "A1") (pinfunction "IN1_A1") (pintype "input"))
      (node (ref "D04") (pin "S2") (pinfunction "P$2_S2") (pintype "bidirectional"))
    )
    (net (code "92") (name "I{slash}O_BAC_00") (class "Default")
      (node (ref "A02") (pin "B1") (pinfunction "P$2_B1") (pintype "bidirectional"))
      (node (ref "C03") (pin "A1") (pinfunction "IN1_A1") (pintype "input"))
      (node (ref "D02") (pin "B1") (pinfunction "P$2_B1") (pintype "bidirectional"))
    )
    (net (code "93") (name "I{slash}O_BAC_01") (class "Default")
      (node (ref "A02") (pin "D1") (pinfunction "P$2_D1") (pintype "bidirectional"))
      (node (ref "C03") (pin "D1") (pinfunction "IN2_D1") (pintype "input"))
      (node (ref "D02") (pin "D1") (pinfunction "P$2_D1") (pintype "bidirectional"))
    )
    (net (code "94") (name "I{slash}O_BAC_02") (class "Default")
      (node (ref "A02") (pin "E1") (pinfunction "P$2_E1") (pintype "bidirectional"))
      (node (ref "C03") (pin "F1") (pinfunction "IN3_F1") (pintype "input"))
      (node (ref "D02") (pin "E1") (pinfunction "P$2_E1") (pintype "bidirectional"))
    )
    (net (code "95") (name "I{slash}O_BAC_03") (class "Default")
      (node (ref "A02") (pin "H1") (pinfunction "P$2_H1") (pintype "bidirectional"))
      (node (ref "C03") (pin "J1") (pinfunction "IN4_J1") (pintype "input"))
      (node (ref "D02") (pin "H1") (pinfunction "P$2_H1") (pintype "bidirectional"))
    )
    (net (code "96") (name "I{slash}O_BAC_04") (class "Default")
      (node (ref "A02") (pin "J1") (pinfunction "P$2_J1") (pintype "bidirectional"))
      (node (ref "C03") (pin "L1") (pinfunction "IN5_L1") (pintype "input"))
      (node (ref "D02") (pin "J1") (pinfunction "P$2_J1") (pintype "bidirectional"))
    )
    (net (code "97") (name "I{slash}O_BAC_05") (class "Default")
      (node (ref "A02") (pin "L1") (pinfunction "P$2_L1") (pintype "bidirectional"))
      (node (ref "C03") (pin "N1") (pinfunction "IN6_N1") (pintype "input"))
      (node (ref "D02") (pin "L1") (pinfunction "P$2_L1") (pintype "bidirectional"))
    )
    (net (code "98") (name "I{slash}O_BAC_06") (class "Default")
      (node (ref "A02") (pin "M1") (pinfunction "P$2_M1") (pintype "bidirectional"))
      (node (ref "C03") (pin "R1") (pinfunction "IN7_R1") (pintype "input"))
      (node (ref "D02") (pin "M1") (pinfunction "P$2_M1") (pintype "bidirectional"))
    )
    (net (code "99") (name "I{slash}O_BAC_07") (class "Default")
      (node (ref "A02") (pin "P1") (pinfunction "P$2_P1") (pintype "bidirectional"))
      (node (ref "C03") (pin "V1") (pinfunction "IN8_V1") (pintype "input"))
      (node (ref "D02") (pin "P1") (pinfunction "P$2_P1") (pintype "bidirectional"))
    )
    (net (code "100") (name "I{slash}O_BAC_08") (class "Default")
      (node (ref "A02") (pin "S1") (pinfunction "P$2_S1") (pintype "bidirectional"))
      (node (ref "C03") (pin "E2") (pinfunction "IN9_E2") (pintype "input"))
      (node (ref "D02") (pin "S1") (pinfunction "P$2_S1") (pintype "bidirectional"))
    )
    (net (code "101") (name "I{slash}O_BAC_09") (class "Default")
      (node (ref "A02") (pin "D2") (pinfunction "P$2_D2") (pintype "bidirectional"))
      (node (ref "C03") (pin "H2") (pinfunction "IN10_H2") (pintype "input"))
      (node (ref "D02") (pin "D2") (pinfunction "P$2_D2") (pintype "bidirectional"))
    )
    (net (code "102") (name "I{slash}O_BAC_10") (class "Default")
      (node (ref "A02") (pin "E2") (pinfunction "P$2_E2") (pintype "bidirectional"))
      (node (ref "C03") (pin "K2") (pinfunction "IN11_K2") (pintype "input"))
      (node (ref "D02") (pin "E2") (pinfunction "P$2_E2") (pintype "bidirectional"))
    )
    (net (code "103") (name "I{slash}O_BAC_11") (class "Default")
      (node (ref "A02") (pin "H2") (pinfunction "P$2_H2") (pintype "bidirectional"))
      (node (ref "C03") (pin "M2") (pinfunction "IN12_M2") (pintype "input"))
      (node (ref "D02") (pin "H2") (pinfunction "P$2_H2") (pintype "bidirectional"))
    )
    (net (code "104") (name "I{slash}O_BMB_00") (class "Default")
      (node (ref "A03") (pin "B1") (pinfunction "P$2_B1") (pintype "bidirectional"))
      (node (ref "C02") (pin "A1") (pinfunction "IN1_A1") (pintype "input"))
      (node (ref "D03") (pin "B1") (pinfunction "P$2_B1") (pintype "bidirectional"))
    )
    (net (code "105") (name "I{slash}O_BMB_01") (class "Default")
      (node (ref "A03") (pin "D1") (pinfunction "P$2_D1") (pintype "bidirectional"))
      (node (ref "C02") (pin "D1") (pinfunction "IN2_D1") (pintype "input"))
      (node (ref "D03") (pin "D1") (pinfunction "P$2_D1") (pintype "bidirectional"))
    )
    (net (code "106") (name "I{slash}O_BMB_02") (class "Default")
      (node (ref "A03") (pin "E1") (pinfunction "P$2_E1") (pintype "bidirectional"))
      (node (ref "C02") (pin "F1") (pinfunction "IN3_F1") (pintype "input"))
      (node (ref "D03") (pin "E1") (pinfunction "P$2_E1") (pintype "bidirectional"))
    )
    (net (code "107") (name "I{slash}O_BMB_03") (class "Default")
      (node (ref "A03") (pin "J1") (pinfunction "P$2_J1") (pintype "bidirectional"))
      (node (ref "C02") (pin "J1") (pinfunction "IN4_J1") (pintype "input"))
      (node (ref "C04") (pin "D2") (pinfunction "D2_D2") (pintype "input"))
      (node (ref "C05") (pin "D2") (pinfunction "D2_D2") (pintype "input"))
      (node (ref "D03") (pin "J1") (pinfunction "P$2_J1") (pintype "bidirectional"))
    )
    (net (code "108") (name "I{slash}O_BMB_04") (class "Default")
      (node (ref "A03") (pin "M1") (pinfunction "P$2_M1") (pintype "bidirectional"))
      (node (ref "C02") (pin "L1") (pinfunction "IN5_L1") (pintype "input"))
      (node (ref "C04") (pin "E2") (pinfunction "E2_E2") (pintype "input"))
      (node (ref "C05") (pin "E2") (pinfunction "E2_E2") (pintype "input"))
      (node (ref "D03") (pin "M1") (pinfunction "P$2_M1") (pintype "bidirectional"))
    )
    (net (code "109") (name "I{slash}O_BMB_05") (class "Default")
      (node (ref "A03") (pin "S1") (pinfunction "P$2_S1") (pintype "bidirectional"))
      (node (ref "C02") (pin "N1") (pinfunction "IN6_N1") (pintype "input"))
      (node (ref "C04") (pin "F2") (pinfunction "F2_F2") (pintype "input"))
      (node (ref "C05") (pin "F2") (pinfunction "F2_F2") (pintype "input"))
      (node (ref "D03") (pin "S1") (pinfunction "P$2_S1") (pintype "bidirectional"))
    )
    (net (code "110") (name "I{slash}O_BMB_06") (class "Default")
      (node (ref "A03") (pin "E2") (pinfunction "P$2_E2") (pintype "bidirectional"))
      (node (ref "C02") (pin "R1") (pinfunction "IN7_R1") (pintype "input"))
      (node (ref "C04") (pin "H2") (pinfunction "H2_H2") (pintype "input"))
      (node (ref "C05") (pin "H2") (pinfunction "H2_H2") (pintype "input"))
      (node (ref "D03") (pin "E2") (pinfunction "P$2_E2") (pintype "bidirectional"))
    )
    (net (code "111") (name "I{slash}O_BMB_07") (class "Default")
      (node (ref "A03") (pin "K2") (pinfunction "P$2_K2") (pintype "bidirectional"))
      (node (ref "C02") (pin "V1") (pinfunction "IN8_V1") (pintype "input"))
      (node (ref "C04") (pin "J2") (pinfunction "J2_J2") (pintype "input"))
      (node (ref "C05") (pin "J2") (pinfunction "J2_J2") (pintype "input"))
      (node (ref "D03") (pin "K2") (pinfunction "P$2_K2") (pintype "bidirectional"))
    )
    (net (code "112") (name "I{slash}O_BMB_08") (class "Default")
      (node (ref "A03") (pin "P2") (pinfunction "P$2_P2") (pintype "bidirectional"))
      (node (ref "C02") (pin "E2") (pinfunction "IN9_E2") (pintype "input"))
      (node (ref "C05") (pin "K2") (pinfunction "K2_K2") (pintype "input"))
      (node (ref "D03") (pin "P2") (pinfunction "P$2_P2") (pintype "bidirectional"))
    )
    (net (code "113") (name "I{slash}O_BMB_09") (class "Default")
      (node (ref "A03") (pin "S2") (pinfunction "P$2_S2") (pintype "bidirectional"))
      (node (ref "C02") (pin "H2") (pinfunction "IN10_H2") (pintype "input"))
      (node (ref "D03") (pin "S2") (pinfunction "P$2_S2") (pintype "bidirectional"))
    )
    (net (code "114") (name "I{slash}O_BMB_10") (class "Default")
      (node (ref "A03") (pin "T2") (pinfunction "P$2_T2") (pintype "bidirectional"))
      (node (ref "C02") (pin "K2") (pinfunction "IN11_K2") (pintype "input"))
      (node (ref "D03") (pin "T2") (pinfunction "P$2_T2") (pintype "bidirectional"))
    )
    (net (code "115") (name "I{slash}O_BMB_11") (class "Default")
      (node (ref "A03") (pin "V2") (pinfunction "P$2_V2") (pintype "bidirectional"))
      (node (ref "C02") (pin "M2") (pinfunction "IN12_M2") (pintype "input"))
      (node (ref "D03") (pin "V2") (pinfunction "P$2_V2") (pintype "bidirectional"))
    )
    (net (code "116") (name "I{slash}O_DATA_IN") (class "Default")
      (node (ref "A05") (pin "M2") (pinfunction "P$2_M2") (pintype "bidirectional"))
      (node (ref "B05") (pin "J2") (pinfunction "E_J2") (pintype "open_collector"))
      (node (ref "D05") (pin "M2") (pinfunction "P$2_M2") (pintype "bidirectional"))
    )
    (net (code "117") (name "I{slash}O_PWR_CLR") (class "Default")
      (node (ref "A02") (pin "V2") (pinfunction "P$2_V2") (pintype "bidirectional"))
      (node (ref "C05") (pin "H1") (pinfunction "IN1_H1") (pintype "input"))
      (node (ref "D02") (pin "V2") (pinfunction "P$2_V2") (pintype "bidirectional"))
    )
    (net (code "118") (name "I{slash}O_TS03") (class "Default")
      (node (ref "A02") (pin "S2") (pinfunction "P$2_S2") (pintype "bidirectional"))
      (node (ref "C04") (pin "H1") (pinfunction "IN1_H1") (pintype "input"))
      (node (ref "D02") (pin "S2") (pinfunction "P$2_S2") (pintype "bidirectional"))
    )
    (net (code "119") (name "I{slash}O_TS04") (class "Default")
      (node (ref "A02") (pin "T2") (pinfunction "P$2_T2") (pintype "bidirectional"))
      (node (ref "D02") (pin "T2") (pinfunction "P$2_T2") (pintype "bidirectional"))
    )
    (net (code "120") (name "I{slash}~{O_0_TO_AC}") (class "Default")
      (node (ref "A04") (pin "P2") (pinfunction "P$2_P2") (pintype "bidirectional"))
      (node (ref "B05") (pin "L1") (pinfunction "E_L1") (pintype "open_collector"))
      (node (ref "D04") (pin "P2") (pinfunction "P$2_P2") (pintype "bidirectional"))
    )
    (net (code "121") (name "I{slash}~{O_1_TO_CA_INH}") (class "Default")
      (node (ref "A06") (pin "M2") (pinfunction "P$2_M2") (pintype "bidirectional"))
      (node (ref "B05") (pin "N2") (pinfunction "D_N2") (pintype "open_collector"))
      (node (ref "D06") (pin "M2") (pinfunction "P$2_M2") (pintype "bidirectional"))
    )
    (net (code "122") (name "I{slash}~{O_ADDR_ACC}") (class "Default")
      (node (ref "A05") (pin "S2") (pinfunction "P$2_S2") (pintype "bidirectional"))
      (node (ref "C02") (pin "U2") (pinfunction "IN15_U2") (pintype "input"))
      (node (ref "D05") (pin "S2") (pinfunction "P$2_S2") (pintype "bidirectional"))
    )
    (net (code "123") (name "I{slash}~{O_BMB_03}") (class "Default")
      (node (ref "A03") (pin "H1") (pinfunction "P$2_H1") (pintype "bidirectional"))
      (node (ref "D03") (pin "H1") (pinfunction "P$2_H1") (pintype "bidirectional"))
    )
    (net (code "124") (name "I{slash}~{O_BMB_04}") (class "Default")
      (node (ref "A03") (pin "L1") (pinfunction "P$2_L1") (pintype "bidirectional"))
      (node (ref "D03") (pin "L1") (pinfunction "P$2_L1") (pintype "bidirectional"))
    )
    (net (code "125") (name "I{slash}~{O_BMB_05}") (class "Default")
      (node (ref "A03") (pin "P1") (pinfunction "P$2_P1") (pintype "bidirectional"))
      (node (ref "D03") (pin "P1") (pinfunction "P$2_P1") (pintype "bidirectional"))
    )
    (net (code "126") (name "I{slash}~{O_BMB_06}") (class "Default")
      (node (ref "A03") (pin "D2") (pinfunction "P$2_D2") (pintype "bidirectional"))
      (node (ref "D03") (pin "D2") (pinfunction "P$2_D2") (pintype "bidirectional"))
    )
    (net (code "127") (name "I{slash}~{O_BMB_07}") (class "Default")
      (node (ref "A03") (pin "H2") (pinfunction "P$2_H2") (pintype "bidirectional"))
      (node (ref "D03") (pin "H2") (pinfunction "P$2_H2") (pintype "bidirectional"))
    )
    (net (code "128") (name "I{slash}~{O_BMB_08}") (class "Default")
      (node (ref "A03") (pin "M2") (pinfunction "P$2_M2") (pintype "bidirectional"))
      (node (ref "C04") (pin "K2") (pinfunction "K2_K2") (pintype "input"))
      (node (ref "D03") (pin "M2") (pinfunction "P$2_M2") (pintype "bidirectional"))
    )
    (net (code "129") (name "I{slash}~{O_BRK_RQ}") (class "Default")
      (node (ref "A05") (pin "K2") (pinfunction "P$2_K2") (pintype "bidirectional"))
      (node (ref "B05") (pin "D1") (pinfunction "D_D1") (pintype "open_collector"))
      (node (ref "D05") (pin "K2") (pinfunction "P$2_K2") (pintype "bidirectional"))
    )
    (net (code "130") (name "I{slash}~{O_BWC0}") (class "Default")
      (node (ref "A06") (pin "P2") (pinfunction "P$2_P2") (pintype "bidirectional"))
      (node (ref "C01") (pin "F1") (pinfunction "IN_F1") (pintype "input"))
      (node (ref "D06") (pin "P2") (pinfunction "P$2_P2") (pintype "bidirectional"))
    )
    (net (code "131") (name "I{slash}~{O_INT_RQ}") (class "Default")
      (node (ref "A04") (pin "M2") (pinfunction "P$2_M2") (pintype "bidirectional"))
      (node (ref "B05") (pin "E1") (pinfunction "E_E1") (pintype "open_collector"))
      (node (ref "D04") (pin "M2") (pinfunction "P$2_M2") (pintype "bidirectional"))
    )
    (net (code "132") (name "I{slash}~{O_SKP_RQ}") (class "Default")
      (node (ref "A04") (pin "K2") (pinfunction "P$2_K2") (pintype "bidirectional"))
      (node (ref "B05") (pin "K1") (pinfunction "D_K1") (pintype "open_collector"))
      (node (ref "D04") (pin "K2") (pinfunction "P$2_K2") (pintype "bidirectional"))
    )
    (net (code "133") (name "LDMF") (class "Default")
      (node (ref "C05") (pin "E1") (pinfunction "E1_E1") (pintype "output"))
      (node (ref "D11") (pin "B1") (pinfunction "C_B1") (pintype "input"))
      (node (ref "D11") (pin "D2") (pinfunction "C_D2") (pintype "input"))
      (node (ref "D11") (pin "H1") (pinfunction "C_H1") (pintype "input"))
    )
    (net (code "134") (name "LPB_00") (class "Default")
      (node (ref "A25") (pin "T2") (pinfunction "P$2_T2") (pintype "bidirectional"))
      (node (ref "C08") (pin "D1") (pinfunction "IN2B_D1") (pintype "input"))
      (node (ref "D08") (pin "E1") (pinfunction "E1_E1") (pintype "output"))
    )
    (net (code "135") (name "LPB_01") (class "Default")
      (node (ref "A25") (pin "U2") (pinfunction "P$2_U2") (pintype "bidirectional"))
      (node (ref "C08") (pin "K1") (pinfunction "IN2B_K1") (pintype "input"))
      (node (ref "D08") (pin "L1") (pinfunction "L1_L1") (pintype "output"))
    )
    (net (code "136") (name "LPB_02") (class "Default")
      (node (ref "A25") (pin "V2") (pinfunction "P$2_V2") (pintype "bidirectional"))
      (node (ref "C08") (pin "R1") (pinfunction "IN2B_R1") (pintype "input"))
      (node (ref "D08") (pin "S1") (pinfunction "S1_S1") (pintype "output"))
    )
    (net (code "137") (name "LPB_03") (class "Default")
      (node (ref "A26") (pin "A2") (pinfunction "P$2_A2") (pintype "bidirectional"))
      (node (ref "C08") (pin "H2") (pinfunction "IN2B_H2") (pintype "input"))
      (node (ref "D08") (pin "H2") (pinfunction "H2_H2") (pintype "output"))
    )
    (net (code "138") (name "LPB_04") (class "Default")
      (node (ref "A26") (pin "B2") (pinfunction "P$2_B2") (pintype "bidirectional"))
      (node (ref "C08") (pin "N2") (pinfunction "IN2B_N2") (pintype "input"))
      (node (ref "D08") (pin "P2") (pinfunction "P2_P2") (pintype "output"))
    )
    (net (code "139") (name "LPB_05") (class "Default")
      (node (ref "A26") (pin "C2") (pinfunction "P$2_C2") (pintype "bidirectional"))
      (node (ref "C08") (pin "U2") (pinfunction "IN2B_U2") (pintype "input"))
      (node (ref "D08") (pin "V2") (pinfunction "V2_V2") (pintype "output"))
    )
    (net (code "140") (name "LPB_NOT_EQ_1") (class "Default")
      (node (ref "A10") (pin "M1") (pinfunction "IN2_M1") (pintype "input"))
      (node (ref "D10") (pin "V2") (pinfunction "OUT_V2") (pintype "output"))
    )
    (net (code "141") (name "LPB_TO_DTB") (class "Default")
      (node (ref "A11") (pin "T2") (pinfunction "OUT_T2") (pintype "output"))
      (node (ref "C08") (pin "C1") (pinfunction "IN2A_C1") (pintype "input"))
      (node (ref "C08") (pin "F2") (pinfunction "IN2A_F2") (pintype "input"))
      (node (ref "C08") (pin "J1") (pinfunction "IN2A_J1") (pintype "input"))
      (node (ref "C08") (pin "M2") (pinfunction "IN2A_M2") (pintype "input"))
      (node (ref "C08") (pin "P1") (pinfunction "IN2A_P1") (pintype "input"))
      (node (ref "C08") (pin "T2") (pinfunction "IN2A_T2") (pintype "input"))
    )
    (net (code "142") (name "MC00") (class "Default")
      (node (ref "A26") (pin "S1") (pinfunction "P$2_S1") (pintype "bidirectional"))
      (node (ref "B13") (pin "E1") (pinfunction "1_E1") (pintype "output"))
      (node (ref "B13") (pin "E2") (pinfunction "D_E2") (pintype "input"))
      (node (ref "D10") (pin "D2") (pinfunction "IN5_D2") (pintype "input"))
    )
    (net (code "143") (name "MC01") (class "Default")
      (node (ref "A08") (pin "L2") (pinfunction "C_L2") (pintype "input"))
      (node (ref "A26") (pin "T1") (pinfunction "P$2_T1") (pintype "bidirectional"))
      (node (ref "B13") (pin "H2") (pinfunction "1_H2") (pintype "output"))
      (node (ref "B13") (pin "J1") (pinfunction "D_J1") (pintype "input"))
      (node (ref "C11") (pin "E1") (pinfunction "IN2_E1") (pintype "input"))
    )
    (net (code "144") (name "MC02") (class "Default")
      (node (ref "A26") (pin "U1") (pinfunction "P$2_U1") (pintype "bidirectional"))
      (node (ref "B11") (pin "U2") (pinfunction "IN2_U2") (pintype "input"))
      (node (ref "B13") (pin "L1") (pinfunction "1_L1") (pintype "output"))
      (node (ref "D12") (pin "D2") (pinfunction "IN1_D2") (pintype "input"))
      (node (ref "D12") (pin "E2") (pinfunction "IN2_E2") (pintype "input"))
    )
    (net (code "145") (name "MF00") (class "Default")
      (node (ref "A25") (pin "V1") (pinfunction "P$2_V1") (pintype "bidirectional"))
      (node (ref "D11") (pin "E1") (pinfunction "1_E1") (pintype "output"))
    )
    (net (code "146") (name "MF01") (class "Default")
      (node (ref "A26") (pin "A1") (pinfunction "P$2_A1") (pintype "bidirectional"))
      (node (ref "D11") (pin "H2") (pinfunction "1_H2") (pintype "output"))
    )
    (net (code "147") (name "MF02") (class "Default")
      (node (ref "A26") (pin "B1") (pinfunction "P$2_B1") (pintype "bidirectional"))
      (node (ref "D11") (pin "L1") (pinfunction "1_L1") (pintype "output"))
    )
    (net (code "148") (name "MKT") (class "Default")
      (node (ref "A26") (pin "H2") (pinfunction "P$2_H2") (pintype "bidirectional"))
      (node (ref "B12") (pin "S2") (pinfunction "IN2_S2") (pintype "input"))
      (node (ref "B13") (pin "V2") (pinfunction "1_V2") (pintype "output"))
      (node (ref "B15") (pin "L1") (pinfunction "IN1_L1") (pintype "input"))
      (node (ref "C15") (pin "L2") (pinfunction "IN1_L2") (pintype "input"))
    )
    (net (code "149") (name "MKTK") (class "Default")
      (node (ref "A08") (pin "R2") (pinfunction "0_R2") (pintype "output"))
      (node (ref "A25") (pin "P1") (pinfunction "P$2_P1") (pintype "bidirectional"))
    )
    (net (code "150") (name "MK_BLK_END") (class "Default")
      (node (ref "A09") (pin "T2") (pinfunction "IN3_T2") (pintype "input"))
      (node (ref "CD18") (pin "BU1") (pinfunction "BU1_BU1") (pintype "output"))
    )
    (net (code "151") (name "MK_BLK_MK") (class "Default")
      (node (ref "CD18") (pin "AE2") (pinfunction "AE2_AE2") (pintype "output"))
      (node (ref "D10") (pin "A1") (pinfunction "IN1_A1") (pintype "input"))
      (node (ref "D10") (pin "B1") (pinfunction "IN2_B1") (pintype "input"))
    )
    (net (code "152") (name "MK_BLK_START") (class "Default")
      (node (ref "CD18") (pin "AJ2") (pinfunction "AJ2_AJ2") (pintype "output"))
    )
    (net (code "153") (name "MK_BLK_SYNC") (class "Default")
      (node (ref "CD18") (pin "BS2") (pinfunction "BS2_BS2") (pintype "output"))
    )
    (net (code "154") (name "MK_DATA") (class "Default")
      (node (ref "CD18") (pin "BP2") (pinfunction "BP2_BP2") (pintype "output"))
    )
    (net (code "155") (name "MK_DATA_SYNC") (class "Default")
      (node (ref "CD18") (pin "AH1") (pinfunction "AH1_AH1") (pintype "output"))
    )
    (net (code "156") (name "MK_END") (class "Default")
      (node (ref "A08") (pin "C1") (pinfunction "D_C1") (pintype "input"))
      (node (ref "CD18") (pin "AF2") (pinfunction "AF2_AF2") (pintype "output"))
    )
    (net (code "157") (name "MOVE") (class "Default")
      (node (ref "D07") (pin "D2") (pinfunction "O0_D2") (pintype "output"))
    )
    (net (code "158") (name "MR00") (class "Default")
      (node (ref "A25") (pin "D1") (pinfunction "P$2_D1") (pintype "bidirectional"))
      (node (ref "B07") (pin "P2") (pinfunction "P2_P2") (pintype "output"))
      (node (ref "B14") (pin "M2") (pinfunction "D_M2") (pintype "input"))
    )
    (net (code "159") (name "MR01") (class "Default")
      (node (ref "A25") (pin "E1") (pinfunction "P$2_E1") (pintype "bidirectional"))
      (node (ref "C07") (pin "P2") (pinfunction "P2_P2") (pintype "output"))
      (node (ref "C12") (pin "B1") (pinfunction "IN2_B1") (pintype "input"))
    )
    (net (code "160") (name "Net-(A08D-D)") (class "Default")
      (node (ref "A08") (pin "E2") (pinfunction "D_E2") (pintype "input"))
      (node (ref "A09") (pin "L1") (pinfunction "OUT_L1") (pintype "output"))
    )
    (net (code "161") (name "Net-(A08E-S)") (class "Default")
      (node (ref "A08") (pin "K1") (pinfunction "S_K1") (pintype "input"))
      (node (ref "A11") (pin "E1") (pinfunction "OUT_E1") (pintype "output"))
    )
    (net (code "162") (name "Net-(A08F-D)") (class "Default")
      (node (ref "A08") (pin "M2") (pinfunction "D_M2") (pintype "input"))
      (node (ref "A09") (pin "J2") (pinfunction "OUT_J2") (pintype "output"))
    )
    (net (code "163") (name "Net-(A08G-C)") (class "Default")
      (node (ref "A08") (pin "N1") (pinfunction "C_N1") (pintype "input"))
      (node (ref "A11") (pin "D2") (pinfunction "OUT_D2") (pintype "output"))
    )
    (net (code "164") (name "Net-(A08G-D)") (class "Default")
      (node (ref "A08") (pin "P1") (pinfunction "D_P1") (pintype "input"))
      (node (ref "A10") (pin "N1") (pinfunction "OUT_N1") (pintype "output"))
    )
    (net (code "165") (name "Net-(A08H-S)") (class "Default")
      (node (ref "A08") (pin "U2") (pinfunction "S_U2") (pintype "input"))
      (node (ref "B10") (pin "S1") (pinfunction "OUT_S1") (pintype "output"))
    )
    (net (code "166") (name "Net-(A09A-OUT)") (class "Default")
      (node (ref "A09") (pin "E1") (pinfunction "OUT_E1") (pintype "output"))
      (node (ref "A11") (pin "A1") (pinfunction "IN_A1") (pintype "input"))
    )
    (net (code "167") (name "Net-(A09D-IN4)") (class "Default")
      (node (ref "A09") (pin "H2") (pinfunction "IN4_H2") (pintype "input"))
      (node (ref "A11") (pin "B1") (pinfunction "OUT_B1") (pintype "output"))
    )
    (net (code "168") (name "Net-(A09E-IN1)") (class "Default")
      (node (ref "A09") (pin "F1") (pinfunction "IN1_F1") (pintype "input"))
      (node (ref "C10") (pin "P2") (pinfunction "OUT_P2") (pintype "output"))
    )
    (net (code "169") (name "Net-(A09E-IN3)") (class "Default")
      (node (ref "A09") (pin "J1") (pinfunction "IN3_J1") (pintype "input"))
      (node (ref "A10") (pin "K1") (pinfunction "OUT_K1") (pintype "output"))
    )
    (net (code "170") (name "Net-(A09F-OUT)") (class "Default")
      (node (ref "A09") (pin "P2") (pinfunction "OUT_P2") (pintype "output"))
      (node (ref "A11") (pin "F1") (pinfunction "IN_F1") (pintype "input"))
    )
    (net (code "171") (name "Net-(A09G-OUT)") (class "Default")
      (node (ref "A09") (pin "S1") (pinfunction "OUT_S1") (pintype "output"))
      (node (ref "A10") (pin "U2") (pinfunction "IN2_U2") (pintype "input"))
    )
    (net (code "172") (name "Net-(A09J-IN4)") (class "Default")
      (node (ref "A09") (pin "U2") (pinfunction "IN4_U2") (pintype "input"))
      (node (ref "C17") (pin "R2") (pinfunction "OUT_R2") (pintype "output"))
    )
    (net (code "173") (name "Net-(A09J-OUT)") (class "Default")
      (node (ref "A09") (pin "V2") (pinfunction "OUT_V2") (pintype "output"))
      (node (ref "A11") (pin "S2") (pinfunction "IN_S2") (pintype "input"))
    )
    (net (code "174") (name "Net-(A10A-IN2)") (class "Default")
      (node (ref "A10") (pin "B1") (pinfunction "IN2_B1") (pintype "input"))
      (node (ref "A10") (pin "F1") (pinfunction "OUT_F1") (pintype "output"))
      (node (ref "B15") (pin "P2") (pinfunction "IN1_P2") (pintype "input"))
    )
    (net (code "175") (name "Net-(A10A-OUT)") (class "Default")
      (node (ref "A10") (pin "C1") (pinfunction "OUT_C1") (pintype "output"))
      (node (ref "A10") (pin "D1") (pinfunction "IN1_D1") (pintype "input"))
    )
    (net (code "176") (name "Net-(A10C-OUT)") (class "Default")
      (node (ref "A10") (pin "F2") (pinfunction "OUT_F2") (pintype "output"))
      (node (ref "A10") (pin "J2") (pinfunction "IN2_J2") (pintype "input"))
    )
    (net (code "177") (name "Net-(A10J-OUT)") (class "Default")
      (node (ref "A10") (pin "S1") (pinfunction "OUT_S1") (pintype "output"))
      (node (ref "A11") (pin "C1") (pinfunction "IN_C1") (pintype "input"))
    )
    (net (code "178") (name "Net-(A10K-OUT)") (class "Default")
      (node (ref "A10") (pin "S2") (pinfunction "OUT_S2") (pintype "output"))
      (node (ref "A10") (pin "T2") (pinfunction "IN1_T2") (pintype "input"))
    )
    (net (code "179") (name "Net-(A10N-OUT)") (class "Default")
      (node (ref "A10") (pin "V2") (pinfunction "OUT_V2") (pintype "output"))
      (node (ref "A11") (pin "D1") (pinfunction "IN_D1") (pintype "input"))
    )
    (net (code "180") (name "Net-(A11G-OUT)") (class "Default")
      (node (ref "A11") (pin "H1") (pinfunction "OUT_H1") (pintype "output"))
      (node (ref "A12") (pin "B1") (pinfunction "IN2_B1") (pintype "input"))
      (node (ref "A12") (pin "D1") (pinfunction "IN1_D1") (pintype "input"))
    )
    (net (code "181") (name "Net-(A11N-IN)") (class "Default")
      (node (ref "A11") (pin "P2") (pinfunction "IN_P2") (pintype "input"))
      (node (ref "A14") (pin "F2") (pinfunction "F2_F2") (pintype "output"))
    )
    (net (code "182") (name "Net-(A11O-IN)") (class "Default")
      (node (ref "A11") (pin "R1") (pinfunction "IN_R1") (pintype "input"))
      (node (ref "B11") (pin "S2") (pinfunction "OUT_S2") (pintype "output"))
    )
    (net (code "183") (name "Net-(A11Q-IN)") (class "Default")
      (node (ref "A11") (pin "V1") (pinfunction "IN_V1") (pintype "input"))
      (node (ref "B08") (pin "V2") (pinfunction "OUT_V2") (pintype "output"))
    )
    (net (code "184") (name "Net-(A11R-IN)") (class "Default")
      (node (ref "A11") (pin "U2") (pinfunction "IN_U2") (pintype "input"))
      (node (ref "A14") (pin "T2") (pinfunction "F2_T2") (pintype "output"))
    )
    (net (code "185") (name "Net-(A12C-OUT)") (class "Default")
      (node (ref "A12") (pin "F2") (pinfunction "OUT_F2") (pintype "output"))
      (node (ref "B10") (pin "A1") (pinfunction "IN1_A1") (pintype "input"))
      (node (ref "B10") (pin "B1") (pinfunction "IN2_B1") (pintype "input"))
    )
    (net (code "186") (name "Net-(A12F-IN2)") (class "Default")
      (node (ref "A12") (pin "J1") (pinfunction "IN2_J1") (pintype "input"))
      (node (ref "A12") (pin "N1") (pinfunction "OUT_N1") (pintype "output"))
      (node (ref "A12") (pin "P1") (pinfunction "IN1_P1") (pintype "input"))
    )
    (net (code "187") (name "Net-(A12G-OUT)") (class "Default")
      (node (ref "A12") (pin "K2") (pinfunction "OUT_K2") (pintype "output"))
      (node (ref "B10") (pin "C1") (pinfunction "IN3_C1") (pintype "input"))
      (node (ref "B10") (pin "D1") (pinfunction "IN4_D1") (pintype "input"))
    )
    (net (code "188") (name "Net-(A12I-OUT)") (class "Default")
      (node (ref "A12") (pin "N2") (pinfunction "OUT_N2") (pintype "output"))
      (node (ref "A12") (pin "T2") (pinfunction "IN1_T2") (pintype "input"))
    )
    (net (code "189") (name "Net-(A12K-OUT)") (class "Default")
      (node (ref "A12") (pin "S2") (pinfunction "OUT_S2") (pintype "output"))
      (node (ref "A12") (pin "U2") (pinfunction "IN2_U2") (pintype "input"))
    )
    (net (code "190") (name "Net-(A14-PadD2)") (class "Default")
      (node (ref "A14") (pin "D2") (pinfunction "D2_D2") (pintype "passive"))
      (node (ref "A14") (pin "E2") (pinfunction "E2_E2") (pintype "passive"))
    )
    (net (code "191") (name "Net-(A14-PadH1)") (class "Default")
      (node (ref "A14") (pin "H1") (pinfunction "H1_H1") (pintype "passive"))
      (node (ref "A14") (pin "L2") (pinfunction "L2_L2") (pintype "passive"))
    )
    (net (code "192") (name "Net-(A14D-D2)") (class "Default")
      (node (ref "A14") (pin "R2") (pinfunction "E2_R2") (pintype "passive"))
      (node (ref "A14") (pin "V2") (pinfunction "D2_V2") (pintype "passive"))
    )
    (net (code "193") (name "Net-(A14D-H1)") (class "Default")
      (node (ref "A14") (pin "S1") (pinfunction "H1_S1") (pintype "passive"))
      (node (ref "A14") (pin "S2") (pinfunction "L2_S2") (pintype "passive"))
    )
    (net (code "194") (name "Net-(A14D-H2)") (class "Default")
      (node (ref "A14") (pin "M2") (pinfunction "H2_M2") (pintype "input"))
      (node (ref "A14") (pin "N2") (pinfunction "J2_N2") (pintype "input"))
      (node (ref "A14") (pin "P2") (pinfunction "K2_P2") (pintype "input"))
      (node (ref "B15") (pin "F2") (pinfunction "OUT_F2") (pintype "output"))
    )
    (net (code "195") (name "Net-(A15A-IN3)") (class "Default")
      (node (ref "A15") (pin "C1") (pinfunction "IN3_C1") (pintype "input"))
      (node (ref "A15") (pin "D1") (pinfunction "IN4_D1") (pintype "input"))
      (node (ref "C17") (pin "D2") (pinfunction "OUT_D2") (pintype "output"))
    )
    (net (code "196") (name "Net-(A15D-IN1)") (class "Default")
      (node (ref "A15") (pin "D2") (pinfunction "IN1_D2") (pintype "input"))
      (node (ref "A15") (pin "E2") (pinfunction "IN2_E2") (pintype "input"))
      (node (ref "C17") (pin "F2") (pinfunction "OUT_F2") (pintype "output"))
    )
    (net (code "197") (name "Net-(A16-PadD2)") (class "Default")
      (node (ref "A16") (pin "D2") (pinfunction "D2_D2") (pintype "passive"))
      (node (ref "A16") (pin "E2") (pinfunction "E2_E2") (pintype "passive"))
    )
    (net (code "198") (name "Net-(A16C-D2)") (class "Default")
      (node (ref "A16") (pin "R2") (pinfunction "E2_R2") (pintype "passive"))
      (node (ref "A16") (pin "S2") (pinfunction "D2_S2") (pintype "passive"))
    )
    (net (code "199") (name "Net-(AB19A-P$2)") (class "Default")
      (node (ref "A18") (pin "D2") (pinfunction "D2_D2") (pintype "input"))
      (node (ref "A18") (pin "J2") (pinfunction "J2_J2") (pintype "output"))
      (node (ref "AB19") (pin "AF2") (pinfunction "P$2_AF2") (pintype "bidirectional"))
    )
    (net (code "200") (name "Net-(AB19B-P$2)") (class "Default")
      (node (ref "A18") (pin "E2") (pinfunction "E2_E2") (pintype "input"))
      (node (ref "A18") (pin "K2") (pinfunction "K2_K2") (pintype "output"))
      (node (ref "AB19") (pin "AH2") (pinfunction "P$2_AH2") (pintype "bidirectional"))
    )
    (net (code "201") (name "Net-(AB19D-P$2)") (class "Default")
      (node (ref "AB19") (pin "AN2") (pinfunction "P$2_AN2") (pintype "bidirectional"))
      (node (ref "B18") (pin "D2") (pinfunction "D2_D2") (pintype "input"))
      (node (ref "B18") (pin "J2") (pinfunction "J2_J2") (pintype "output"))
    )
    (net (code "202") (name "Net-(AB19E-P$2)") (class "Default")
      (node (ref "AB19") (pin "AP2") (pinfunction "P$2_AP2") (pintype "bidirectional"))
      (node (ref "B18") (pin "E2") (pinfunction "E2_E2") (pintype "input"))
      (node (ref "B18") (pin "K2") (pinfunction "K2_K2") (pintype "output"))
    )
    (net (code "203") (name "Net-(AB19H-P$2)") (class "Default")
      (node (ref "A20") (pin "D2") (pinfunction "D2_D2") (pintype "input"))
      (node (ref "A20") (pin "J2") (pinfunction "J2_J2") (pintype "output"))
      (node (ref "AB19") (pin "AV2") (pinfunction "P$2_AV2") (pintype "bidirectional"))
    )
    (net (code "204") (name "Net-(AB19I-P$2)") (class "Default")
      (node (ref "A20") (pin "E2") (pinfunction "E2_E2") (pintype "input"))
      (node (ref "A20") (pin "K2") (pinfunction "K2_K2") (pintype "output"))
      (node (ref "AB19") (pin "BD2") (pinfunction "P$2_BD2") (pintype "bidirectional"))
    )
    (net (code "205") (name "Net-(AB19K-P$2)") (class "Default")
      (node (ref "AB19") (pin "BH2") (pinfunction "P$2_BH2") (pintype "bidirectional"))
      (node (ref "B20") (pin "D2") (pinfunction "D2_D2") (pintype "input"))
      (node (ref "B20") (pin "J2") (pinfunction "J2_J2") (pintype "output"))
    )
    (net (code "206") (name "Net-(AB19L-P$2)") (class "Default")
      (node (ref "AB19") (pin "BJ2") (pinfunction "P$2_BJ2") (pintype "bidirectional"))
      (node (ref "B20") (pin "E2") (pinfunction "E2_E2") (pintype "input"))
      (node (ref "B20") (pin "K2") (pinfunction "K2_K2") (pintype "output"))
    )
    (net (code "207") (name "Net-(AB19N-P$2)") (class "Default")
      (node (ref "A21") (pin "D2") (pinfunction "D2_D2") (pintype "input"))
      (node (ref "A21") (pin "J2") (pinfunction "J2_J2") (pintype "output"))
      (node (ref "AB19") (pin "BN2") (pinfunction "P$2_BN2") (pintype "bidirectional"))
    )
    (net (code "208") (name "Net-(AB19O-P$2)") (class "Default")
      (node (ref "A21") (pin "E2") (pinfunction "E2_E2") (pintype "input"))
      (node (ref "A21") (pin "K2") (pinfunction "K2_K2") (pintype "output"))
      (node (ref "AB19") (pin "BP2") (pinfunction "P$2_BP2") (pintype "bidirectional"))
    )
    (net (code "209") (name "Net-(B06P-IN)") (class "Default")
      (node (ref "B06") (pin "S2") (pinfunction "IN_S2") (pintype "input"))
      (node (ref "B08") (pin "S2") (pinfunction "OUT_S2") (pintype "output"))
    )
    (net (code "210") (name "Net-(B08A-OUT)") (class "Default")
      (node (ref "B08") (pin "C1") (pinfunction "OUT_C1") (pintype "output"))
      (node (ref "B09") (pin "D1") (pinfunction "S_D1") (pintype "input"))
    )
    (net (code "211") (name "Net-(B08B-OUT)") (class "Default")
      (node (ref "B08") (pin "F1") (pinfunction "OUT_F1") (pintype "output"))
      (node (ref "B09") (pin "U2") (pinfunction "S_U2") (pintype "input"))
    )
    (net (code "212") (name "Net-(B08C-OUT)") (class "Default")
      (node (ref "B08") (pin "F2") (pinfunction "OUT_F2") (pintype "output"))
      (node (ref "B09") (pin "K1") (pinfunction "S_K1") (pintype "input"))
    )
    (net (code "213") (name "Net-(B08F-OUT)") (class "Default")
      (node (ref "B08") (pin "K1") (pinfunction "OUT_K1") (pintype "output"))
      (node (ref "B09") (pin "F2") (pinfunction "S_F2") (pintype "input"))
    )
    (net (code "214") (name "Net-(B08H-OUT)") (class "Default")
      (node (ref "B08") (pin "N1") (pinfunction "OUT_N1") (pintype "output"))
      (node (ref "B09") (pin "N2") (pinfunction "S_N2") (pintype "input"))
    )
    (net (code "215") (name "Net-(B08J-OUT)") (class "Default")
      (node (ref "B08") (pin "S1") (pinfunction "OUT_S1") (pintype "output"))
      (node (ref "B09") (pin "R1") (pinfunction "S_R1") (pintype "input"))
    )
    (net (code "216") (name "Net-(B10E-IN1)") (class "Default")
      (node (ref "B10") (pin "F1") (pinfunction "IN1_F1") (pintype "input"))
      (node (ref "B11") (pin "J1") (pinfunction "OUT_J1") (pintype "output"))
    )
    (net (code "217") (name "Net-(B10E-IN4)") (class "Default")
      (node (ref "B10") (pin "K1") (pinfunction "IN4_K1") (pintype "input"))
      (node (ref "C17") (pin "H1") (pinfunction "OUT_H1") (pintype "output"))
    )
    (net (code "218") (name "Net-(B11A-OUT)") (class "Default")
      (node (ref "B11") (pin "D1") (pinfunction "OUT_D1") (pintype "output"))
      (node (ref "B11") (pin "F2") (pinfunction "IN3_F2") (pintype "input"))
    )
    (net (code "219") (name "Net-(B11D-IN1)") (class "Default")
      (node (ref "B11") (pin "D2") (pinfunction "IN1_D2") (pintype "input"))
      (node (ref "B12") (pin "E1") (pinfunction "OUT_E1") (pintype "output"))
    )
    (net (code "220") (name "Net-(B11D-IN2)") (class "Default")
      (node (ref "B11") (pin "E2") (pinfunction "IN2_E2") (pintype "input"))
      (node (ref "B12") (pin "L1") (pinfunction "OUT_L1") (pintype "output"))
    )
    (net (code "221") (name "Net-(B11D-OUT)") (class "Default")
      (node (ref "B11") (pin "H2") (pinfunction "OUT_H2") (pintype "output"))
      (node (ref "C13") (pin "C1") (pinfunction "IN_C1") (pintype "input"))
    )
    (net (code "222") (name "Net-(B11E-IN1)") (class "Default")
      (node (ref "B11") (pin "E1") (pinfunction "IN1_E1") (pintype "input"))
      (node (ref "B11") (pin "U1") (pinfunction "OUT_U1") (pintype "output"))
    )
    (net (code "223") (name "Net-(B11E-IN3)") (class "Default")
      (node (ref "B11") (pin "H1") (pinfunction "IN3_H1") (pintype "input"))
      (node (ref "B11") (pin "N1") (pinfunction "OUT_N1") (pintype "output"))
    )
    (net (code "224") (name "Net-(B11F-IN3)") (class "Default")
      (node (ref "B11") (pin "L2") (pinfunction "IN3_L2") (pintype "input"))
      (node (ref "B15") (pin "S2") (pinfunction "OUT_S2") (pintype "output"))
    )
    (net (code "225") (name "Net-(B11J-OUT)") (class "Default")
      (node (ref "B11") (pin "V1") (pinfunction "OUT_V1") (pintype "output"))
      (node (ref "C17") (pin "J1") (pinfunction "IN_J1") (pintype "input"))
    )
    (net (code "226") (name "Net-(B12D-OUT)") (class "Default")
      (node (ref "B12") (pin "J2") (pinfunction "OUT_J2") (pintype "output"))
      (node (ref "B12") (pin "N2") (pinfunction "IN4_N2") (pintype "input"))
    )
    (net (code "227") (name "Net-(B12F-IN1)") (class "Default")
      (node (ref "B12") (pin "K2") (pinfunction "IN1_K2") (pintype "input"))
      (node (ref "C12") (pin "N1") (pinfunction "OUT_N1") (pintype "output"))
    )
    (net (code "228") (name "Net-(B12F-IN2)") (class "Default")
      (node (ref "B12") (pin "L2") (pinfunction "IN2_L2") (pintype "input"))
      (node (ref "C12") (pin "U1") (pinfunction "OUT_U1") (pintype "output"))
    )
    (net (code "229") (name "Net-(B12F-IN3)") (class "Default")
      (node (ref "B12") (pin "M2") (pinfunction "IN3_M2") (pintype "input"))
      (node (ref "C12") (pin "V1") (pinfunction "OUT_V1") (pintype "output"))
    )
    (net (code "230") (name "Net-(B12G-IN1)") (class "Default")
      (node (ref "B12") (pin "M1") (pinfunction "IN1_M1") (pintype "input"))
      (node (ref "C11") (pin "C1") (pinfunction "OUT_C1") (pintype "output"))
    )
    (net (code "231") (name "Net-(B12G-IN4)") (class "Default")
      (node (ref "B12") (pin "R1") (pinfunction "IN4_R1") (pintype "input"))
      (node (ref "C11") (pin "F1") (pinfunction "OUT_F1") (pintype "output"))
    )
    (net (code "232") (name "Net-(B12G-OUT)") (class "Default")
      (node (ref "B12") (pin "S1") (pinfunction "OUT_S1") (pintype "output"))
      (node (ref "C11") (pin "P1") (pinfunction "IN1_P1") (pintype "input"))
    )
    (net (code "233") (name "Net-(B12J-IN4)") (class "Default")
      (node (ref "B12") (pin "U2") (pinfunction "IN4_U2") (pintype "input"))
      (node (ref "C11") (pin "N1") (pinfunction "OUT_N1") (pintype "output"))
    )
    (net (code "234") (name "Net-(B12J-OUT)") (class "Default")
      (node (ref "B12") (pin "V2") (pinfunction "OUT_V2") (pintype "output"))
      (node (ref "C12") (pin "F1") (pinfunction "IN2_F1") (pintype "input"))
    )
    (net (code "235") (name "Net-(B13F-S)") (class "Default")
      (node (ref "B13") (pin "N2") (pinfunction "S_N2") (pintype "input"))
      (node (ref "B15") (pin "K1") (pinfunction "OUT_K1") (pintype "output"))
    )
    (net (code "236") (name "Net-(B14G-C)") (class "Default")
      (node (ref "B14") (pin "N1") (pinfunction "C_N1") (pintype "input"))
      (node (ref "B14") (pin "S2") (pinfunction "C_S2") (pintype "input"))
      (node (ref "D15") (pin "D2") (pinfunction "D2_D2") (pintype "output"))
    )
    (net (code "237") (name "Net-(B15B-OUT)") (class "Default")
      (node (ref "A14") (pin "H2") (pinfunction "H2_H2") (pintype "input"))
      (node (ref "A14") (pin "J2") (pinfunction "J2_J2") (pintype "input"))
      (node (ref "A14") (pin "K2") (pinfunction "K2_K2") (pintype "input"))
      (node (ref "B15") (pin "F1") (pinfunction "OUT_F1") (pintype "output"))
    )
    (net (code "238") (name "Net-(B15H-OUT)") (class "Default")
      (node (ref "B15") (pin "N1") (pinfunction "OUT_N1") (pintype "output"))
      (node (ref "C17") (pin "F1") (pinfunction "IN_F1") (pintype "input"))
    )
    (net (code "239") (name "Net-(B15J-OUT)") (class "Default")
      (node (ref "B15") (pin "S1") (pinfunction "OUT_S1") (pintype "output"))
      (node (ref "C17") (pin "L1") (pinfunction "IN_L1") (pintype "input"))
    )
    (net (code "240") (name "Net-(B16-PadD2)") (class "Default")
      (node (ref "B16") (pin "D2") (pinfunction "D2_D2") (pintype "passive"))
      (node (ref "B16") (pin "E2") (pinfunction "E2_E2") (pintype "passive"))
    )
    (net (code "241") (name "Net-(B16C-D2)") (class "Default")
      (node (ref "B16") (pin "R2") (pinfunction "E2_R2") (pintype "passive"))
      (node (ref "B16") (pin "S2") (pinfunction "D2_S2") (pintype "passive"))
    )
    (net (code "242") (name "Net-(C08A-OUT)") (class "Default")
      (node (ref "C08") (pin "E1") (pinfunction "OUT_E1") (pintype "output"))
      (node (ref "C09") (pin "D1") (pinfunction "S_D1") (pintype "input"))
    )
    (net (code "243") (name "Net-(C08D-OUT)") (class "Default")
      (node (ref "C08") (pin "J2") (pinfunction "OUT_J2") (pintype "output"))
      (node (ref "C09") (pin "N2") (pinfunction "S_N2") (pintype "input"))
    )
    (net (code "244") (name "Net-(C08E-OUT)") (class "Default")
      (node (ref "C08") (pin "L1") (pinfunction "OUT_L1") (pintype "output"))
      (node (ref "C09") (pin "F2") (pinfunction "S_F2") (pintype "input"))
    )
    (net (code "245") (name "Net-(C08F-OUT)") (class "Default")
      (node (ref "C08") (pin "P2") (pinfunction "OUT_P2") (pintype "output"))
      (node (ref "C09") (pin "R1") (pinfunction "S_R1") (pintype "input"))
    )
    (net (code "246") (name "Net-(C08G-OUT)") (class "Default")
      (node (ref "C08") (pin "S1") (pinfunction "OUT_S1") (pintype "output"))
      (node (ref "C09") (pin "K1") (pinfunction "S_K1") (pintype "input"))
    )
    (net (code "247") (name "Net-(C08J-OUT)") (class "Default")
      (node (ref "C08") (pin "V2") (pinfunction "OUT_V2") (pintype "output"))
      (node (ref "C09") (pin "U2") (pinfunction "S_U2") (pintype "input"))
    )
    (net (code "248") (name "Net-(C10A-OUT)") (class "Default")
      (node (ref "C10") (pin "E1") (pinfunction "OUT_E1") (pintype "output"))
      (node (ref "C14") (pin "C1") (pinfunction "D_C1") (pintype "input"))
    )
    (net (code "249") (name "Net-(C10D-OUT)") (class "Default")
      (node (ref "C10") (pin "J2") (pinfunction "OUT_J2") (pintype "output"))
      (node (ref "C17") (pin "M2") (pinfunction "IN_M2") (pintype "input"))
    )
    (net (code "250") (name "Net-(C10E-OUT)") (class "Default")
      (node (ref "C10") (pin "L1") (pinfunction "OUT_L1") (pintype "output"))
      (node (ref "C14") (pin "E2") (pinfunction "D_E2") (pintype "input"))
    )
    (net (code "251") (name "Net-(C10G-OUT)") (class "Default")
      (node (ref "C10") (pin "S1") (pinfunction "OUT_S1") (pintype "output"))
      (node (ref "C14") (pin "J1") (pinfunction "D_J1") (pintype "input"))
    )
    (net (code "252") (name "Net-(C10J-OUT)") (class "Default")
      (node (ref "C10") (pin "V2") (pinfunction "OUT_V2") (pintype "output"))
      (node (ref "C17") (pin "V1") (pinfunction "IN_V1") (pintype "input"))
    )
    (net (code "253") (name "Net-(C11C-OUT)") (class "Default")
      (node (ref "C11") (pin "F2") (pinfunction "OUT_F2") (pintype "output"))
      (node (ref "C12") (pin "H1") (pinfunction "IN3_H1") (pintype "input"))
    )
    (net (code "254") (name "Net-(C11F-OUT)") (class "Default")
      (node (ref "C11") (pin "K1") (pinfunction "OUT_K1") (pintype "output"))
      (node (ref "C11") (pin "L1") (pinfunction "IN1_L1") (pintype "input"))
    )
    (net (code "255") (name "Net-(C11G-OUT)") (class "Default")
      (node (ref "C11") (pin "K2") (pinfunction "OUT_K2") (pintype "output"))
      (node (ref "D12") (pin "K2") (pinfunction "IN1_K2") (pintype "input"))
      (node (ref "D12") (pin "L2") (pinfunction "IN2_L2") (pintype "input"))
    )
    (net (code "256") (name "Net-(C11J-OUT)") (class "Default")
      (node (ref "C11") (pin "S1") (pinfunction "OUT_S1") (pintype "output"))
      (node (ref "C12") (pin "E1") (pinfunction "IN1_E1") (pintype "input"))
    )
    (net (code "257") (name "Net-(C11K-OUT)") (class "Default")
      (node (ref "C11") (pin "S2") (pinfunction "OUT_S2") (pintype "output"))
      (node (ref "C11") (pin "T2") (pinfunction "IN1_T2") (pintype "input"))
    )
    (net (code "258") (name "Net-(C11N-OUT)") (class "Default")
      (node (ref "C11") (pin "V2") (pinfunction "OUT_V2") (pintype "output"))
      (node (ref "C13") (pin "V1") (pinfunction "IN_V1") (pintype "input"))
    )
    (net (code "259") (name "Net-(C12A-OUT)") (class "Default")
      (node (ref "C12") (pin "D1") (pinfunction "OUT_D1") (pintype "output"))
      (node (ref "C13") (pin "M2") (pinfunction "IN_M2") (pintype "input"))
    )
    (net (code "260") (name "Net-(C12D-OUT)") (class "Default")
      (node (ref "C12") (pin "H2") (pinfunction "OUT_H2") (pintype "output"))
      (node (ref "D12") (pin "M2") (pinfunction "IN3_M2") (pintype "input"))
      (node (ref "D12") (pin "N2") (pinfunction "IN4_N2") (pintype "input"))
    )
    (net (code "261") (name "Net-(C12H-OUT)") (class "Default")
      (node (ref "C12") (pin "S2") (pinfunction "OUT_S2") (pintype "output"))
      (node (ref "C15") (pin "P1") (pinfunction "IN1_P1") (pintype "input"))
    )
    (net (code "262") (name "Net-(C13B-OUT)") (class "Default")
      (node (ref "C13") (pin "D2") (pinfunction "OUT_D2") (pintype "output"))
      (node (ref "C14") (pin "P1") (pinfunction "D_P1") (pintype "input"))
    )
    (net (code "263") (name "Net-(C13L-OUT)") (class "Default")
      (node (ref "C13") (pin "N2") (pinfunction "OUT_N2") (pintype "output"))
      (node (ref "C14") (pin "N2") (pinfunction "S_N2") (pintype "input"))
    )
    (net (code "264") (name "Net-(C13N-IN)") (class "Default")
      (node (ref "C13") (pin "P2") (pinfunction "IN_P2") (pintype "input"))
      (node (ref "C15") (pin "F2") (pinfunction "OUT_F2") (pintype "output"))
    )
    (net (code "265") (name "Net-(C13P-IN)") (class "Default")
      (node (ref "C13") (pin "S2") (pinfunction "IN_S2") (pintype "input"))
      (node (ref "C15") (pin "K2") (pinfunction "OUT_K2") (pintype "output"))
    )
    (net (code "266") (name "Net-(C14F-C)") (class "Default")
      (node (ref "C14") (pin "L2") (pinfunction "C_L2") (pintype "input"))
      (node (ref "C15") (pin "S2") (pinfunction "OUT_S2") (pintype "output"))
    )
    (net (code "267") (name "Net-(C15A-OUT)") (class "Default")
      (node (ref "C15") (pin "C1") (pinfunction "OUT_C1") (pintype "output"))
      (node (ref "C15") (pin "H1") (pinfunction "IN1_H1") (pintype "input"))
    )
    (net (code "268") (name "Net-(C15B-OUT)") (class "Default")
      (node (ref "C15") (pin "F1") (pinfunction "OUT_F1") (pintype "output"))
      (node (ref "C15") (pin "J1") (pinfunction "IN2_J1") (pintype "input"))
    )
    (net (code "269") (name "Net-(C15H-OUT)") (class "Default")
      (node (ref "C15") (pin "N1") (pinfunction "OUT_N1") (pintype "output"))
      (node (ref "C15") (pin "R1") (pinfunction "IN2_R1") (pintype "input"))
    )
    (net (code "270") (name "Net-(C15I-OUT)") (class "Default")
      (node (ref "C15") (pin "N2") (pinfunction "OUT_N2") (pintype "output"))
      (node (ref "C17") (pin "P2") (pinfunction "IN_P2") (pintype "input"))
    )
    (net (code "271") (name "Net-(C16F-IN1)") (class "Default")
      (node (ref "C16") (pin "K2") (pinfunction "IN1_K2") (pintype "input"))
      (node (ref "C16") (pin "L2") (pinfunction "IN2_L2") (pintype "input"))
      (node (ref "C16") (pin "M2") (pinfunction "IN3_M2") (pintype "input"))
      (node (ref "C16") (pin "N2") (pinfunction "IN4_N2") (pintype "input"))
      (node (ref "C17") (pin "B1") (pinfunction "OUT_B1") (pintype "output"))
    )
    (net (code "272") (name "Net-(C16G-OUT)") (class "Default")
      (node (ref "B16") (pin "K2") (pinfunction "K2_K2") (pintype "input"))
      (node (ref "C16") (pin "S1") (pinfunction "OUT_S1") (pintype "output"))
    )
    (net (code "273") (name "Net-(C16J-OUT)") (class "Default")
      (node (ref "A16") (pin "H2") (pinfunction "H2_H2") (pintype "input"))
      (node (ref "C16") (pin "V2") (pinfunction "OUT_V2") (pintype "output"))
    )
    (net (code "274") (name "Net-(C17B-IN)") (class "Default")
      (node (ref "A16") (pin "F2") (pinfunction "F2_F2") (pintype "output"))
      (node (ref "C17") (pin "C1") (pinfunction "IN_C1") (pintype "input"))
    )
    (net (code "275") (name "Net-(C17D-IN)") (class "Default")
      (node (ref "B16") (pin "F2") (pinfunction "F2_F2") (pintype "output"))
      (node (ref "C17") (pin "E2") (pinfunction "IN_E2") (pintype "input"))
    )
    (net (code "276") (name "Net-(C17L-OUT)") (class "Default")
      (node (ref "C17") (pin "N2") (pinfunction "OUT_N2") (pintype "output"))
      (node (ref "D08") (pin "B1") (pinfunction "B1_B1") (pintype "input"))
      (node (ref "D08") (pin "H1") (pinfunction "H1_H1") (pintype "input"))
      (node (ref "D08") (pin "N1") (pinfunction "N1_N1") (pintype "input"))
    )
    (net (code "277") (name "Net-(C17O-IN)") (class "Default")
      (node (ref "C17") (pin "R1") (pinfunction "IN_R1") (pintype "input"))
      (node (ref "D17") (pin "F2") (pinfunction "F2_F2") (pintype "output"))
    )
    (net (code "278") (name "Net-(C17P-IN)") (class "Default")
      (node (ref "C17") (pin "S2") (pinfunction "IN_S2") (pintype "input"))
      (node (ref "D16") (pin "T2") (pinfunction "F2_T2") (pintype "output"))
    )
    (net (code "279") (name "Net-(C17Q-OUT)") (class "Default")
      (node (ref "C17") (pin "U1") (pinfunction "OUT_U1") (pintype "output"))
      (node (ref "D08") (pin "D2") (pinfunction "D2_D2") (pintype "input"))
      (node (ref "D08") (pin "L2") (pinfunction "L2_L2") (pintype "input"))
      (node (ref "D08") (pin "S2") (pinfunction "S2_S2") (pintype "input"))
    )
    (net (code "280") (name "Net-(D09A-OUT)") (class "Default")
      (node (ref "D08") (pin "C1") (pinfunction "C1_C1") (pintype "input"))
      (node (ref "D08") (pin "D1") (pinfunction "D1_D1") (pintype "input"))
      (node (ref "D09") (pin "E1") (pinfunction "OUT_E1") (pintype "output"))
    )
    (net (code "281") (name "Net-(D09D-OUT)") (class "Default")
      (node (ref "D08") (pin "E2") (pinfunction "E2_E2") (pintype "input"))
      (node (ref "D08") (pin "F2") (pinfunction "F2_F2") (pintype "input"))
      (node (ref "D09") (pin "J2") (pinfunction "OUT_J2") (pintype "output"))
    )
    (net (code "282") (name "Net-(D09E-OUT)") (class "Default")
      (node (ref "D08") (pin "J1") (pinfunction "J1_J1") (pintype "input"))
      (node (ref "D08") (pin "K1") (pinfunction "K1_K1") (pintype "input"))
      (node (ref "D09") (pin "L1") (pinfunction "OUT_L1") (pintype "output"))
    )
    (net (code "283") (name "Net-(D09F-OUT)") (class "Default")
      (node (ref "D08") (pin "M2") (pinfunction "M2_M2") (pintype "input"))
      (node (ref "D08") (pin "N2") (pinfunction "N2_N2") (pintype "input"))
      (node (ref "D09") (pin "P2") (pinfunction "OUT_P2") (pintype "output"))
    )
    (net (code "284") (name "Net-(D09G-OUT)") (class "Default")
      (node (ref "D08") (pin "P1") (pinfunction "P1_P1") (pintype "input"))
      (node (ref "D08") (pin "R1") (pinfunction "R1_R1") (pintype "input"))
      (node (ref "D09") (pin "S1") (pinfunction "OUT_S1") (pintype "output"))
    )
    (net (code "285") (name "Net-(D09J-OUT)") (class "Default")
      (node (ref "D08") (pin "T2") (pinfunction "T2_T2") (pintype "input"))
      (node (ref "D08") (pin "U2") (pinfunction "U2_U2") (pintype "input"))
      (node (ref "D09") (pin "V2") (pinfunction "OUT_V2") (pintype "output"))
    )
    (net (code "286") (name "Net-(D10D-OUT)") (class "Default")
      (node (ref "D10") (pin "P2") (pinfunction "OUT_P2") (pintype "output"))
      (node (ref "D14") (pin "J2") (pinfunction "N1_J2") (pintype "input"))
    )
    (net (code "287") (name "Net-(D12A-IN1)") (class "Default")
      (node (ref "D12") (pin "A1") (pinfunction "IN1_A1") (pintype "input"))
      (node (ref "D12") (pin "B1") (pinfunction "IN2_B1") (pintype "input"))
      (node (ref "D12") (pin "C1") (pinfunction "IN3_C1") (pintype "input"))
      (node (ref "D12") (pin "D1") (pinfunction "IN4_D1") (pintype "input"))
      (node (ref "D13") (pin "F2") (pinfunction "F2_F2") (pintype "output"))
    )
    (net (code "288") (name "Net-(D13C-D2)") (class "Default")
      (node (ref "D13") (pin "R2") (pinfunction "E2_R2") (pintype "passive"))
      (node (ref "D13") (pin "S2") (pinfunction "D2_S2") (pintype "passive"))
    )
    (net (code "289") (name "Net-(D14-PadM2)") (class "Default")
      (node (ref "D14") (pin "M2") (pinfunction "M2_M2") (pintype "passive"))
      (node (ref "D14") (pin "V2") (pinfunction "V2_V2") (pintype "passive"))
    )
    (net (code "290") (name "Net-(D14-PadP1)") (class "Default")
      (node (ref "D14") (pin "P1") (pinfunction "P1_P1") (pintype "passive"))
      (node (ref "D14") (pin "V1") (pinfunction "V1_V1") (pintype "passive"))
    )
    (net (code "291") (name "Net-(D14E-M2)") (class "Default")
      (node (ref "D14") (pin "D2") (pinfunction "M2_D2") (pintype "passive"))
      (node (ref "D14") (pin "H1") (pinfunction "P2_H1") (pintype "passive"))
    )
    (net (code "292") (name "Net-(D14E-P1)") (class "Default")
      (node (ref "D14") (pin "A1") (pinfunction "V1_A1") (pintype "passive"))
      (node (ref "D14") (pin "C1") (pinfunction "P1_C1") (pintype "passive"))
    )
    (net (code "293") (name "Net-(D15-PadN2)") (class "Default")
      (node (ref "D15") (pin "N2") (pinfunction "N2_N2") (pintype "passive"))
      (node (ref "D15") (pin "S2") (pinfunction "S2_S2") (pintype "passive"))
    )
    (net (code "294") (name "Net-(D16D-D2)") (class "Default")
      (node (ref "D16") (pin "R2") (pinfunction "E2_R2") (pintype "passive"))
      (node (ref "D16") (pin "V2") (pinfunction "D2_V2") (pintype "passive"))
    )
    (net (code "295") (name "Net-(D16D-H1)") (class "Default")
      (node (ref "D16") (pin "S1") (pinfunction "H1_S1") (pintype "passive"))
      (node (ref "D16") (pin "S2") (pinfunction "L2_S2") (pintype "passive"))
    )
    (net (code "296") (name "Net-(D17-PadD2)") (class "Default")
      (node (ref "D17") (pin "D2") (pinfunction "D2_D2") (pintype "passive"))
      (node (ref "D17") (pin "E2") (pinfunction "E2_E2") (pintype "passive"))
    )
    (net (code "297") (name "Net-(D17C-D2)") (class "Default")
      (node (ref "D17") (pin "R2") (pinfunction "E2_R2") (pintype "passive"))
      (node (ref "D17") (pin "S2") (pinfunction "D2_S2") (pintype "passive"))
    )
    (net (code "298") (name "PAR") (class "Default")
      (node (ref "A08") (pin "U1") (pinfunction "0_U1") (pintype "output"))
      (node (ref "A25") (pin "T1") (pinfunction "P$2_T1") (pintype "bidirectional"))
    )
    (net (code "299") (name "PC+ES") (class "Default")
      (node (ref "A11") (pin "H2") (pinfunction "IN_H2") (pintype "input"))
      (node (ref "A12") (pin "C1") (pinfunction "OUT_C1") (pintype "output"))
    )
    (net (code "300") (name "PWR_CLR") (class "Default")
      (node (ref "C06") (pin "R2") (pinfunction "OUT_R2") (pintype "output"))
    )
    (net (code "301") (name "RD+WD") (class "Default")
      (node (ref "A09") (pin "P1") (pinfunction "IN3_P1") (pintype "input"))
      (node (ref "B08") (pin "N2") (pinfunction "OUT_N2") (pintype "output"))
      (node (ref "B12") (pin "D2") (pinfunction "IN1_D2") (pintype "input"))
      (node (ref "C12") (pin "R1") (pinfunction "IN2_R1") (pintype "input"))
    )
    (net (code "302") (name "RDD_00") (class "Default")
      (node (ref "A21") (pin "U2") (pinfunction "U2_U2") (pintype "output"))
      (node (ref "B09") (pin "M2") (pinfunction "D_M2") (pintype "input"))
      (node (ref "D09") (pin "C1") (pinfunction "IN2A_C1") (pintype "input"))
      (node (ref "D09") (pin "F2") (pinfunction "IN2A_F2") (pintype "input"))
    )
    (net (code "303") (name "RDD_01") (class "Default")
      (node (ref "B09") (pin "P1") (pinfunction "D_P1") (pintype "input"))
      (node (ref "B20") (pin "U2") (pinfunction "U2_U2") (pintype "output"))
      (node (ref "D09") (pin "J1") (pinfunction "IN2A_J1") (pintype "input"))
      (node (ref "D09") (pin "M2") (pinfunction "IN2A_M2") (pintype "input"))
    )
    (net (code "304") (name "RDD_02") (class "Default")
      (node (ref "A20") (pin "U2") (pinfunction "U2_U2") (pintype "output"))
      (node (ref "B09") (pin "E2") (pinfunction "D_E2") (pintype "input"))
      (node (ref "D09") (pin "P1") (pinfunction "IN2A_P1") (pintype "input"))
      (node (ref "D09") (pin "T2") (pinfunction "IN2A_T2") (pintype "input"))
    )
    (net (code "305") (name "RDMK") (class "Default")
      (node (ref "B18") (pin "U2") (pinfunction "U2_U2") (pintype "output"))
      (node (ref "CD18") (pin "AS2") (pinfunction "AS2_AS2") (pintype "input"))
    )
    (net (code "306") (name "RD_EN") (class "Default")
      (node (ref "C11") (pin "J1") (pinfunction "IN2_J1") (pintype "input"))
      (node (ref "C11") (pin "N2") (pinfunction "OUT_N2") (pintype "output"))
    )
    (net (code "307") (name "RD_EN_LPB_00-02") (class "Default")
      (node (ref "C10") (pin "D2") (pinfunction "IN1A_D2") (pintype "input"))
      (node (ref "C13") (pin "T2") (pinfunction "OUT_T2") (pintype "output"))
      (node (ref "D09") (pin "D1") (pinfunction "IN2B_D1") (pintype "input"))
      (node (ref "D09") (pin "K1") (pinfunction "IN2B_K1") (pintype "input"))
      (node (ref "D09") (pin "R1") (pinfunction "IN2B_R1") (pintype "input"))
    )
    (net (code "308") (name "RD_EN_LPB_03-05") (class "Default")
      (node (ref "C10") (pin "R2") (pinfunction "IN1A_R2") (pintype "input"))
      (node (ref "C13") (pin "R2") (pinfunction "OUT_R2") (pintype "output"))
      (node (ref "D09") (pin "H2") (pinfunction "IN2B_H2") (pintype "input"))
      (node (ref "D09") (pin "N2") (pinfunction "IN2B_N2") (pintype "input"))
      (node (ref "D09") (pin "U2") (pinfunction "IN2B_U2") (pintype "input"))
    )
    (net (code "309") (name "READ_ALL") (class "Default")
      (node (ref "D07") (pin "N2") (pinfunction "O3_N2") (pintype "output"))
    )
    (net (code "310") (name "READ_DATA") (class "Default")
      (node (ref "A10") (pin "L1") (pinfunction "IN1_L1") (pintype "input"))
      (node (ref "C11") (pin "H1") (pinfunction "IN1_H1") (pintype "input"))
      (node (ref "D07") (pin "J2") (pinfunction "O2_J2") (pintype "output"))
    )
    (net (code "311") (name "RSTA") (class "Default")
      (node (ref "C04") (pin "A1") (pinfunction "A1_A1") (pintype "output"))
    )
    (net (code "312") (name "RSTB") (class "Default")
      (node (ref "C05") (pin "C1") (pinfunction "C1_C1") (pintype "output"))
    )
    (net (code "313") (name "SE") (class "Default")
      (node (ref "D07") (pin "L2") (pinfunction "O7_L2") (pintype "output"))
    )
    (net (code "314") (name "SEARCH") (class "Default")
      (node (ref "C11") (pin "D2") (pinfunction "IN1_D2") (pintype "input"))
      (node (ref "D07") (pin "E2") (pinfunction "O1_E2") (pintype "output"))
    )
    (net (code "315") (name "SEL") (class "Default")
      (node (ref "A08") (pin "H2") (pinfunction "1_H2") (pintype "output"))
      (node (ref "A25") (pin "S1") (pinfunction "P$2_S1") (pintype "bidirectional"))
    )
    (net (code "316") (name "SHIFT_CK") (class "Default")
      (node (ref "C17") (pin "K1") (pinfunction "OUT_K1") (pintype "output"))
      (node (ref "CD18") (pin "BR2") (pinfunction "BR2_BR2") (pintype "input"))
    )
    (net (code "317") (name "SH_DTB") (class "Default")
      (node (ref "A10") (pin "R2") (pinfunction "IN2_R2") (pintype "input"))
      (node (ref "B09") (pin "B1") (pinfunction "C_B1") (pintype "input"))
      (node (ref "B09") (pin "D2") (pinfunction "C_D2") (pintype "input"))
      (node (ref "B09") (pin "H1") (pinfunction "C_H1") (pintype "input"))
      (node (ref "B09") (pin "L2") (pinfunction "C_L2") (pintype "input"))
      (node (ref "B09") (pin "N1") (pinfunction "C_N1") (pintype "input"))
      (node (ref "B09") (pin "S2") (pinfunction "C_S2") (pintype "input"))
      (node (ref "B10") (pin "E1") (pinfunction "OUT_E1") (pintype "output"))
      (node (ref "C09") (pin "B1") (pinfunction "C_B1") (pintype "input"))
      (node (ref "C09") (pin "D2") (pinfunction "C_D2") (pintype "input"))
      (node (ref "C09") (pin "H1") (pinfunction "C_H1") (pintype "input"))
      (node (ref "C09") (pin "L2") (pinfunction "C_L2") (pintype "input"))
      (node (ref "C09") (pin "N1") (pinfunction "C_N1") (pintype "input"))
      (node (ref "C09") (pin "S2") (pinfunction "C_S2") (pintype "input"))
    )
    (net (code "318") (name "SH_EN") (class "Default")
      (node (ref "A11") (pin "N2") (pinfunction "OUT_N2") (pintype "output"))
      (node (ref "A12") (pin "E2") (pinfunction "IN2_E2") (pintype "input"))
      (node (ref "C10") (pin "A1") (pinfunction "IN1A_A1") (pintype "input"))
      (node (ref "C10") (pin "F1") (pinfunction "IN1A_F1") (pintype "input"))
      (node (ref "C10") (pin "M1") (pinfunction "IN1A_M1") (pintype "input"))
    )
    (net (code "319") (name "SH_ST") (class "Default")
      (node (ref "C17") (pin "A1") (pinfunction "IN_A1") (pintype "input"))
      (node (ref "CD18") (pin "AM1") (pinfunction "AM1_AM1") (pintype "output"))
    )
    (net (code "320") (name "SH_ST-B") (class "Default")
      (node (ref "C16") (pin "P2") (pinfunction "OUT_P2") (pintype "output"))
      (node (ref "CD18") (pin "BC1") (pinfunction "BC1_BC1") (pintype "input"))
    )
    (net (code "321") (name "SINGLE_UNIT") (class "Default")
      (node (ref "A09") (pin "K1") (pinfunction "IN4_K1") (pintype "input"))
      (node (ref "B21") (pin "U2") (pinfunction "OUT_U2") (pintype "output"))
    )
    (net (code "322") (name "SP_DY") (class "Default")
      (node (ref "D14") (pin "H2") (pinfunction "H2_H2") (pintype "output"))
    )
    (net (code "323") (name "ST_BLK_MK") (class "Default")
      (node (ref "A26") (pin "K1") (pinfunction "P$2_K1") (pintype "bidirectional"))
      (node (ref "C13") (pin "E2") (pinfunction "IN_E2") (pintype "input"))
      (node (ref "CD18") (pin "AR2") (pinfunction "AR2_AR2") (pintype "output"))
    )
    (net (code "324") (name "ST_CK") (class "Default")
      (node (ref "A10") (pin "P1") (pinfunction "IN1_P1") (pintype "input"))
      (node (ref "A26") (pin "P1") (pinfunction "P$2_P1") (pintype "bidirectional"))
      (node (ref "C13") (pin "J1") (pinfunction "IN_J1") (pintype "input"))
      (node (ref "CD18") (pin "BR1") (pinfunction "BR1_BR1") (pintype "output"))
      (node (ref "D17") (pin "M2") (pinfunction "K2_M2") (pintype "input"))
      (node (ref "D17") (pin "N2") (pinfunction "J2_N2") (pintype "input"))
      (node (ref "D17") (pin "P2") (pinfunction "H2_P2") (pintype "input"))
    )
    (net (code "325") (name "ST_CK_0P") (class "Default")
      (node (ref "B12") (pin "H2") (pinfunction "IN4_H2") (pintype "input"))
      (node (ref "C12") (pin "S1") (pinfunction "IN3_S1") (pintype "input"))
      (node (ref "C13") (pin "B1") (pinfunction "OUT_B1") (pintype "output"))
    )
    (net (code "326") (name "ST_DATA") (class "Default")
      (node (ref "B12") (pin "A1") (pinfunction "IN1_A1") (pintype "input"))
      (node (ref "C13") (pin "H2") (pinfunction "IN_H2") (pintype "input"))
      (node (ref "C16") (pin "J2") (pinfunction "OUT_J2") (pintype "output"))
    )
    (net (code "327") (name "ST_FINAL") (class "Default")
      (node (ref "A09") (pin "S2") (pinfunction "IN2_S2") (pintype "input"))
      (node (ref "A26") (pin "N1") (pinfunction "P$2_N1") (pintype "bidirectional"))
      (node (ref "C11") (pin "D1") (pinfunction "IN1_D1") (pintype "input"))
      (node (ref "C13") (pin "L1") (pinfunction "IN_L1") (pintype "input"))
      (node (ref "CD18") (pin "BL2") (pinfunction "BL2_BL2") (pintype "output"))
    )
    (net (code "328") (name "ST_IDLE") (class "Default")
      (node (ref "A26") (pin "R1") (pinfunction "P$2_R1") (pintype "bidirectional"))
      (node (ref "C13") (pin "K2") (pinfunction "IN_K2") (pintype "input"))
      (node (ref "CD18") (pin "BD2") (pinfunction "BD2_BD2") (pintype "input"))
    )
    (net (code "329") (name "ST_REV_CK") (class "Default")
      (node (ref "A26") (pin "L1") (pinfunction "P$2_L1") (pintype "bidirectional"))
      (node (ref "B11") (pin "S1") (pinfunction "IN3_S1") (pintype "input"))
      (node (ref "C11") (pin "A1") (pinfunction "IN1_A1") (pintype "input"))
      (node (ref "C13") (pin "D1") (pinfunction "IN_D1") (pintype "input"))
      (node (ref "CD18") (pin "BS1") (pinfunction "BS1_BS1") (pintype "output"))
      (node (ref "D12") (pin "F2") (pinfunction "IN3_F2") (pintype "input"))
      (node (ref "D12") (pin "H2") (pinfunction "IN4_H2") (pintype "input"))
    )
    (net (code "330") (name "SWTM") (class "Default")
      (node (ref "A26") (pin "V2") (pinfunction "P$2_V2") (pintype "bidirectional"))
      (node (ref "B06") (pin "P2") (pinfunction "IN_P2") (pintype "input"))
      (node (ref "B08") (pin "V1") (pinfunction "P$1_V1") (pintype "passive"))
      (node (ref "B11") (pin "B1") (pinfunction "IN2_B1") (pintype "input"))
      (node (ref "C10") (pin "N2") (pinfunction "IN2B_N2") (pintype "input"))
      (node (ref "C12") (pin "P2") (pinfunction "IN2_P2") (pintype "input"))
      (node (ref "C15") (pin "L1") (pinfunction "IN1_L1") (pintype "input"))
    )
    (net (code "331") (name "SYNC") (class "Default")
      (node (ref "B10") (pin "D2") (pinfunction "IN1_D2") (pintype "input"))
      (node (ref "B10") (pin "E2") (pinfunction "IN2_E2") (pintype "input"))
      (node (ref "CD18") (pin "BN2") (pinfunction "BN2_BN2") (pintype "output"))
    )
    (net (code "332") (name "SYNC_EN") (class "Default")
      (node (ref "B11") (pin "M2") (pinfunction "OUT_M2") (pintype "output"))
      (node (ref "CD18") (pin "BH1") (pinfunction "BH1_BH1") (pintype "input"))
    )
    (net (code "333") (name "T3") (class "Default")
      (node (ref "C17") (pin "S1") (pinfunction "OUT_S1") (pintype "output"))
      (node (ref "D12") (pin "N1") (pinfunction "IN2_N1") (pintype "input"))
      (node (ref "D12") (pin "P1") (pinfunction "IN3_P1") (pintype "input"))
    )
    (net (code "334") (name "TIM") (class "Default")
      (node (ref "A08") (pin "L1") (pinfunction "1_L1") (pintype "output"))
      (node (ref "A25") (pin "U1") (pinfunction "P$2_U1") (pintype "bidirectional"))
    )
    (net (code "335") (name "TM_EN") (class "Default")
      (node (ref "A18") (pin "R2") (pinfunction "R2_R2") (pintype "input"))
      (node (ref "B18") (pin "R2") (pinfunction "R2_R2") (pintype "input"))
      (node (ref "C13") (pin "N1") (pinfunction "IN_N1") (pintype "input"))
      (node (ref "C15") (pin "S1") (pinfunction "OUT_S1") (pintype "output"))
      (node (ref "C16") (pin "M1") (pinfunction "IN1_M1") (pintype "input"))
      (node (ref "C16") (pin "R2") (pinfunction "IN1_R2") (pintype "input"))
    )
    (net (code "336") (name "TP00") (class "Default")
      (node (ref "A08") (pin "B1") (pinfunction "C_B1") (pintype "input"))
      (node (ref "A15") (pin "L1") (pinfunction "OUT_L1") (pintype "output"))
      (node (ref "A16") (pin "M2") (pinfunction "K2_M2") (pintype "input"))
      (node (ref "A16") (pin "N2") (pinfunction "J2_N2") (pintype "input"))
      (node (ref "A16") (pin "P2") (pinfunction "H2_P2") (pintype "input"))
      (node (ref "B10") (pin "F2") (pinfunction "IN3_F2") (pintype "input"))
      (node (ref "B10") (pin "H2") (pinfunction "IN4_H2") (pintype "input"))
      (node (ref "B10") (pin "N1") (pinfunction "IN2_N1") (pintype "input"))
      (node (ref "B13") (pin "B1") (pinfunction "C_B1") (pintype "input"))
      (node (ref "B13") (pin "D2") (pinfunction "C_D2") (pintype "input"))
      (node (ref "B13") (pin "H1") (pinfunction "C_H1") (pintype "input"))
      (node (ref "B15") (pin "J1") (pinfunction "IN2_J1") (pintype "input"))
      (node (ref "C15") (pin "E1") (pinfunction "IN2_E1") (pintype "input"))
    )
    (net (code "337") (name "TP00_A") (class "Default")
      (node (ref "A15") (pin "S1") (pinfunction "OUT_S1") (pintype "output"))
      (node (ref "B10") (pin "H1") (pinfunction "IN2_H1") (pintype "input"))
      (node (ref "C12") (pin "E2") (pinfunction "IN2_E2") (pintype "input"))
    )
    (net (code "338") (name "TP01") (class "Default")
      (node (ref "A12") (pin "J2") (pinfunction "IN2_J2") (pintype "input"))
      (node (ref "A15") (pin "P2") (pinfunction "OUT_P2") (pintype "output"))
      (node (ref "B16") (pin "M2") (pinfunction "K2_M2") (pintype "input"))
      (node (ref "B16") (pin "N2") (pinfunction "J2_N2") (pintype "input"))
      (node (ref "B16") (pin "P2") (pinfunction "H2_P2") (pintype "input"))
      (node (ref "C11") (pin "J2") (pinfunction "IN2_J2") (pintype "input"))
      (node (ref "C15") (pin "B1") (pinfunction "IN2_B1") (pintype "input"))
      (node (ref "CD18") (pin "BF1") (pinfunction "BF1_BF1") (pintype "input"))
    )
    (net (code "339") (name "TP01_A") (class "Default")
      (node (ref "A15") (pin "V2") (pinfunction "OUT_V2") (pintype "output"))
      (node (ref "B12") (pin "T2") (pinfunction "IN3_T2") (pintype "input"))
      (node (ref "C15") (pin "M2") (pinfunction "IN2_M2") (pintype "input"))
    )
    (net (code "340") (name "T_TRK") (class "Default")
      (node (ref "A18") (pin "U2") (pinfunction "U2_U2") (pintype "output"))
      (node (ref "B15") (pin "E2") (pinfunction "IN2_E2") (pintype "input"))
      (node (ref "C15") (pin "R2") (pinfunction "IN2_R2") (pintype "input"))
      (node (ref "D14") (pin "S1") (pinfunction "S1_S1") (pintype "input"))
      (node (ref "D14") (pin "U1") (pinfunction "U1_U1") (pintype "input"))
    )
    (net (code "341") (name "U+M_DY") (class "Default")
      (node (ref "D14") (pin "K1") (pinfunction "H2_K1") (pintype "output"))
    )
    (net (code "342") (name "USR_00") (class "Default")
      (node (ref "A07") (pin "V2") (pinfunction "IN2_V2") (pintype "input"))
      (node (ref "A25") (pin "A1") (pinfunction "P$2_A1") (pintype "bidirectional"))
      (node (ref "B07") (pin "E1") (pinfunction "E1_E1") (pintype "output"))
    )
    (net (code "343") (name "USR_01") (class "Default")
      (node (ref "A07") (pin "U2") (pinfunction "IN1_U2") (pintype "input"))
      (node (ref "A25") (pin "B1") (pinfunction "P$2_B1") (pintype "bidirectional"))
      (node (ref "B07") (pin "H2") (pinfunction "H2_H2") (pintype "output"))
    )
    (net (code "344") (name "USR_02") (class "Default")
      (node (ref "A07") (pin "V1") (pinfunction "IN0_V1") (pintype "input"))
      (node (ref "A25") (pin "C1") (pinfunction "P$2_C1") (pintype "bidirectional"))
      (node (ref "B07") (pin "L1") (pinfunction "L1_L1") (pintype "output"))
    )
    (net (code "345") (name "UTS") (class "Default")
      (node (ref "A10") (pin "E1") (pinfunction "IN2_E1") (pintype "input"))
      (node (ref "A26") (pin "J1") (pinfunction "P$2_J1") (pintype "bidirectional"))
      (node (ref "B15") (pin "P1") (pinfunction "IN1_P1") (pintype "input"))
      (node (ref "C14") (pin "R2") (pinfunction "0_R2") (pintype "output"))
    )
    (net (code "346") (name "VCC") (class "Default")
      (node (ref "AB01") (pin "AA2") (pinfunction "VCC_AA2") (pintype "power_in"))
      (node (ref "AB01") (pin "AB1") (pinfunction "VCC_AB1") (pintype "power_in"))
      (node (ref "AB01") (pin "AC1") (pinfunction "VCC_AC1") (pintype "power_in"))
      (node (ref "AB01") (pin "AD1") (pinfunction "VCC_AD1") (pintype "power_in"))
      (node (ref "AB01") (pin "AE1") (pinfunction "VCC_AE1") (pintype "power_in"))
      (node (ref "AB01") (pin "AF1") (pinfunction "VCC_AF1") (pintype "power_in"))
      (node (ref "AB01") (pin "AH1") (pinfunction "VCC_AH1") (pintype "power_in"))
      (node (ref "AB01") (pin "AJ1") (pinfunction "VCC_AJ1") (pintype "power_in"))
      (node (ref "AB01") (pin "AK1") (pinfunction "VCC_AK1") (pintype "power_in"))
      (node (ref "AB01") (pin "AL1") (pinfunction "VCC_AL1") (pintype "power_in"))
      (node (ref "AB01") (pin "BA2") (pinfunction "VCC_BA2") (pintype "power_in"))
      (node (ref "AB01") (pin "BB1") (pinfunction "VCC_BB1") (pintype "power_in"))
      (node (ref "AB01") (pin "BC1") (pinfunction "VCC_BC1") (pintype "power_in"))
      (node (ref "AB01") (pin "BD1") (pinfunction "VCC_BD1") (pintype "power_in"))
      (node (ref "AB01") (pin "BE1") (pinfunction "VCC_BE1") (pintype "power_in"))
    )
    (net (code "347") (name "W+UTS") (class "Default")
      (node (ref "A15") (pin "A1") (pinfunction "IN1_A1") (pintype "input"))
      (node (ref "A15") (pin "H2") (pinfunction "IN4_H2") (pintype "input"))
      (node (ref "C12") (pin "M2") (pinfunction "OUT_M2") (pintype "output"))
    )
    (net (code "348") (name "W-INH") (class "Default")
      (node (ref "A08") (pin "V1") (pinfunction "0_V1") (pintype "output"))
    )
    (net (code "349") (name "W01") (class "Default")
      (node (ref "A26") (pin "J2") (pinfunction "P$2_J2") (pintype "bidirectional"))
      (node (ref "CD18") (pin "BJ2") (pinfunction "BJ2_BJ2") (pintype "output"))
    )
    (net (code "350") (name "W01-W05") (class "Default")
      (node (ref "CD18") (pin "AK1") (pinfunction "AK1_AK1") (pintype "output"))
    )
    (net (code "351") (name "W02") (class "Default")
      (node (ref "A26") (pin "K2") (pinfunction "P$2_K2") (pintype "bidirectional"))
      (node (ref "CD18") (pin "BV2") (pinfunction "BV2_BV2") (pintype "output"))
    )
    (net (code "352") (name "W03") (class "Default")
      (node (ref "A26") (pin "L2") (pinfunction "P$2_L2") (pintype "bidirectional"))
      (node (ref "CD18") (pin "BE2") (pinfunction "BE2_BE2") (pintype "output"))
    )
    (net (code "353") (name "W04") (class "Default")
      (node (ref "A26") (pin "M2") (pinfunction "P$2_M2") (pintype "bidirectional"))
      (node (ref "CD18") (pin "AT2") (pinfunction "AT2_AT2") (pintype "output"))
    )
    (net (code "354") (name "W05") (class "Default")
      (node (ref "A26") (pin "N2") (pinfunction "P$2_N2") (pintype "bidirectional"))
      (node (ref "CD18") (pin "BU2") (pinfunction "BU2_BU2") (pintype "output"))
    )
    (net (code "355") (name "W06") (class "Default")
      (node (ref "A26") (pin "P2") (pinfunction "P$2_P2") (pintype "bidirectional"))
      (node (ref "CD18") (pin "AM2") (pinfunction "AM2_AM2") (pintype "output"))
    )
    (net (code "356") (name "W07") (class "Default")
      (node (ref "A26") (pin "R2") (pinfunction "P$2_R2") (pintype "bidirectional"))
      (node (ref "CD18") (pin "AK2") (pinfunction "AK2_AK2") (pintype "output"))
    )
    (net (code "357") (name "W08") (class "Default")
      (node (ref "A26") (pin "S2") (pinfunction "P$2_S2") (pintype "bidirectional"))
      (node (ref "CD18") (pin "AL1") (pinfunction "AL1_AL1") (pintype "output"))
    )
    (net (code "358") (name "W09") (class "Default")
      (node (ref "A26") (pin "T2") (pinfunction "P$2_T2") (pintype "bidirectional"))
      (node (ref "CD18") (pin "BF2") (pinfunction "BF2_BF2") (pintype "output"))
    )
    (net (code "359") (name "WB00") (class "Default")
      (node (ref "A21") (pin "N2") (pinfunction "N2_N2") (pintype "input"))
      (node (ref "A25") (pin "P2") (pinfunction "P$2_P2") (pintype "bidirectional"))
      (node (ref "B18") (pin "N2") (pinfunction "N2_N2") (pintype "input"))
      (node (ref "C14") (pin "F1") (pinfunction "0_F1") (pintype "output"))
      (node (ref "D09") (pin "A1") (pinfunction "IN1A_A1") (pintype "input"))
    )
    (net (code "360") (name "WB01") (class "Default")
      (node (ref "A25") (pin "R2") (pinfunction "P$2_R2") (pintype "bidirectional"))
      (node (ref "B20") (pin "N2") (pinfunction "N2_N2") (pintype "input"))
      (node (ref "C14") (pin "J2") (pinfunction "0_J2") (pintype "output"))
      (node (ref "D09") (pin "F1") (pinfunction "IN1A_F1") (pintype "input"))
    )
    (net (code "361") (name "WB02") (class "Default")
      (node (ref "A20") (pin "N2") (pinfunction "N2_N2") (pintype "input"))
      (node (ref "A25") (pin "S2") (pinfunction "P$2_S2") (pintype "bidirectional"))
      (node (ref "C14") (pin "M1") (pinfunction "0_M1") (pintype "output"))
      (node (ref "D09") (pin "M1") (pinfunction "IN1A_M1") (pintype "input"))
    )
    (net (code "362") (name "WC") (class "Default")
      (node (ref "A26") (pin "H1") (pinfunction "P$2_H1") (pintype "bidirectional"))
      (node (ref "B10") (pin "M1") (pinfunction "IN1_M1") (pintype "input"))
      (node (ref "B11") (pin "K1") (pinfunction "IN1_K1") (pintype "input"))
      (node (ref "D11") (pin "S1") (pinfunction "1_S1") (pintype "output"))
    )
    (net (code "363") (name "WC0") (class "Default")
      (node (ref "C01") (pin "H1") (pinfunction "OUT_H1") (pintype "output"))
      (node (ref "C06") (pin "M2") (pinfunction "IN_M2") (pintype "input"))
    )
    (net (code "364") (name "WRITE_ALL") (class "Default")
      (node (ref "A08") (pin "S2") (pinfunction "C_S2") (pintype "input"))
      (node (ref "B11") (pin "M1") (pinfunction "IN3_M1") (pintype "input"))
      (node (ref "B12") (pin "F1") (pinfunction "IN1_F1") (pintype "input"))
      (node (ref "D07") (pin "M2") (pinfunction "O5_M2") (pintype "output"))
    )
    (net (code "365") (name "WRITE_DATA") (class "Default")
      (node (ref "A09") (pin "R2") (pinfunction "IN1_R2") (pintype "input"))
      (node (ref "B11") (pin "R1") (pinfunction "IN2_R1") (pintype "input"))
      (node (ref "B12") (pin "B1") (pinfunction "IN2_B1") (pintype "input"))
      (node (ref "B12") (pin "P1") (pinfunction "IN3_P1") (pintype "input"))
      (node (ref "D07") (pin "F2") (pinfunction "O4_F2") (pintype "output"))
    )
    (net (code "366") (name "WRITE_OK") (class "Default")
      (node (ref "A22") (pin "D2") (pinfunction "D2_D2") (pintype "output"))
      (node (ref "B11") (pin "C1") (pinfunction "IN3_C1") (pintype "input"))
      (node (ref "B15") (pin "R1") (pinfunction "IN2_R1") (pintype "input"))
      (node (ref "C17") (pin "H2") (pinfunction "IN_H2") (pintype "input"))
    )
    (net (code "367") (name "WRITE_OK+UTS") (class "Default")
      (node (ref "B12") (pin "D1") (pinfunction "IN4_D1") (pintype "input"))
      (node (ref "B12") (pin "K1") (pinfunction "IN4_K1") (pintype "input"))
      (node (ref "C17") (pin "M1") (pinfunction "OUT_M1") (pintype "output"))
    )
    (net (code "368") (name "WRTM") (class "Default")
      (node (ref "B11") (pin "A1") (pinfunction "IN1_A1") (pintype "input"))
      (node (ref "C10") (pin "K2") (pinfunction "IN1A_K2") (pintype "input"))
      (node (ref "C12") (pin "N2") (pinfunction "IN1_N2") (pintype "input"))
      (node (ref "D07") (pin "H2") (pinfunction "O6_H2") (pintype "output"))
    )
    (net (code "369") (name "WRTM+FR03") (class "Default")
      (node (ref "B08") (pin "K2") (pinfunction "OUT_K2") (pintype "output"))
      (node (ref "C12") (pin "M1") (pinfunction "IN3_M1") (pintype "input"))
      (node (ref "C12") (pin "V2") (pinfunction "IN3_V2") (pintype "input"))
    )
    (net (code "370") (name "WR_EN") (class "Default")
      (node (ref "A20") (pin "R2") (pinfunction "R2_R2") (pintype "input"))
      (node (ref "A21") (pin "R2") (pinfunction "R2_R2") (pintype "input"))
      (node (ref "A26") (pin "F1") (pinfunction "P$2_F1") (pintype "bidirectional"))
      (node (ref "B20") (pin "R2") (pinfunction "R2_R2") (pintype "input"))
      (node (ref "C10") (pin "H2") (pinfunction "IN2B_H2") (pintype "input"))
      (node (ref "C10") (pin "U2") (pinfunction "IN2B_U2") (pintype "input"))
      (node (ref "C12") (pin "D2") (pinfunction "IN1_D2") (pintype "input"))
      (node (ref "C14") (pin "U1") (pinfunction "0_U1") (pintype "output"))
      (node (ref "C15") (pin "A1") (pinfunction "IN1_A1") (pintype "input"))
      (node (ref "C15") (pin "M1") (pinfunction "IN2_M1") (pintype "input"))
      (node (ref "D09") (pin "B1") (pinfunction "IN1B_B1") (pintype "input"))
      (node (ref "D09") (pin "E2") (pinfunction "IN1B_E2") (pintype "input"))
      (node (ref "D09") (pin "H1") (pinfunction "IN1B_H1") (pintype "input"))
      (node (ref "D09") (pin "L2") (pinfunction "IN1B_L2") (pintype "input"))
      (node (ref "D09") (pin "N1") (pinfunction "IN1B_N1") (pintype "input"))
      (node (ref "D09") (pin "S2") (pinfunction "IN1B_S2") (pintype "input"))
    )
    (net (code "371") (name "XOR_TO_LPB") (class "Default")
      (node (ref "C10") (pin "E2") (pinfunction "IN1B_E2") (pintype "input"))
      (node (ref "C10") (pin "F2") (pinfunction "IN2A_F2") (pintype "input"))
      (node (ref "C10") (pin "S2") (pinfunction "IN1B_S2") (pintype "input"))
      (node (ref "C10") (pin "T2") (pinfunction "IN2A_T2") (pintype "input"))
      (node (ref "D12") (pin "P2") (pinfunction "OUT_P2") (pintype "output"))
    )
    (net (code "372") (name "XSAD") (class "Default")
      (node (ref "A09") (pin "R1") (pinfunction "IN4_R1") (pintype "input"))
      (node (ref "A11") (pin "L2") (pinfunction "OUT_L2") (pintype "output"))
    )
    (net (code "373") (name "XSA_DY") (class "Default")
      (node (ref "A08") (pin "D2") (pinfunction "C_D2") (pintype "input"))
      (node (ref "B14") (pin "B1") (pinfunction "C_B1") (pintype "input"))
      (node (ref "B14") (pin "L2") (pinfunction "C_L2") (pintype "input"))
      (node (ref "C17") (pin "T2") (pinfunction "OUT_T2") (pintype "output"))
    )
    (net (code "374") (name "XSTA") (class "Default")
      (node (ref "B07") (pin "B1") (pinfunction "B1_B1") (pintype "input"))
      (node (ref "B07") (pin "D2") (pinfunction "D2_D2") (pintype "input"))
      (node (ref "B07") (pin "H1") (pinfunction "H1_H1") (pintype "input"))
      (node (ref "B07") (pin "L2") (pinfunction "L2_L2") (pintype "input"))
      (node (ref "B07") (pin "N1") (pinfunction "N1_N1") (pintype "input"))
      (node (ref "B07") (pin "S2") (pinfunction "S2_S2") (pintype "input"))
      (node (ref "C04") (pin "E1") (pinfunction "E1_E1") (pintype "output"))
      (node (ref "C07") (pin "B1") (pinfunction "B1_B1") (pintype "input"))
      (node (ref "C07") (pin "D2") (pinfunction "D2_D2") (pintype "input"))
      (node (ref "C07") (pin "H1") (pinfunction "H1_H1") (pintype "input"))
      (node (ref "C07") (pin "L2") (pinfunction "L2_L2") (pintype "input"))
      (node (ref "D11") (pin "N1") (pinfunction "C_N1") (pintype "input"))
      (node (ref "D13") (pin "M2") (pinfunction "K2_M2") (pintype "input"))
      (node (ref "D13") (pin "N2") (pinfunction "J2_N2") (pintype "input"))
      (node (ref "D13") (pin "P2") (pinfunction "H2_P2") (pintype "input"))
    )
    (net (code "375") (name "unconnected-(A07A-O8-PadP2)") (class "Default")
      (node (ref "A07") (pin "P2") (pinfunction "O8_P2") (pintype "output"))
    )
    (net (code "376") (name "unconnected-(A07A-O9-PadR2)") (class "Default")
      (node (ref "A07") (pin "R2") (pinfunction "O9_R2") (pintype "output"))
    )
    (net (code "377") (name "unconnected-(A07A-~{O8}-PadP1)") (class "Default")
      (node (ref "A07") (pin "P1") (pinfunction "~{O8}_P1") (pintype "output"))
    )
    (net (code "378") (name "unconnected-(A07A-~{O9}-PadR1)") (class "Default")
      (node (ref "A07") (pin "R1") (pinfunction "~{O9}_R1") (pintype "output"))
    )
    (net (code "379") (name "unconnected-(A14-PadD1)") (class "Default")
      (node (ref "A14") (pin "D1") (pinfunction "D1_D1") (pintype "passive"))
    )
    (net (code "380") (name "unconnected-(A14-PadE1)") (class "Default")
      (node (ref "A14") (pin "E1") (pinfunction "E1_E1") (pintype "passive"))
    )
    (net (code "381") (name "unconnected-(A14-PadF1)") (class "Default")
      (node (ref "A14") (pin "F1") (pinfunction "F1_F1") (pintype "passive"))
    )
    (net (code "382") (name "unconnected-(A14-PadJ1)") (class "Default")
      (node (ref "A14") (pin "J1") (pinfunction "J1_J1") (pintype "passive"))
    )
    (net (code "383") (name "unconnected-(A14D-D1-PadN1)") (class "Default")
      (node (ref "A14") (pin "N1") (pinfunction "D1_N1") (pintype "passive"))
    )
    (net (code "384") (name "unconnected-(A14D-E1-PadP1)") (class "Default")
      (node (ref "A14") (pin "P1") (pinfunction "E1_P1") (pintype "passive"))
    )
    (net (code "385") (name "unconnected-(A14D-F1-PadR1)") (class "Default")
      (node (ref "A14") (pin "R1") (pinfunction "F1_R1") (pintype "passive"))
    )
    (net (code "386") (name "unconnected-(A14D-J1-PadU1)") (class "Default")
      (node (ref "A14") (pin "U1") (pinfunction "J1_U1") (pintype "passive"))
    )
    (net (code "387") (name "unconnected-(A18-PadH2)") (class "Default")
      (node (ref "A18") (pin "H2") (pinfunction "H2_H2") (pintype "input"))
    )
    (net (code "388") (name "unconnected-(A18-PadL2)") (class "Default")
      (node (ref "A18") (pin "L2") (pinfunction "L2_L2") (pintype "input"))
    )
    (net (code "389") (name "unconnected-(A18-PadM2)") (class "Default")
      (node (ref "A18") (pin "M2") (pinfunction "M2_M2") (pintype "input"))
    )
    (net (code "390") (name "unconnected-(A20-PadH2)") (class "Default")
      (node (ref "A20") (pin "H2") (pinfunction "H2_H2") (pintype "input"))
    )
    (net (code "391") (name "unconnected-(A20-PadL2)") (class "Default")
      (node (ref "A20") (pin "L2") (pinfunction "L2_L2") (pintype "input"))
    )
    (net (code "392") (name "unconnected-(A20-PadM2)") (class "Default")
      (node (ref "A20") (pin "M2") (pinfunction "M2_M2") (pintype "input"))
    )
    (net (code "393") (name "unconnected-(A21-PadH2)") (class "Default")
      (node (ref "A21") (pin "H2") (pinfunction "H2_H2") (pintype "input"))
    )
    (net (code "394") (name "unconnected-(A21-PadL2)") (class "Default")
      (node (ref "A21") (pin "L2") (pinfunction "L2_L2") (pintype "input"))
    )
    (net (code "395") (name "unconnected-(A21-PadM2)") (class "Default")
      (node (ref "A21") (pin "M2") (pinfunction "M2_M2") (pintype "input"))
    )
    (net (code "396") (name "unconnected-(A22-PadE2)") (class "Default")
      (node (ref "A22") (pin "E2") (pinfunction "E2_E2") (pintype "passive"))
    )
    (net (code "397") (name "unconnected-(AB01-PadBM1)") (class "Default")
      (node (ref "AB01") (pin "BM1") (pinfunction "BM1_BM1") (pintype "output"))
    )
    (net (code "398") (name "unconnected-(AB01-PadBN1)") (class "Default")
      (node (ref "AB01") (pin "BN1") (pinfunction "BN1_BN1") (pintype "input"))
    )
    (net (code "399") (name "unconnected-(AB01-PadBP1)") (class "Default")
      (node (ref "AB01") (pin "BP1") (pinfunction "BP1_BP1") (pintype "input"))
    )
    (net (code "400") (name "unconnected-(AB01-PadBR1)") (class "Default")
      (node (ref "AB01") (pin "BR1") (pinfunction "BR1_BR1") (pintype "output"))
    )
    (net (code "401") (name "unconnected-(B05H-B-PadL2)") (class "Default")
      (node (ref "B05") (pin "L2") (pinfunction "B_L2") (pintype "input"))
    )
    (net (code "402") (name "unconnected-(B05H-E-PadP2)") (class "Default")
      (node (ref "B05") (pin "P2") (pinfunction "E_P2") (pintype "open_collector"))
    )
    (net (code "403") (name "unconnected-(B18-PadH2)") (class "Default")
      (node (ref "B18") (pin "H2") (pinfunction "H2_H2") (pintype "input"))
    )
    (net (code "404") (name "unconnected-(B18-PadL2)") (class "Default")
      (node (ref "B18") (pin "L2") (pinfunction "L2_L2") (pintype "input"))
    )
    (net (code "405") (name "unconnected-(B18-PadM2)") (class "Default")
      (node (ref "B18") (pin "M2") (pinfunction "M2_M2") (pintype "input"))
    )
    (net (code "406") (name "unconnected-(B20-PadH2)") (class "Default")
      (node (ref "B20") (pin "H2") (pinfunction "H2_H2") (pintype "input"))
    )
    (net (code "407") (name "unconnected-(B20-PadL2)") (class "Default")
      (node (ref "B20") (pin "L2") (pinfunction "L2_L2") (pintype "input"))
    )
    (net (code "408") (name "unconnected-(B20-PadM2)") (class "Default")
      (node (ref "B20") (pin "M2") (pinfunction "M2_M2") (pintype "input"))
    )
    (net (code "409") (name "unconnected-(B22K-A-PadR2)") (class "Default")
      (node (ref "B22") (pin "R2") (pinfunction "A_R2") (pintype "input"))
    )
    (net (code "410") (name "unconnected-(B22K-D-PadU2)") (class "Default")
      (node (ref "B22") (pin "U2") (pinfunction "D_U2") (pintype "output"))
    )
    (net (code "411") (name "unconnected-(C02A-IN13-PadP2)") (class "Default")
      (node (ref "C02") (pin "P2") (pinfunction "IN13_P2") (pintype "input"))
    )
    (net (code "412") (name "unconnected-(C02A-IN14-PadS2)") (class "Default")
      (node (ref "C02") (pin "S2") (pinfunction "IN14_S2") (pintype "input"))
    )
    (net (code "413") (name "unconnected-(C02A-O13-PadR2)") (class "Default")
      (node (ref "C02") (pin "R2") (pinfunction "O13_R2") (pintype "output"))
    )
    (net (code "414") (name "unconnected-(C02A-O14-PadT2)") (class "Default")
      (node (ref "C02") (pin "T2") (pinfunction "O14_T2") (pintype "output"))
    )
    (net (code "415") (name "unconnected-(C03A-IN13-PadP2)") (class "Default")
      (node (ref "C03") (pin "P2") (pinfunction "IN13_P2") (pintype "input"))
    )
    (net (code "416") (name "unconnected-(C03A-IN14-PadS2)") (class "Default")
      (node (ref "C03") (pin "S2") (pinfunction "IN14_S2") (pintype "input"))
    )
    (net (code "417") (name "unconnected-(C03A-IN15-PadU2)") (class "Default")
      (node (ref "C03") (pin "U2") (pinfunction "IN15_U2") (pintype "input"))
    )
    (net (code "418") (name "unconnected-(C03A-O13-PadR2)") (class "Default")
      (node (ref "C03") (pin "R2") (pinfunction "O13_R2") (pintype "output"))
    )
    (net (code "419") (name "unconnected-(C03A-O14-PadT2)") (class "Default")
      (node (ref "C03") (pin "T2") (pinfunction "O14_T2") (pintype "output"))
    )
    (net (code "420") (name "unconnected-(C03A-O15-PadV2)") (class "Default")
      (node (ref "C03") (pin "V2") (pinfunction "O15_V2") (pintype "output"))
    )
    (net (code "421") (name "unconnected-(C07-PadN1)") (class "Default")
      (node (ref "C07") (pin "N1") (pinfunction "N1_N1") (pintype "input"))
    )
    (net (code "422") (name "unconnected-(C07-PadP1)") (class "Default")
      (node (ref "C07") (pin "P1") (pinfunction "P1_P1") (pintype "input"))
    )
    (net (code "423") (name "unconnected-(C07-PadR1)") (class "Default")
      (node (ref "C07") (pin "R1") (pinfunction "R1_R1") (pintype "input"))
    )
    (net (code "424") (name "unconnected-(C07-PadS1)") (class "Default")
      (node (ref "C07") (pin "S1") (pinfunction "S1_S1") (pintype "output"))
    )
    (net (code "425") (name "unconnected-(C07-PadS2)") (class "Default")
      (node (ref "C07") (pin "S2") (pinfunction "S2_S2") (pintype "input"))
    )
    (net (code "426") (name "unconnected-(C07-PadT2)") (class "Default")
      (node (ref "C07") (pin "T2") (pinfunction "T2_T2") (pintype "input"))
    )
    (net (code "427") (name "unconnected-(C07-PadU1)") (class "Default")
      (node (ref "C07") (pin "U1") (pinfunction "U1_U1") (pintype "output"))
    )
    (net (code "428") (name "unconnected-(C07-PadU2)") (class "Default")
      (node (ref "C07") (pin "U2") (pinfunction "U2_U2") (pintype "input"))
    )
    (net (code "429") (name "unconnected-(C07-PadV1)") (class "Default")
      (node (ref "C07") (pin "V1") (pinfunction "V1_V1") (pintype "output"))
    )
    (net (code "430") (name "unconnected-(C07-PadV2)") (class "Default")
      (node (ref "C07") (pin "V2") (pinfunction "V2_V2") (pintype "output"))
    )
    (net (code "431") (name "unconnected-(CD18-PadAN2)") (class "Default")
      (node (ref "CD18") (pin "AN2") (pinfunction "AN2_AN2") (pintype "output"))
    )
    (net (code "432") (name "unconnected-(CD18-PadAU1)") (class "Default")
      (node (ref "CD18") (pin "AU1") (pinfunction "AU1_AU1") (pintype "output"))
    )
    (net (code "433") (name "unconnected-(D07A-O8-PadP2)") (class "Default")
      (node (ref "D07") (pin "P2") (pinfunction "O8_P2") (pintype "output"))
    )
    (net (code "434") (name "unconnected-(D07A-O9-PadR2)") (class "Default")
      (node (ref "D07") (pin "R2") (pinfunction "O9_R2") (pintype "output"))
    )
    (net (code "435") (name "unconnected-(D07A-~{O8}-PadP1)") (class "Default")
      (node (ref "D07") (pin "P1") (pinfunction "~{O8}_P1") (pintype "output"))
    )
    (net (code "436") (name "unconnected-(D07A-~{O9}-PadR1)") (class "Default")
      (node (ref "D07") (pin "R1") (pinfunction "~{O9}_R1") (pintype "output"))
    )
    (net (code "437") (name "unconnected-(D13-PadD2)") (class "Default")
      (node (ref "D13") (pin "D2") (pinfunction "D2_D2") (pintype "passive"))
    )
    (net (code "438") (name "unconnected-(D13-PadE2)") (class "Default")
      (node (ref "D13") (pin "E2") (pinfunction "E2_E2") (pintype "passive"))
    )
    (net (code "439") (name "unconnected-(D14-PadN2)") (class "Default")
      (node (ref "D14") (pin "N2") (pinfunction "N2_N2") (pintype "passive"))
    )
    (net (code "440") (name "unconnected-(D14-PadP2)") (class "Default")
      (node (ref "D14") (pin "P2") (pinfunction "P2_P2") (pintype "passive"))
    )
    (net (code "441") (name "unconnected-(D14-PadR2)") (class "Default")
      (node (ref "D14") (pin "R2") (pinfunction "R2_R2") (pintype "passive"))
    )
    (net (code "442") (name "unconnected-(D14-PadS2)") (class "Default")
      (node (ref "D14") (pin "S2") (pinfunction "S2_S2") (pintype "passive"))
    )
    (net (code "443") (name "unconnected-(D14-PadU2)") (class "Default")
      (node (ref "D14") (pin "U2") (pinfunction "U2_U2") (pintype "passive"))
    )
    (net (code "444") (name "unconnected-(D14E-N2-PadJ1)") (class "Default")
      (node (ref "D14") (pin "J1") (pinfunction "N2_J1") (pintype "passive"))
    )
    (net (code "445") (name "unconnected-(D14E-R2-PadF1)") (class "Default")
      (node (ref "D14") (pin "F1") (pinfunction "R2_F1") (pintype "passive"))
    )
    (net (code "446") (name "unconnected-(D14E-S2-PadE1)") (class "Default")
      (node (ref "D14") (pin "E1") (pinfunction "S2_E1") (pintype "passive"))
    )
    (net (code "447") (name "unconnected-(D14E-U2-PadD1)") (class "Default")
      (node (ref "D14") (pin "D1") (pinfunction "U2_D1") (pintype "passive"))
    )
    (net (code "448") (name "unconnected-(D14E-V2-PadB1)") (class "Default")
      (node (ref "D14") (pin "B1") (pinfunction "V2_B1") (pintype "passive"))
    )
    (net (code "449") (name "unconnected-(D15-PadE2)") (class "Default")
      (node (ref "D15") (pin "E2") (pinfunction "E2_E2") (pintype "output"))
    )
    (net (code "450") (name "unconnected-(D15-PadM2)") (class "Default")
      (node (ref "D15") (pin "M2") (pinfunction "M2_M2") (pintype "passive"))
    )
    (net (code "451") (name "unconnected-(D15-PadP2)") (class "Default")
      (node (ref "D15") (pin "P2") (pinfunction "P2_P2") (pintype "passive"))
    )
    (net (code "452") (name "unconnected-(D15-PadR2)") (class "Default")
      (node (ref "D15") (pin "R2") (pinfunction "R2_R2") (pintype "passive"))
    )
    (net (code "453") (name "unconnected-(D15-PadT2)") (class "Default")
      (node (ref "D15") (pin "T2") (pinfunction "T2_T2") (pintype "passive"))
    )
    (net (code "454") (name "unconnected-(D16D-D1-PadN1)") (class "Default")
      (node (ref "D16") (pin "N1") (pinfunction "D1_N1") (pintype "passive"))
    )
    (net (code "455") (name "unconnected-(D16D-E1-PadP1)") (class "Default")
      (node (ref "D16") (pin "P1") (pinfunction "E1_P1") (pintype "passive"))
    )
    (net (code "456") (name "unconnected-(D16D-F1-PadR1)") (class "Default")
      (node (ref "D16") (pin "R1") (pinfunction "F1_R1") (pintype "passive"))
    )
    (net (code "457") (name "unconnected-(D16D-J1-PadU1)") (class "Default")
      (node (ref "D16") (pin "U1") (pinfunction "J1_U1") (pintype "passive"))
    )
    (net (code "458") (name "~{0_TO_AC}") (class "Default")
      (node (ref "B05") (pin "H1") (pinfunction "B_H1") (pintype "input"))
      (node (ref "B06") (pin "T2") (pinfunction "OUT_T2") (pintype "output"))
    )
    (net (code "459") (name "~{0_TO_DTB}") (class "Default")
      (node (ref "A11") (pin "L1") (pinfunction "IN_L1") (pintype "input"))
      (node (ref "B09") (pin "A1") (pinfunction "R_A1") (pintype "input"))
      (node (ref "B09") (pin "K2") (pinfunction "R_K2") (pintype "input"))
      (node (ref "B10") (pin "L1") (pinfunction "OUT_L1") (pintype "output"))
      (node (ref "C09") (pin "A1") (pinfunction "R_A1") (pintype "input"))
      (node (ref "C09") (pin "K2") (pinfunction "R_K2") (pintype "input"))
    )
    (net (code "460") (name "~{0_TO_EF}") (class "Default")
      (node (ref "A08") (pin "A1") (pinfunction "R_A1") (pintype "input"))
      (node (ref "A08") (pin "N2") (pinfunction "S_N2") (pintype "input"))
      (node (ref "A08") (pin "R1") (pinfunction "S_R1") (pintype "input"))
      (node (ref "A11") (pin "F2") (pinfunction "OUT_F2") (pintype "output"))
    )
    (net (code "461") (name "~{0_TO_LPB}") (class "Default")
      (node (ref "D08") (pin "A1") (pinfunction "A1_A1") (pintype "input"))
      (node (ref "D08") (pin "K2") (pinfunction "K2_K2") (pintype "input"))
      (node (ref "D12") (pin "J2") (pinfunction "OUT_J2") (pintype "output"))
    )
    (net (code "462") (name "~{0_TO_STATE}") (class "Default")
      (node (ref "C16") (pin "L1") (pinfunction "OUT_L1") (pintype "output"))
      (node (ref "CD18") (pin "AV2") (pinfunction "AV2_AV2") (pintype "input"))
    )
    (net (code "463") (name "~{0_TO_STA}") (class "Default")
      (node (ref "A11") (pin "P1") (pinfunction "OUT_P1") (pintype "output"))
      (node (ref "B07") (pin "A1") (pinfunction "A1_A1") (pintype "input"))
      (node (ref "B07") (pin "K2") (pinfunction "K2_K2") (pintype "input"))
      (node (ref "B11") (pin "P2") (pinfunction "IN2_P2") (pintype "input"))
      (node (ref "C07") (pin "A1") (pinfunction "A1_A1") (pintype "input"))
    )
    (net (code "464") (name "~{0_TO_W}") (class "Default")
      (node (ref "C16") (pin "E1") (pinfunction "OUT_E1") (pintype "output"))
      (node (ref "CD18") (pin "BH2") (pinfunction "BH2_BH2") (pintype "input"))
    )
    (net (code "465") (name "~{00}") (class "Default")
      (node (ref "A07") (pin "D1") (pinfunction "~{O0}_D1") (pintype "output"))
      (node (ref "B22") (pin "S2") (pinfunction "B_S2") (pintype "input"))
    )
    (net (code "466") (name "~{01}") (class "Default")
      (node (ref "A07") (pin "E1") (pinfunction "~{O1}_E1") (pintype "output"))
      (node (ref "A23") (pin "N1") (pinfunction "B_N1") (pintype "input"))
    )
    (net (code "467") (name "~{02}") (class "Default")
      (node (ref "A07") (pin "J1") (pinfunction "~{O2}_J1") (pintype "output"))
      (node (ref "A23") (pin "D2") (pinfunction "A_D2") (pintype "input"))
    )
    (net (code "468") (name "~{03}") (class "Default")
      (node (ref "A07") (pin "N1") (pinfunction "~{O3}_N1") (pintype "output"))
      (node (ref "A23") (pin "E2") (pinfunction "B_E2") (pintype "input"))
    )
    (net (code "469") (name "~{04}") (class "Default")
      (node (ref "A07") (pin "F1") (pinfunction "~{O4}_F1") (pintype "output"))
      (node (ref "A23") (pin "K2") (pinfunction "A_K2") (pintype "input"))
    )
    (net (code "470") (name "~{05}") (class "Default")
      (node (ref "A07") (pin "M1") (pinfunction "~{O5}_M1") (pintype "output"))
      (node (ref "A23") (pin "L2") (pinfunction "B_L2") (pintype "input"))
    )
    (net (code "471") (name "~{06}") (class "Default")
      (node (ref "A07") (pin "H1") (pinfunction "~{O6}_H1") (pintype "output"))
      (node (ref "A23") (pin "R2") (pinfunction "A_R2") (pintype "input"))
    )
    (net (code "472") (name "~{07}") (class "Default")
      (node (ref "A07") (pin "L1") (pinfunction "~{O7}_L1") (pintype "output"))
      (node (ref "A23") (pin "S2") (pinfunction "B_S2") (pintype "input"))
    )
    (net (code "473") (name "~{76}") (class "Default")
      (node (ref "C06") (pin "T2") (pinfunction "OUT_T2") (pintype "output"))
      (node (ref "D12") (pin "R2") (pinfunction "IN1_R2") (pintype "input"))
      (node (ref "D12") (pin "S2") (pinfunction "IN2_S2") (pintype "input"))
    )
    (net (code "474") (name "~{77}") (class "Default")
      (node (ref "C06") (pin "V2") (pinfunction "OUT_V2") (pintype "output"))
      (node (ref "D12") (pin "T2") (pinfunction "IN3_T2") (pintype "input"))
      (node (ref "D12") (pin "U2") (pinfunction "IN4_U2") (pintype "input"))
    )
    (net (code "475") (name "~{ADDR_ACC}") (class "Default")
      (node (ref "B08") (pin "T2") (pinfunction "IN1_T2") (pintype "input"))
      (node (ref "C17") (pin "P1") (pinfunction "OUT_P1") (pintype "output"))
    )
    (net (code "476") (name "~{B-BRK}") (class "Default")
      (node (ref "B02") (pin "C1") (pinfunction "C_C1") (pintype "input"))
      (node (ref "B02") (pin "F2") (pinfunction "C_F2") (pintype "input"))
      (node (ref "B02") (pin "J1") (pinfunction "C_J1") (pintype "input"))
      (node (ref "B02") (pin "M2") (pinfunction "C_M2") (pintype "input"))
      (node (ref "B02") (pin "P1") (pinfunction "C_P1") (pintype "input"))
      (node (ref "B02") (pin "T2") (pinfunction "C_T2") (pintype "input"))
      (node (ref "B10") (pin "V2") (pinfunction "OUT_V2") (pintype "output"))
    )
    (net (code "477") (name "~{BAC_00}") (class "Default")
      (node (ref "B06") (pin "A1") (pinfunction "IN_A1") (pintype "input"))
      (node (ref "C03") (pin "B1") (pinfunction "O1_B1") (pintype "output"))
      (node (ref "D10") (pin "F1") (pinfunction "IN1_F1") (pintype "input"))
    )
    (net (code "478") (name "~{BAC_01}") (class "Default")
      (node (ref "B06") (pin "D1") (pinfunction "IN_D1") (pintype "input"))
      (node (ref "C03") (pin "E1") (pinfunction "O2_E1") (pintype "output"))
      (node (ref "D10") (pin "H1") (pinfunction "IN2_H1") (pintype "input"))
    )
    (net (code "479") (name "~{BAC_02}") (class "Default")
      (node (ref "B06") (pin "F1") (pinfunction "IN_F1") (pintype "input"))
      (node (ref "C03") (pin "H1") (pinfunction "O3_H1") (pintype "output"))
      (node (ref "D10") (pin "J1") (pinfunction "IN3_J1") (pintype "input"))
    )
    (net (code "480") (name "~{BAC_03}") (class "Default")
      (node (ref "B06") (pin "J1") (pinfunction "IN_J1") (pintype "input"))
      (node (ref "C03") (pin "K1") (pinfunction "O4_K1") (pintype "output"))
      (node (ref "D10") (pin "K1") (pinfunction "IN4_K1") (pintype "input"))
    )
    (net (code "481") (name "~{BAC_04}") (class "Default")
      (node (ref "B06") (pin "L1") (pinfunction "IN_L1") (pintype "input"))
      (node (ref "C03") (pin "M1") (pinfunction "O5_M1") (pintype "output"))
      (node (ref "D10") (pin "K2") (pinfunction "IN5_K2") (pintype "input"))
    )
    (net (code "482") (name "~{BAC_05}") (class "Default")
      (node (ref "B06") (pin "N1") (pinfunction "IN_N1") (pintype "input"))
      (node (ref "C03") (pin "P1") (pinfunction "O6_P1") (pintype "output"))
    )
    (net (code "483") (name "~{BAC_06}") (class "Default")
      (node (ref "B06") (pin "R1") (pinfunction "IN_R1") (pintype "input"))
      (node (ref "C03") (pin "S1") (pinfunction "O7_S1") (pintype "output"))
    )
    (net (code "484") (name "~{BAC_07}") (class "Default")
      (node (ref "B06") (pin "V1") (pinfunction "IN_V1") (pintype "input"))
      (node (ref "C03") (pin "U1") (pinfunction "O8_U1") (pintype "output"))
    )
    (net (code "485") (name "~{BAC_08}") (class "Default")
      (node (ref "B06") (pin "C1") (pinfunction "IN_C1") (pintype "input"))
      (node (ref "C03") (pin "F2") (pinfunction "O9_F2") (pintype "output"))
    )
    (net (code "486") (name "~{BAC_09}") (class "Default")
      (node (ref "B06") (pin "E2") (pinfunction "IN_E2") (pintype "input"))
      (node (ref "C03") (pin "J2") (pinfunction "O10_J2") (pintype "output"))
    )
    (net (code "487") (name "~{BAC_10}") (class "Default")
      (node (ref "A10") (pin "D2") (pinfunction "IN1_D2") (pintype "input"))
      (node (ref "B06") (pin "H2") (pinfunction "IN_H2") (pintype "input"))
      (node (ref "C03") (pin "L2") (pinfunction "O11_L2") (pintype "output"))
    )
    (net (code "488") (name "~{BAC_11}") (class "Default")
      (node (ref "B06") (pin "K2") (pinfunction "IN_K2") (pintype "input"))
      (node (ref "C03") (pin "N2") (pinfunction "O12_N2") (pintype "output"))
      (node (ref "C11") (pin "R2") (pinfunction "IN2_R2") (pintype "input"))
    )
    (net (code "489") (name "~{BLK_IN_SYNC}") (class "Default")
      (node (ref "A10") (pin "A1") (pinfunction "IN1_A1") (pintype "input"))
      (node (ref "C13") (pin "R1") (pinfunction "IN_R1") (pintype "input"))
      (node (ref "D10") (pin "J2") (pinfunction "OUT_J2") (pintype "output"))
    )
    (net (code "490") (name "~{BMB_00}") (class "Default")
      (node (ref "C02") (pin "B1") (pinfunction "O1_B1") (pintype "output"))
      (node (ref "C06") (pin "A1") (pinfunction "IN_A1") (pintype "input"))
    )
    (net (code "491") (name "~{BMB_01}") (class "Default")
      (node (ref "C02") (pin "E1") (pinfunction "O2_E1") (pintype "output"))
      (node (ref "C06") (pin "D1") (pinfunction "IN_D1") (pintype "input"))
    )
    (net (code "492") (name "~{BMB_02}") (class "Default")
      (node (ref "C02") (pin "H1") (pinfunction "O3_H1") (pintype "output"))
      (node (ref "C06") (pin "F1") (pinfunction "IN_F1") (pintype "input"))
    )
    (net (code "493") (name "~{BMB_03}") (class "Default")
      (node (ref "C02") (pin "K1") (pinfunction "O4_K1") (pintype "output"))
      (node (ref "C06") (pin "J1") (pinfunction "IN_J1") (pintype "input"))
    )
    (net (code "494") (name "~{BMB_04}") (class "Default")
      (node (ref "C02") (pin "M1") (pinfunction "O5_M1") (pintype "output"))
      (node (ref "C06") (pin "L1") (pinfunction "IN_L1") (pintype "input"))
    )
    (net (code "495") (name "~{BMB_05}") (class "Default")
      (node (ref "C02") (pin "P1") (pinfunction "O6_P1") (pintype "output"))
      (node (ref "C06") (pin "N1") (pinfunction "IN_N1") (pintype "input"))
    )
    (net (code "496") (name "~{BMB_06}") (class "Default")
      (node (ref "C02") (pin "S1") (pinfunction "O7_S1") (pintype "output"))
      (node (ref "C06") (pin "R1") (pinfunction "IN_R1") (pintype "input"))
    )
    (net (code "497") (name "~{BMB_07}") (class "Default")
      (node (ref "C02") (pin "U1") (pinfunction "O8_U1") (pintype "output"))
      (node (ref "C06") (pin "V1") (pinfunction "IN_V1") (pintype "input"))
    )
    (net (code "498") (name "~{BMB_08}") (class "Default")
      (node (ref "C02") (pin "F2") (pinfunction "O9_F2") (pintype "output"))
      (node (ref "C06") (pin "C1") (pinfunction "IN_C1") (pintype "input"))
    )
    (net (code "499") (name "~{BMB_09}") (class "Default")
      (node (ref "C02") (pin "J2") (pinfunction "O10_J2") (pintype "output"))
      (node (ref "C06") (pin "E2") (pinfunction "IN_E2") (pintype "input"))
    )
    (net (code "500") (name "~{BMB_10}") (class "Default")
      (node (ref "C02") (pin "L2") (pinfunction "O11_L2") (pintype "output"))
      (node (ref "C06") (pin "H2") (pinfunction "IN_H2") (pintype "input"))
    )
    (net (code "501") (name "~{BMB_11}") (class "Default")
      (node (ref "C02") (pin "N2") (pinfunction "O12_N2") (pintype "output"))
      (node (ref "C06") (pin "K2") (pinfunction "IN_K2") (pintype "input"))
    )
    (net (code "502") (name "~{BMR00}") (class "Default")
      (node (ref "A23") (pin "H1") (pinfunction "B_H1") (pintype "input"))
      (node (ref "B14") (pin "R2") (pinfunction "0_R2") (pintype "output"))
    )
    (net (code "503") (name "~{BMR01}") (class "Default")
      (node (ref "A23") (pin "A1") (pinfunction "A_A1") (pintype "input"))
      (node (ref "B14") (pin "E1") (pinfunction "1_E1") (pintype "output"))
    )
    (net (code "504") (name "~{C00}") (class "Default")
      (node (ref "A12") (pin "P2") (pinfunction "IN1_P2") (pintype "input"))
      (node (ref "B13") (pin "P1") (pinfunction "D_P1") (pintype "input"))
      (node (ref "B13") (pin "S2") (pinfunction "C_S2") (pintype "input"))
      (node (ref "B13") (pin "U1") (pinfunction "0_U1") (pintype "output"))
      (node (ref "B15") (pin "H1") (pinfunction "IN1_H1") (pintype "input"))
      (node (ref "C15") (pin "J2") (pinfunction "IN2_J2") (pintype "input"))
    )
    (net (code "505") (name "~{C01}") (class "Default")
      (node (ref "A12") (pin "R2") (pinfunction "IN2_R2") (pintype "input"))
      (node (ref "B10") (pin "P1") (pinfunction "IN3_P1") (pintype "input"))
      (node (ref "B13") (pin "M2") (pinfunction "D_M2") (pintype "input"))
      (node (ref "B13") (pin "R2") (pinfunction "0_R2") (pintype "output"))
      (node (ref "C12") (pin "F2") (pinfunction "IN3_F2") (pintype "input"))
      (node (ref "D10") (pin "D1") (pinfunction "IN4_D1") (pintype "input"))
    )
    (net (code "506") (name "~{CK00}") (class "Default")
      (node (ref "A18") (pin "N2") (pinfunction "N2_N2") (pintype "input"))
      (node (ref "B14") (pin "T2") (pinfunction "D_T2") (pintype "input"))
      (node (ref "B14") (pin "U1") (pinfunction "0_U1") (pintype "output"))
    )
    (net (code "507") (name "~{CK01}") (class "Default")
      (node (ref "B14") (pin "V1") (pinfunction "0_V1") (pintype "output"))
      (node (ref "C16") (pin "S2") (pinfunction "IN2_S2") (pintype "input"))
      (node (ref "C16") (pin "T2") (pinfunction "IN3_T2") (pintype "input"))
      (node (ref "C16") (pin "U2") (pinfunction "IN4_U2") (pintype "input"))
    )
    (net (code "508") (name "~{CLR_DF}") (class "Default")
      (node (ref "A11") (pin "U1") (pinfunction "OUT_U1") (pintype "output"))
      (node (ref "D11") (pin "N2") (pinfunction "S_N2") (pintype "input"))
    )
    (net (code "509") (name "~{CLR_DTF}") (class "Default")
      (node (ref "C13") (pin "U1") (pinfunction "OUT_U1") (pintype "output"))
      (node (ref "D11") (pin "U2") (pinfunction "S_U2") (pintype "input"))
    )
    (net (code "510") (name "~{CSTA}") (class "Default")
      (node (ref "A10") (pin "L2") (pinfunction "IN1_L2") (pintype "input"))
      (node (ref "C04") (pin "D1") (pinfunction "D1_D1") (pintype "output"))
    )
    (net (code "511") (name "~{DATA}") (class "Default")
      (node (ref "B12") (pin "N1") (pinfunction "IN2_N1") (pintype "input"))
      (node (ref "C11") (pin "L2") (pinfunction "IN1_L2") (pintype "input"))
      (node (ref "C13") (pin "H1") (pinfunction "OUT_H1") (pintype "output"))
      (node (ref "C16") (pin "D2") (pinfunction "IN1_D2") (pintype "input"))
    )
    (net (code "512") (name "~{DB_00}") (class "Default")
      (node (ref "A06") (pin "B1") (pinfunction "P$2_B1") (pintype "bidirectional"))
      (node (ref "B02") (pin "D1") (pinfunction "D_D1") (pintype "open_collector"))
      (node (ref "D06") (pin "B1") (pinfunction "P$2_B1") (pintype "bidirectional"))
    )
    (net (code "513") (name "~{DB_01}") (class "Default")
      (node (ref "A06") (pin "D1") (pinfunction "P$2_D1") (pintype "bidirectional"))
      (node (ref "B02") (pin "E1") (pinfunction "E_E1") (pintype "open_collector"))
      (node (ref "D06") (pin "D1") (pinfunction "P$2_D1") (pintype "bidirectional"))
    )
    (net (code "514") (name "~{DB_02}") (class "Default")
      (node (ref "A06") (pin "E1") (pinfunction "P$2_E1") (pintype "bidirectional"))
      (node (ref "B02") (pin "K1") (pinfunction "D_K1") (pintype "open_collector"))
      (node (ref "D06") (pin "E1") (pinfunction "P$2_E1") (pintype "bidirectional"))
    )
    (net (code "515") (name "~{DB_03}") (class "Default")
      (node (ref "A06") (pin "H1") (pinfunction "P$2_H1") (pintype "bidirectional"))
      (node (ref "B02") (pin "L1") (pinfunction "E_L1") (pintype "open_collector"))
      (node (ref "D06") (pin "H1") (pinfunction "P$2_H1") (pintype "bidirectional"))
    )
    (net (code "516") (name "~{DB_04}") (class "Default")
      (node (ref "A06") (pin "J1") (pinfunction "P$2_J1") (pintype "bidirectional"))
      (node (ref "B02") (pin "R1") (pinfunction "D_R1") (pintype "open_collector"))
      (node (ref "D06") (pin "J1") (pinfunction "P$2_J1") (pintype "bidirectional"))
    )
    (net (code "517") (name "~{DB_05}") (class "Default")
      (node (ref "A06") (pin "L1") (pinfunction "P$2_L1") (pintype "bidirectional"))
      (node (ref "B02") (pin "S1") (pinfunction "E_S1") (pintype "open_collector"))
      (node (ref "D06") (pin "L1") (pinfunction "P$2_L1") (pintype "bidirectional"))
    )
    (net (code "518") (name "~{DB_06}") (class "Default")
      (node (ref "A06") (pin "M1") (pinfunction "P$2_M1") (pintype "bidirectional"))
      (node (ref "B02") (pin "H2") (pinfunction "D_H2") (pintype "open_collector"))
      (node (ref "D06") (pin "M1") (pinfunction "P$2_M1") (pintype "bidirectional"))
    )
    (net (code "519") (name "~{DB_07}") (class "Default")
      (node (ref "A06") (pin "P1") (pinfunction "P$2_P1") (pintype "bidirectional"))
      (node (ref "B02") (pin "J2") (pinfunction "E_J2") (pintype "open_collector"))
      (node (ref "D06") (pin "P1") (pinfunction "P$2_P1") (pintype "bidirectional"))
    )
    (net (code "520") (name "~{DB_08}") (class "Default")
      (node (ref "A06") (pin "S1") (pinfunction "P$2_S1") (pintype "bidirectional"))
      (node (ref "B02") (pin "N2") (pinfunction "D_N2") (pintype "open_collector"))
      (node (ref "D06") (pin "S1") (pinfunction "P$2_S1") (pintype "bidirectional"))
    )
    (net (code "521") (name "~{DB_09}") (class "Default")
      (node (ref "A06") (pin "D2") (pinfunction "P$2_D2") (pintype "bidirectional"))
      (node (ref "B02") (pin "P2") (pinfunction "E_P2") (pintype "open_collector"))
      (node (ref "D06") (pin "D2") (pinfunction "P$2_D2") (pintype "bidirectional"))
    )
    (net (code "522") (name "~{DB_10}") (class "Default")
      (node (ref "A06") (pin "E2") (pinfunction "P$2_E2") (pintype "bidirectional"))
      (node (ref "B02") (pin "U2") (pinfunction "D_U2") (pintype "open_collector"))
      (node (ref "D06") (pin "E2") (pinfunction "P$2_E2") (pintype "bidirectional"))
    )
    (net (code "523") (name "~{DB_11}") (class "Default")
      (node (ref "A06") (pin "H2") (pinfunction "P$2_H2") (pintype "bidirectional"))
      (node (ref "B02") (pin "V2") (pinfunction "E_V2") (pintype "open_collector"))
      (node (ref "D06") (pin "H2") (pinfunction "P$2_H2") (pintype "bidirectional"))
    )
    (net (code "524") (name "~{DF}") (class "Default")
      (node (ref "B05") (pin "A1") (pinfunction "A_A1") (pintype "input"))
      (node (ref "B12") (pin "J1") (pinfunction "IN3_J1") (pintype "input"))
      (node (ref "D11") (pin "P2") (pinfunction "1_P2") (pintype "output"))
    )
    (net (code "525") (name "~{DTB_00}") (class "Default")
      (node (ref "B02") (pin "A1") (pinfunction "A_A1") (pintype "input"))
      (node (ref "C09") (pin "F1") (pinfunction "0_F1") (pintype "output"))
    )
    (net (code "526") (name "~{DTB_01}") (class "Default")
      (node (ref "B02") (pin "B1") (pinfunction "B_B1") (pintype "input"))
      (node (ref "C09") (pin "J2") (pinfunction "0_J2") (pintype "output"))
    )
    (net (code "527") (name "~{DTB_02}") (class "Default")
      (node (ref "B02") (pin "F1") (pinfunction "A_F1") (pintype "input"))
      (node (ref "C09") (pin "M1") (pinfunction "0_M1") (pintype "output"))
    )
    (net (code "528") (name "~{DTB_03}") (class "Default")
      (node (ref "B02") (pin "H1") (pinfunction "B_H1") (pintype "input"))
      (node (ref "C09") (pin "R2") (pinfunction "0_R2") (pintype "output"))
    )
    (net (code "529") (name "~{DTB_04}") (class "Default")
      (node (ref "B02") (pin "M1") (pinfunction "A_M1") (pintype "input"))
      (node (ref "C09") (pin "U1") (pinfunction "0_U1") (pintype "output"))
    )
    (net (code "530") (name "~{DTB_05}") (class "Default")
      (node (ref "B02") (pin "N1") (pinfunction "B_N1") (pintype "input"))
      (node (ref "C09") (pin "V1") (pinfunction "0_V1") (pintype "output"))
    )
    (net (code "531") (name "~{DTB_06}") (class "Default")
      (node (ref "B02") (pin "D2") (pinfunction "A_D2") (pintype "input"))
      (node (ref "B09") (pin "F1") (pinfunction "0_F1") (pintype "output"))
    )
    (net (code "532") (name "~{DTB_07}") (class "Default")
      (node (ref "B02") (pin "E2") (pinfunction "B_E2") (pintype "input"))
      (node (ref "B09") (pin "V1") (pinfunction "0_V1") (pintype "output"))
    )
    (net (code "533") (name "~{DTB_08}") (class "Default")
      (node (ref "B02") (pin "K2") (pinfunction "A_K2") (pintype "input"))
      (node (ref "B09") (pin "M1") (pinfunction "0_M1") (pintype "output"))
    )
    (net (code "534") (name "~{DTB_09}") (class "Default")
      (node (ref "B02") (pin "L2") (pinfunction "B_L2") (pintype "input"))
      (node (ref "B09") (pin "R2") (pinfunction "0_R2") (pintype "output"))
    )
    (net (code "535") (name "~{DTB_10}") (class "Default")
      (node (ref "B02") (pin "R2") (pinfunction "A_R2") (pintype "input"))
      (node (ref "B09") (pin "U1") (pinfunction "0_U1") (pintype "output"))
    )
    (net (code "536") (name "~{DTB_11}") (class "Default")
      (node (ref "B02") (pin "S2") (pinfunction "B_S2") (pintype "input"))
      (node (ref "B09") (pin "J2") (pinfunction "0_J2") (pintype "output"))
    )
    (net (code "537") (name "~{DTF}") (class "Default")
      (node (ref "B04") (pin "L2") (pinfunction "B_L2") (pintype "input"))
      (node (ref "B12") (pin "C1") (pinfunction "IN3_C1") (pintype "input"))
      (node (ref "D11") (pin "V2") (pinfunction "1_V2") (pintype "output"))
    )
    (net (code "538") (name "~{DTSF}") (class "Default")
      (node (ref "C05") (pin "B1") (pinfunction "B1_B1") (pintype "output"))
    )
    (net (code "539") (name "~{EA_00}") (class "Default")
      (node (ref "A06") (pin "V2") (pinfunction "P$2_V2") (pintype "bidirectional"))
      (node (ref "B05") (pin "R1") (pinfunction "D_R1") (pintype "open_collector"))
      (node (ref "D06") (pin "V2") (pinfunction "P$2_V2") (pintype "bidirectional"))
    )
    (net (code "540") (name "~{EA_01}") (class "Default")
      (node (ref "A06") (pin "T2") (pinfunction "P$2_T2") (pintype "bidirectional"))
      (node (ref "B05") (pin "S1") (pinfunction "E_S1") (pintype "open_collector"))
      (node (ref "D06") (pin "T2") (pinfunction "P$2_T2") (pintype "bidirectional"))
    )
    (net (code "541") (name "~{EA_02}") (class "Default")
      (node (ref "A06") (pin "S2") (pinfunction "P$2_S2") (pintype "bidirectional"))
      (node (ref "B05") (pin "H2") (pinfunction "D_H2") (pintype "open_collector"))
      (node (ref "D06") (pin "S2") (pinfunction "P$2_S2") (pintype "bidirectional"))
    )
    (net (code "542") (name "~{EF}") (class "Default")
      (node (ref "A11") (pin "K1") (pinfunction "OUT_K1") (pintype "output"))
      (node (ref "B04") (pin "A1") (pinfunction "A_A1") (pintype "input"))
    )
    (net (code "543") (name "~{END}") (class "Default")
      (node (ref "A08") (pin "F1") (pinfunction "0_F1") (pintype "output"))
      (node (ref "A09") (pin "M2") (pinfunction "IN3_M2") (pintype "input"))
      (node (ref "B04") (pin "F1") (pinfunction "A_F1") (pintype "input"))
    )
    (net (code "544") (name "~{ENI}") (class "Default")
      (node (ref "B03") (pin "L2") (pinfunction "B_L2") (pintype "input"))
      (node (ref "C07") (pin "M1") (pinfunction "M1_M1") (pintype "output"))
    )
    (net (code "545") (name "~{FR_00}") (class "Default")
      (node (ref "B03") (pin "N1") (pinfunction "B_N1") (pintype "input"))
      (node (ref "B07") (pin "U1") (pinfunction "U1_U1") (pintype "output"))
      (node (ref "C12") (pin "K1") (pinfunction "IN1_K1") (pintype "input"))
      (node (ref "C12") (pin "P1") (pinfunction "IN1_P1") (pintype "input"))
    )
    (net (code "546") (name "~{FR_01}") (class "Default")
      (node (ref "A12") (pin "H2") (pinfunction "IN1_H2") (pintype "input"))
      (node (ref "B03") (pin "D2") (pinfunction "A_D2") (pintype "input"))
      (node (ref "B05") (pin "E2") (pinfunction "B_E2") (pintype "input"))
      (node (ref "B07") (pin "V1") (pinfunction "V1_V1") (pintype "output"))
    )
    (net (code "547") (name "~{FR_02}") (class "Default")
      (node (ref "B03") (pin "E2") (pinfunction "B_E2") (pintype "input"))
      (node (ref "C07") (pin "F1") (pinfunction "F1_F1") (pintype "output"))
    )
    (net (code "548") (name "~{FR_03}") (class "Default")
      (node (ref "B03") (pin "K2") (pinfunction "A_K2") (pintype "input"))
      (node (ref "B08") (pin "J2") (pinfunction "IN2_J2") (pintype "input"))
      (node (ref "C07") (pin "J2") (pinfunction "J2_J2") (pintype "output"))
    )
    (net (code "549") (name "~{IM_00}") (class "Default")
      (node (ref "A04") (pin "B1") (pinfunction "P$2_B1") (pintype "bidirectional"))
      (node (ref "B03") (pin "D1") (pinfunction "D_D1") (pintype "open_collector"))
      (node (ref "B04") (pin "D1") (pinfunction "D_D1") (pintype "open_collector"))
      (node (ref "D04") (pin "B1") (pinfunction "P$2_B1") (pintype "bidirectional"))
    )
    (net (code "550") (name "~{IM_01}") (class "Default")
      (node (ref "A04") (pin "D1") (pinfunction "P$2_D1") (pintype "bidirectional"))
      (node (ref "B03") (pin "E1") (pinfunction "E_E1") (pintype "open_collector"))
      (node (ref "B04") (pin "E1") (pinfunction "E_E1") (pintype "open_collector"))
      (node (ref "D04") (pin "D1") (pinfunction "P$2_D1") (pintype "bidirectional"))
    )
    (net (code "551") (name "~{IM_02}") (class "Default")
      (node (ref "A04") (pin "E1") (pinfunction "P$2_E1") (pintype "bidirectional"))
      (node (ref "B03") (pin "K1") (pinfunction "D_K1") (pintype "open_collector"))
      (node (ref "B04") (pin "K1") (pinfunction "D_K1") (pintype "open_collector"))
      (node (ref "D04") (pin "E1") (pinfunction "P$2_E1") (pintype "bidirectional"))
    )
    (net (code "552") (name "~{IM_03}") (class "Default")
      (node (ref "A04") (pin "H1") (pinfunction "P$2_H1") (pintype "bidirectional"))
      (node (ref "B03") (pin "L1") (pinfunction "E_L1") (pintype "open_collector"))
      (node (ref "B04") (pin "L1") (pinfunction "E_L1") (pintype "open_collector"))
      (node (ref "D04") (pin "H1") (pinfunction "P$2_H1") (pintype "bidirectional"))
    )
    (net (code "553") (name "~{IM_04}") (class "Default")
      (node (ref "A04") (pin "J1") (pinfunction "P$2_J1") (pintype "bidirectional"))
      (node (ref "B03") (pin "R1") (pinfunction "D_R1") (pintype "open_collector"))
      (node (ref "B04") (pin "R1") (pinfunction "D_R1") (pintype "open_collector"))
      (node (ref "D04") (pin "J1") (pinfunction "P$2_J1") (pintype "bidirectional"))
    )
    (net (code "554") (name "~{IM_05}") (class "Default")
      (node (ref "A04") (pin "L1") (pinfunction "P$2_L1") (pintype "bidirectional"))
      (node (ref "B03") (pin "S1") (pinfunction "E_S1") (pintype "open_collector"))
      (node (ref "B04") (pin "S1") (pinfunction "E_S1") (pintype "open_collector"))
      (node (ref "D04") (pin "L1") (pinfunction "P$2_L1") (pintype "bidirectional"))
    )
    (net (code "555") (name "~{IM_06}") (class "Default")
      (node (ref "A04") (pin "M1") (pinfunction "P$2_M1") (pintype "bidirectional"))
      (node (ref "B03") (pin "H2") (pinfunction "D_H2") (pintype "open_collector"))
      (node (ref "B04") (pin "H2") (pinfunction "D_H2") (pintype "open_collector"))
      (node (ref "D04") (pin "M1") (pinfunction "P$2_M1") (pintype "bidirectional"))
    )
    (net (code "556") (name "~{IM_07}") (class "Default")
      (node (ref "A04") (pin "P1") (pinfunction "P$2_P1") (pintype "bidirectional"))
      (node (ref "B03") (pin "J2") (pinfunction "E_J2") (pintype "open_collector"))
      (node (ref "B04") (pin "J2") (pinfunction "E_J2") (pintype "open_collector"))
      (node (ref "D04") (pin "P1") (pinfunction "P$2_P1") (pintype "bidirectional"))
    )
    (net (code "557") (name "~{IM_08}") (class "Default")
      (node (ref "A04") (pin "S1") (pinfunction "P$2_S1") (pintype "bidirectional"))
      (node (ref "B03") (pin "N2") (pinfunction "D_N2") (pintype "open_collector"))
      (node (ref "B04") (pin "N2") (pinfunction "D_N2") (pintype "open_collector"))
      (node (ref "D04") (pin "S1") (pinfunction "P$2_S1") (pintype "bidirectional"))
    )
    (net (code "558") (name "~{IM_09}") (class "Default")
      (node (ref "A04") (pin "D2") (pinfunction "P$2_D2") (pintype "bidirectional"))
      (node (ref "B03") (pin "P2") (pinfunction "E_P2") (pintype "open_collector"))
      (node (ref "D04") (pin "D2") (pinfunction "P$2_D2") (pintype "bidirectional"))
    )
    (net (code "559") (name "~{IM_10}") (class "Default")
      (node (ref "A04") (pin "E2") (pinfunction "P$2_E2") (pintype "bidirectional"))
      (node (ref "D04") (pin "E2") (pinfunction "P$2_E2") (pintype "bidirectional"))
    )
    (net (code "560") (name "~{IM_11}") (class "Default")
      (node (ref "A04") (pin "H2") (pinfunction "P$2_H2") (pintype "bidirectional"))
      (node (ref "B04") (pin "P2") (pinfunction "E_P2") (pintype "open_collector"))
      (node (ref "D04") (pin "H2") (pinfunction "P$2_H2") (pintype "bidirectional"))
    )
    (net (code "561") (name "~{INT_RQ}") (class "Default")
      (node (ref "A12") (pin "K1") (pinfunction "OUT_K1") (pintype "output"))
      (node (ref "B05") (pin "B1") (pinfunction "B_B1") (pintype "input"))
    )
    (net (code "562") (name "~{LDMF}") (class "Default")
      (node (ref "B08") (pin "P2") (pinfunction "IN1_P2") (pintype "input"))
      (node (ref "C05") (pin "F1") (pinfunction "F1_F1") (pintype "output"))
    )
    (net (code "563") (name "~{LPB_00}") (class "Default")
      (node (ref "D08") (pin "F1") (pinfunction "F1_F1") (pintype "output"))
      (node (ref "D10") (pin "M1") (pinfunction "IN1_M1") (pintype "input"))
    )
    (net (code "564") (name "~{LPB_01}") (class "Default")
      (node (ref "D08") (pin "M1") (pinfunction "M1_M1") (pintype "output"))
      (node (ref "D10") (pin "N1") (pinfunction "IN2_N1") (pintype "input"))
    )
    (net (code "565") (name "~{LPB_02}") (class "Default")
      (node (ref "D08") (pin "U1") (pinfunction "U1_U1") (pintype "output"))
      (node (ref "D10") (pin "P1") (pinfunction "IN3_P1") (pintype "input"))
    )
    (net (code "566") (name "~{LPB_03}") (class "Default")
      (node (ref "D08") (pin "J2") (pinfunction "J2_J2") (pintype "output"))
      (node (ref "D10") (pin "R1") (pinfunction "IN4_R1") (pintype "input"))
    )
    (net (code "567") (name "~{LPB_04}") (class "Default")
      (node (ref "D08") (pin "R2") (pinfunction "R2_R2") (pintype "output"))
      (node (ref "D10") (pin "R2") (pinfunction "IN5_R2") (pintype "input"))
    )
    (net (code "568") (name "~{LPB_05}") (class "Default")
      (node (ref "D08") (pin "V1") (pinfunction "V1_V1") (pintype "output"))
      (node (ref "D10") (pin "S2") (pinfunction "IN6_S2") (pintype "input"))
      (node (ref "D10") (pin "T2") (pinfunction "IN7_T2") (pintype "input"))
      (node (ref "D10") (pin "U2") (pinfunction "IN8_U2") (pintype "input"))
    )
    (net (code "569") (name "~{M-STOP}") (class "Default")
      (node (ref "A11") (pin "S1") (pinfunction "OUT_S1") (pintype "output"))
      (node (ref "B14") (pin "D1") (pinfunction "S_D1") (pintype "input"))
      (node (ref "C07") (pin "K2") (pinfunction "K2_K2") (pintype "input"))
      (node (ref "D14") (pin "L1") (pinfunction "M1_L1") (pintype "input"))
    )
    (net (code "570") (name "~{MB_TO_DTB}") (class "Default")
      (node (ref "D12") (pin "F1") (pinfunction "IN1_F1") (pintype "input"))
      (node (ref "D12") (pin "H1") (pinfunction "IN2_H1") (pintype "input"))
      (node (ref "D12") (pin "J1") (pinfunction "IN3_J1") (pintype "input"))
      (node (ref "D12") (pin "K1") (pinfunction "IN4_K1") (pintype "input"))
      (node (ref "D12") (pin "S1") (pinfunction "OUT_S1") (pintype "output"))
    )
    (net (code "571") (name "~{MC00}") (class "Default")
      (node (ref "A10") (pin "R1") (pinfunction "IN2_R1") (pintype "input"))
      (node (ref "B11") (pin "T2") (pinfunction "IN1_T2") (pintype "input"))
      (node (ref "B13") (pin "F1") (pinfunction "0_F1") (pintype "output"))
    )
    (net (code "572") (name "~{MC01}") (class "Default")
      (node (ref "B11") (pin "P1") (pinfunction "IN1_P1") (pintype "input"))
      (node (ref "B13") (pin "J2") (pinfunction "0_J2") (pintype "output"))
      (node (ref "C11") (pin "B1") (pinfunction "IN2_B1") (pintype "input"))
      (node (ref "D10") (pin "E2") (pinfunction "IN6_E2") (pintype "input"))
    )
    (net (code "573") (name "~{MC02}") (class "Default")
      (node (ref "B13") (pin "C1") (pinfunction "D_C1") (pintype "input"))
      (node (ref "B13") (pin "M1") (pinfunction "0_M1") (pintype "output"))
      (node (ref "D10") (pin "F2") (pinfunction "IN7_F2") (pintype "input"))
    )
    (net (code "574") (name "~{MF00}") (class "Default")
      (node (ref "B04") (pin "D2") (pinfunction "A_D2") (pintype "input"))
      (node (ref "B05") (pin "M1") (pinfunction "A_M1") (pintype "input"))
      (node (ref "D11") (pin "F1") (pinfunction "0_F1") (pintype "output"))
    )
    (net (code "575") (name "~{MF01}") (class "Default")
      (node (ref "B04") (pin "E2") (pinfunction "B_E2") (pintype "input"))
      (node (ref "B05") (pin "N1") (pinfunction "B_N1") (pintype "input"))
      (node (ref "D11") (pin "J2") (pinfunction "0_J2") (pintype "output"))
    )
    (net (code "576") (name "~{MF02}") (class "Default")
      (node (ref "B04") (pin "K2") (pinfunction "A_K2") (pintype "input"))
      (node (ref "B05") (pin "D2") (pinfunction "A_D2") (pintype "input"))
      (node (ref "D11") (pin "M1") (pinfunction "0_M1") (pintype "output"))
    )
    (net (code "577") (name "~{MKTK}") (class "Default")
      (node (ref "A08") (pin "P2") (pinfunction "1_P2") (pintype "output"))
      (node (ref "A09") (pin "K2") (pinfunction "IN1_K2") (pintype "input"))
      (node (ref "B04") (pin "B1") (pinfunction "B_B1") (pintype "input"))
    )
    (net (code "578") (name "~{MKT}") (class "Default")
      (node (ref "B10") (pin "R1") (pinfunction "IN4_R1") (pintype "input"))
      (node (ref "B13") (pin "T2") (pinfunction "D_T2") (pintype "input"))
      (node (ref "B13") (pin "V1") (pinfunction "0_V1") (pintype "output"))
      (node (ref "C14") (pin "N1") (pinfunction "C_N1") (pintype "input"))
      (node (ref "D10") (pin "H2") (pinfunction "IN8_H2") (pintype "input"))
    )
    (net (code "579") (name "~{MK_BLK_END}") (class "Default")
      (node (ref "A09") (pin "C1") (pinfunction "IN3_C1") (pintype "input"))
      (node (ref "CD18") (pin "BV1") (pinfunction "BV1_BV1") (pintype "output"))
    )
    (net (code "580") (name "~{MK_BLK_MK}") (class "Default")
      (node (ref "CD18") (pin "AD2") (pinfunction "AD2_AD2") (pintype "output"))
    )
    (net (code "581") (name "~{MK_BLK_START}") (class "Default")
      (node (ref "A09") (pin "A1") (pinfunction "IN1_A1") (pintype "input"))
      (node (ref "CD18") (pin "AF1") (pinfunction "AF1_AF1") (pintype "output"))
    )
    (net (code "582") (name "~{MK_BLK_SYNC}") (class "Default")
      (node (ref "CD18") (pin "BT2") (pinfunction "BT2_BT2") (pintype "output"))
    )
    (net (code "583") (name "~{MK_DATA_SYNC}") (class "Default")
      (node (ref "CD18") (pin "AJ1") (pinfunction "AJ1_AJ1") (pintype "output"))
    )
    (net (code "584") (name "~{MK_DATA}") (class "Default")
      (node (ref "A09") (pin "B1") (pinfunction "IN2_B1") (pintype "input"))
      (node (ref "CD18") (pin "AU2") (pinfunction "AU2_AU2") (pintype "output"))
    )
    (net (code "585") (name "~{MK_END}") (class "Default")
      (node (ref "A09") (pin "D1") (pinfunction "IN4_D1") (pintype "input"))
      (node (ref "CD18") (pin "AH2") (pinfunction "AH2_AH2") (pintype "output"))
    )
    (net (code "586") (name "~{MOVE}") (class "Default")
      (node (ref "A09") (pin "F2") (pinfunction "IN3_F2") (pintype "input"))
      (node (ref "D07") (pin "D1") (pinfunction "~{O0}_D1") (pintype "output"))
    )
    (net (code "587") (name "~{MR00}") (class "Default")
      (node (ref "B03") (pin "H1") (pinfunction "B_H1") (pintype "input"))
      (node (ref "B07") (pin "R2") (pinfunction "R2_R2") (pintype "output"))
    )
    (net (code "588") (name "~{MR01}") (class "Default")
      (node (ref "B03") (pin "M1") (pinfunction "A_M1") (pintype "input"))
      (node (ref "B14") (pin "C1") (pinfunction "D_C1") (pintype "input"))
      (node (ref "C07") (pin "R2") (pinfunction "R2_R2") (pintype "output"))
    )
    (net (code "589") (name "~{PAR}") (class "Default")
      (node (ref "A08") (pin "S1") (pinfunction "1_S1") (pintype "output"))
      (node (ref "A12") (pin "E1") (pinfunction "IN2_E1") (pintype "input"))
      (node (ref "B04") (pin "M1") (pinfunction "A_M1") (pintype "input"))
    )
    (net (code "590") (name "~{PC+ES}") (class "Default")
      (node (ref "A11") (pin "J2") (pinfunction "OUT_J2") (pintype "output"))
      (node (ref "B11") (pin "R2") (pinfunction "IN3_R2") (pintype "input"))
    )
    (net (code "591") (name "~{PWR_CLR}") (class "Default")
      (node (ref "A10") (pin "H2") (pinfunction "IN1_H2") (pintype "input"))
      (node (ref "A10") (pin "M2") (pinfunction "IN2_M2") (pintype "input"))
      (node (ref "A12") (pin "A1") (pinfunction "IN1_A1") (pintype "input"))
      (node (ref "A23") (pin "M1") (pinfunction "A_M1") (pintype "input"))
      (node (ref "B08") (pin "U2") (pinfunction "IN2_U2") (pintype "input"))
      (node (ref "C05") (pin "K1") (pinfunction "OUT_K1") (pintype "output"))
      (node (ref "C06") (pin "P2") (pinfunction "IN_P2") (pintype "input"))
      (node (ref "C11") (pin "U2") (pinfunction "IN2_U2") (pintype "input"))
      (node (ref "C14") (pin "R1") (pinfunction "S_R1") (pintype "input"))
      (node (ref "D11") (pin "A1") (pinfunction "R_A1") (pintype "input"))
    )
    (net (code "592") (name "~{RDD_00}") (class "Default")
      (node (ref "A21") (pin "V2") (pinfunction "V2_V2") (pintype "output"))
    )
    (net (code "593") (name "~{RDD_01}") (class "Default")
      (node (ref "B20") (pin "V2") (pinfunction "V2_V2") (pintype "output"))
    )
    (net (code "594") (name "~{RDD_02}") (class "Default")
      (node (ref "A20") (pin "V2") (pinfunction "V2_V2") (pintype "output"))
    )
    (net (code "595") (name "~{RDMK}") (class "Default")
      (node (ref "B18") (pin "V2") (pinfunction "V2_V2") (pintype "output"))
    )
    (net (code "596") (name "~{READ_ALL}") (class "Default")
      (node (ref "C11") (pin "M1") (pinfunction "IN2_M1") (pintype "input"))
      (node (ref "D07") (pin "N1") (pinfunction "~{O3}_N1") (pintype "output"))
    )
    (net (code "597") (name "~{READ_DATA}") (class "Default")
      (node (ref "B08") (pin "L2") (pinfunction "IN1_L2") (pintype "input"))
      (node (ref "B11") (pin "J2") (pinfunction "IN1_J2") (pintype "input"))
      (node (ref "D07") (pin "J1") (pinfunction "~{O2}_J1") (pintype "output"))
    )
    (net (code "598") (name "~{RSTA}") (class "Default")
      (node (ref "B03") (pin "C1") (pinfunction "C_C1") (pintype "input"))
      (node (ref "B03") (pin "F2") (pinfunction "C_F2") (pintype "input"))
      (node (ref "B03") (pin "J1") (pinfunction "C_J1") (pintype "input"))
      (node (ref "B03") (pin "M2") (pinfunction "C_M2") (pintype "input"))
      (node (ref "B03") (pin "P1") (pinfunction "C_P1") (pintype "input"))
      (node (ref "C04") (pin "B1") (pinfunction "B1_B1") (pintype "output"))
    )
    (net (code "599") (name "~{RSTB}") (class "Default")
      (node (ref "B04") (pin "C1") (pinfunction "C_C1") (pintype "input"))
      (node (ref "B04") (pin "F2") (pinfunction "C_F2") (pintype "input"))
      (node (ref "B04") (pin "J1") (pinfunction "C_J1") (pintype "input"))
      (node (ref "B04") (pin "M2") (pinfunction "C_M2") (pintype "input"))
      (node (ref "B04") (pin "P1") (pinfunction "C_P1") (pintype "input"))
      (node (ref "C05") (pin "D1") (pinfunction "D1_D1") (pintype "output"))
    )
    (net (code "600") (name "~{SEARCH}") (class "Default")
      (node (ref "B05") (pin "K2") (pinfunction "A_K2") (pintype "input"))
      (node (ref "B11") (pin "K2") (pinfunction "IN2_K2") (pintype "input"))
      (node (ref "D07") (pin "E1") (pinfunction "~{O1}_E1") (pintype "output"))
    )
    (net (code "601") (name "~{SEL}") (class "Default")
      (node (ref "A08") (pin "J2") (pinfunction "0_J2") (pintype "output"))
      (node (ref "A09") (pin "N2") (pinfunction "IN4_N2") (pintype "input"))
      (node (ref "B04") (pin "H1") (pinfunction "B_H1") (pintype "input"))
    )
    (net (code "602") (name "~{SE}") (class "Default")
      (node (ref "A09") (pin "H1") (pinfunction "IN2_H1") (pintype "input"))
      (node (ref "D07") (pin "L1") (pinfunction "~{O7}_L1") (pintype "output"))
    )
    (net (code "603") (name "~{SH_EN}") (class "Default")
      (node (ref "A11") (pin "M2") (pinfunction "IN_M2") (pintype "input"))
      (node (ref "A12") (pin "V2") (pinfunction "OUT_V2") (pintype "output"))
      (node (ref "C10") (pin "C1") (pinfunction "IN2A_C1") (pintype "input"))
      (node (ref "C10") (pin "J1") (pinfunction "IN2A_J1") (pintype "input"))
      (node (ref "C10") (pin "P1") (pinfunction "IN2A_P1") (pintype "input"))
    )
    (net (code "604") (name "~{SKP_RQ}") (class "Default")
      (node (ref "A12") (pin "S1") (pinfunction "OUT_S1") (pintype "output"))
      (node (ref "B05") (pin "F1") (pinfunction "A_F1") (pintype "input"))
    )
    (net (code "605") (name "~{SP_DY}") (class "Default")
      (node (ref "C14") (pin "M2") (pinfunction "D_M2") (pintype "input"))
      (node (ref "D14") (pin "F2") (pinfunction "F2_F2") (pintype "output"))
    )
    (net (code "606") (name "~{ST_BLK_MK}") (class "Default")
      (node (ref "A09") (pin "D2") (pinfunction "IN1_D2") (pintype "input"))
      (node (ref "A09") (pin "M1") (pinfunction "IN1_M1") (pintype "input"))
      (node (ref "C13") (pin "F2") (pinfunction "OUT_F2") (pintype "output"))
    )
    (net (code "607") (name "~{ST_CK_0P}") (class "Default")
      (node (ref "C13") (pin "A1") (pinfunction "IN_A1") (pintype "input"))
      (node (ref "D17") (pin "L2") (pinfunction "F2_L2") (pintype "output"))
    )
    (net (code "608") (name "~{ST_CK}") (class "Default")
      (node (ref "C13") (pin "K1") (pinfunction "OUT_K1") (pintype "output"))
      (node (ref "C16") (pin "E2") (pinfunction "IN2_E2") (pintype "input"))
    )
    (net (code "609") (name "~{ST_DATA}") (class "Default")
      (node (ref "C13") (pin "J2") (pinfunction "OUT_J2") (pintype "output"))
    )
    (net (code "610") (name "~{ST_FINAL}") (class "Default")
      (node (ref "C11") (pin "M2") (pinfunction "IN2_M2") (pintype "input"))
      (node (ref "C13") (pin "M1") (pinfunction "OUT_M1") (pintype "output"))
      (node (ref "C16") (pin "F2") (pinfunction "IN3_F2") (pintype "input"))
    )
    (net (code "611") (name "~{ST_IDLE}") (class "Default")
      (node (ref "A09") (pin "E2") (pinfunction "IN2_E2") (pintype "input"))
      (node (ref "A09") (pin "N1") (pinfunction "IN2_N1") (pintype "input"))
      (node (ref "C13") (pin "L2") (pinfunction "OUT_L2") (pintype "output"))
    )
    (net (code "612") (name "~{ST_REV_CK}") (class "Default")
      (node (ref "C13") (pin "E1") (pinfunction "OUT_E1") (pintype "output"))
    )
    (net (code "613") (name "~{SWTM}") (class "Default")
      (node (ref "B06") (pin "R2") (pinfunction "OUT_R2") (pintype "output"))
      (node (ref "C10") (pin "L2") (pinfunction "IN1B_L2") (pintype "input"))
    )
    (net (code "614") (name "~{SYNC-P}") (class "Default")
      (node (ref "B10") (pin "J2") (pinfunction "OUT_J2") (pintype "output"))
      (node (ref "B13") (pin "A1") (pinfunction "R_A1") (pintype "input"))
      (node (ref "B13") (pin "K2") (pinfunction "R_K2") (pintype "input"))
    )
    (net (code "615") (name "~{SYNC}") (class "Default")
      (node (ref "CD18") (pin "BM2") (pinfunction "BM2_BM2") (pintype "output"))
    )
    (net (code "616") (name "~{TIM}") (class "Default")
      (node (ref "A08") (pin "M1") (pinfunction "0_M1") (pintype "output"))
      (node (ref "A09") (pin "L2") (pinfunction "IN2_L2") (pintype "input"))
      (node (ref "B04") (pin "N1") (pinfunction "B_N1") (pintype "input"))
    )
    (net (code "617") (name "~{TM_EN}") (class "Default")
      (node (ref "B15") (pin "D1") (pinfunction "IN1_D1") (pintype "input"))
      (node (ref "B15") (pin "D2") (pinfunction "IN1_D2") (pintype "input"))
      (node (ref "C12") (pin "C1") (pinfunction "IN3_C1") (pintype "input"))
      (node (ref "C12") (pin "K2") (pinfunction "IN2_K2") (pintype "input"))
      (node (ref "C13") (pin "P1") (pinfunction "OUT_P1") (pintype "output"))
      (node (ref "D15") (pin "J2") (pinfunction "J2_J2") (pintype "input"))
      (node (ref "D15") (pin "K2") (pinfunction "K2_K2") (pintype "input"))
    )
    (net (code "618") (name "~{TP00_A}") (class "Default")
      (node (ref "A15") (pin "M1") (pinfunction "IN1_M1") (pintype "input"))
      (node (ref "A15") (pin "N1") (pinfunction "IN2_N1") (pintype "input"))
      (node (ref "A15") (pin "P1") (pinfunction "IN3_P1") (pintype "input"))
      (node (ref "A15") (pin "R1") (pinfunction "IN4_R1") (pintype "input"))
      (node (ref "A16") (pin "L2") (pinfunction "F2_L2") (pintype "output"))
    )
    (net (code "619") (name "~{TP0_XTLK_DY}") (class "Default")
      (node (ref "A11") (pin "R2") (pinfunction "OUT_R2") (pintype "output"))
      (node (ref "A15") (pin "F2") (pinfunction "IN3_F2") (pintype "input"))
      (node (ref "A16") (pin "J2") (pinfunction "J2_J2") (pintype "input"))
      (node (ref "A16") (pin "K2") (pinfunction "K2_K2") (pintype "input"))
    )
    (net (code "620") (name "~{TP00}") (class "Default")
      (node (ref "A15") (pin "E1") (pinfunction "OUT_E1") (pintype "output"))
      (node (ref "A15") (pin "F1") (pinfunction "IN1_F1") (pintype "input"))
      (node (ref "A15") (pin "H1") (pinfunction "IN2_H1") (pintype "input"))
      (node (ref "A15") (pin "J1") (pinfunction "IN3_J1") (pintype "input"))
      (node (ref "A15") (pin "K1") (pinfunction "IN4_K1") (pintype "input"))
      (node (ref "B13") (pin "N1") (pinfunction "C_N1") (pintype "input"))
      (node (ref "CD18") (pin "AN1") (pinfunction "AN1_AN1") (pintype "input"))
    )
    (net (code "621") (name "~{TP01_A}") (class "Default")
      (node (ref "A15") (pin "R2") (pinfunction "IN1_R2") (pintype "input"))
      (node (ref "A15") (pin "S2") (pinfunction "IN2_S2") (pintype "input"))
      (node (ref "A15") (pin "T2") (pinfunction "IN3_T2") (pintype "input"))
      (node (ref "A15") (pin "U2") (pinfunction "IN4_U2") (pintype "input"))
      (node (ref "B16") (pin "L2") (pinfunction "F2_L2") (pintype "output"))
    )
    (net (code "622") (name "~{TP1_XTLK_DY}") (class "Default")
      (node (ref "A11") (pin "V2") (pinfunction "OUT_V2") (pintype "output"))
      (node (ref "A15") (pin "B1") (pinfunction "IN2_B1") (pintype "input"))
      (node (ref "B16") (pin "H2") (pinfunction "H2_H2") (pintype "input"))
      (node (ref "B16") (pin "J2") (pinfunction "J2_J2") (pintype "input"))
    )
    (net (code "623") (name "~{TP01}") (class "Default")
      (node (ref "A15") (pin "J2") (pinfunction "OUT_J2") (pintype "output"))
      (node (ref "A15") (pin "K2") (pinfunction "IN1_K2") (pintype "input"))
      (node (ref "A15") (pin "L2") (pinfunction "IN2_L2") (pintype "input"))
      (node (ref "A15") (pin "M2") (pinfunction "IN3_M2") (pintype "input"))
      (node (ref "A15") (pin "N2") (pinfunction "IN4_N2") (pintype "input"))
      (node (ref "B13") (pin "L2") (pinfunction "C_L2") (pintype "input"))
    )
    (net (code "624") (name "~{TS03}") (class "Default")
      (node (ref "C04") (pin "K1") (pinfunction "OUT_K1") (pintype "output"))
      (node (ref "D17") (pin "H2") (pinfunction "H2_H2") (pintype "input"))
      (node (ref "D17") (pin "J2") (pinfunction "J2_J2") (pintype "input"))
      (node (ref "D17") (pin "K2") (pinfunction "K2_K2") (pintype "input"))
    )
    (net (code "625") (name "~{T_00}") (class "Default")
      (node (ref "A24") (pin "V2") (pinfunction "P$2_V2") (pintype "bidirectional"))
      (node (ref "B22") (pin "V2") (pinfunction "E_V2") (pintype "output"))
      (node (ref "B23") (pin "V2") (pinfunction "P$1_V2") (pintype "passive"))
    )
    (net (code "626") (name "~{T_01}") (class "Default")
      (node (ref "A23") (pin "S1") (pinfunction "E_S1") (pintype "output"))
      (node (ref "A24") (pin "M2") (pinfunction "P$2_M2") (pintype "bidirectional"))
      (node (ref "B23") (pin "M2") (pinfunction "P$1_M2") (pintype "passive"))
    )
    (net (code "627") (name "~{T_02}") (class "Default")
      (node (ref "A23") (pin "H2") (pinfunction "D_H2") (pintype "output"))
      (node (ref "A24") (pin "N2") (pinfunction "P$2_N2") (pintype "bidirectional"))
      (node (ref "B23") (pin "N2") (pinfunction "P$1_N2") (pintype "passive"))
    )
    (net (code "628") (name "~{T_03}") (class "Default")
      (node (ref "A23") (pin "J2") (pinfunction "E_J2") (pintype "output"))
      (node (ref "A24") (pin "P2") (pinfunction "P$2_P2") (pintype "bidirectional"))
      (node (ref "B23") (pin "P2") (pinfunction "P$1_P2") (pintype "passive"))
    )
    (net (code "629") (name "~{T_04}") (class "Default")
      (node (ref "A23") (pin "N2") (pinfunction "D_N2") (pintype "output"))
      (node (ref "A24") (pin "R2") (pinfunction "P$2_R2") (pintype "bidirectional"))
      (node (ref "B23") (pin "R2") (pinfunction "P$1_R2") (pintype "passive"))
    )
    (net (code "630") (name "~{T_05}") (class "Default")
      (node (ref "A23") (pin "P2") (pinfunction "E_P2") (pintype "output"))
      (node (ref "A24") (pin "S2") (pinfunction "P$2_S2") (pintype "bidirectional"))
      (node (ref "B23") (pin "S2") (pinfunction "P$1_S2") (pintype "passive"))
    )
    (net (code "631") (name "~{T_06}") (class "Default")
      (node (ref "A23") (pin "U2") (pinfunction "D_U2") (pintype "output"))
      (node (ref "A24") (pin "T2") (pinfunction "P$2_T2") (pintype "bidirectional"))
      (node (ref "B23") (pin "T2") (pinfunction "P$1_T2") (pintype "passive"))
    )
    (net (code "632") (name "~{T_07}") (class "Default")
      (node (ref "A23") (pin "V2") (pinfunction "E_V2") (pintype "output"))
      (node (ref "A24") (pin "U2") (pinfunction "P$2_U2") (pintype "bidirectional"))
      (node (ref "B23") (pin "U2") (pinfunction "P$1_U2") (pintype "passive"))
    )
    (net (code "633") (name "~{T_FWD}") (class "Default")
      (node (ref "A23") (pin "K1") (pinfunction "D_K1") (pintype "output"))
      (node (ref "A24") (pin "E2") (pinfunction "P$2_E2") (pintype "bidirectional"))
      (node (ref "B23") (pin "H2") (pinfunction "P$1_H2") (pintype "passive"))
    )
    (net (code "634") (name "~{T_GO}") (class "Default")
      (node (ref "A23") (pin "D1") (pinfunction "D_D1") (pintype "output"))
      (node (ref "A24") (pin "C2") (pinfunction "P$2_C2") (pintype "bidirectional"))
      (node (ref "B23") (pin "D2") (pinfunction "P$1_D2") (pintype "passive"))
    )
    (net (code "635") (name "~{T_PWR_CLR}") (class "Default")
      (node (ref "A23") (pin "R1") (pinfunction "D_R1") (pintype "output"))
      (node (ref "A24") (pin "H2") (pinfunction "P$2_H2") (pintype "bidirectional"))
      (node (ref "B23") (pin "K2") (pinfunction "P$1_K2") (pintype "passive"))
    )
    (net (code "636") (name "~{T_REV}") (class "Default")
      (node (ref "A23") (pin "L1") (pinfunction "E_L1") (pintype "output"))
      (node (ref "A24") (pin "F2") (pinfunction "P$2_F2") (pintype "bidirectional"))
      (node (ref "B23") (pin "J2") (pinfunction "P$1_J2") (pintype "passive"))
    )
    (net (code "637") (name "~{T_SINGLE_UNIT}") (class "Default")
      (node (ref "A24") (pin "K2") (pinfunction "P$2_K2") (pintype "bidirectional"))
      (node (ref "B21") (pin "T2") (pinfunction "IN_T2") (pintype "input"))
    )
    (net (code "638") (name "~{T_STOP}") (class "Default")
      (node (ref "A23") (pin "E1") (pinfunction "E_E1") (pintype "output"))
      (node (ref "A24") (pin "D2") (pinfunction "P$2_D2") (pintype "bidirectional"))
      (node (ref "B23") (pin "E2") (pinfunction "P$1_E2") (pintype "passive"))
    )
    (net (code "639") (name "~{T_TRK}") (class "Default")
      (node (ref "A18") (pin "V2") (pinfunction "V2_V2") (pintype "output"))
      (node (ref "B15") (pin "E1") (pinfunction "IN2_E1") (pintype "input"))
    )
    (net (code "640") (name "~{T_WRITE_OK}") (class "Default")
      (node (ref "A22") (pin "H2") (pinfunction "H2_H2") (pintype "input"))
      (node (ref "A24") (pin "L2") (pinfunction "P$2_L2") (pintype "bidirectional"))
      (node (ref "B23") (pin "L2") (pinfunction "P$1_L2") (pintype "passive"))
    )
    (net (code "641") (name "~{U+M_DY}") (class "Default")
      (node (ref "C12") (pin "A1") (pinfunction "IN1_A1") (pintype "input"))
      (node (ref "C12") (pin "R2") (pinfunction "IN3_R2") (pintype "input"))
      (node (ref "D14") (pin "E2") (pinfunction "F2_E2") (pintype "output"))
      (node (ref "D14") (pin "N1") (pinfunction "N1_N1") (pintype "input"))
    )
    (net (code "642") (name "~{USR_00}") (class "Default")
      (node (ref "B03") (pin "A1") (pinfunction "A_A1") (pintype "input"))
      (node (ref "B07") (pin "F1") (pinfunction "F1_F1") (pintype "output"))
    )
    (net (code "643") (name "~{USR_01}") (class "Default")
      (node (ref "B03") (pin "B1") (pinfunction "B_B1") (pintype "input"))
      (node (ref "B07") (pin "J2") (pinfunction "J2_J2") (pintype "output"))
    )
    (net (code "644") (name "~{USR_02}") (class "Default")
      (node (ref "B03") (pin "F1") (pinfunction "A_F1") (pintype "input"))
      (node (ref "B07") (pin "M1") (pinfunction "M1_M1") (pintype "output"))
    )
    (net (code "645") (name "~{UTS}") (class "Default")
      (node (ref "C12") (pin "L2") (pinfunction "IN3_L2") (pintype "input"))
      (node (ref "C14") (pin "P2") (pinfunction "1_P2") (pintype "output"))
      (node (ref "C15") (pin "P2") (pinfunction "IN1_P2") (pintype "input"))
      (node (ref "C16") (pin "A1") (pinfunction "IN1_A1") (pintype "input"))
      (node (ref "C16") (pin "B1") (pinfunction "IN2_B1") (pintype "input"))
      (node (ref "C16") (pin "C1") (pinfunction "IN3_C1") (pintype "input"))
      (node (ref "C16") (pin "D1") (pinfunction "IN4_D1") (pintype "input"))
      (node (ref "C16") (pin "F1") (pinfunction "IN1_F1") (pintype "input"))
      (node (ref "C16") (pin "H1") (pinfunction "IN2_H1") (pintype "input"))
      (node (ref "C16") (pin "J1") (pinfunction "IN3_J1") (pintype "input"))
      (node (ref "C16") (pin "K1") (pinfunction "IN4_K1") (pintype "input"))
    )
    (net (code "646") (name "~{W-INH}") (class "Default")
      (node (ref "A08") (pin "V2") (pinfunction "1_V2") (pintype "output"))
      (node (ref "B11") (pin "L1") (pinfunction "IN2_L1") (pintype "input"))
      (node (ref "B12") (pin "H1") (pinfunction "IN2_H1") (pintype "input"))
    )
    (net (code "647") (name "~{WB00}") (class "Default")
      (node (ref "A21") (pin "P2") (pinfunction "P2_P2") (pintype "input"))
      (node (ref "B18") (pin "P2") (pinfunction "P2_P2") (pintype "input"))
      (node (ref "C10") (pin "D1") (pinfunction "IN2B_D1") (pintype "input"))
      (node (ref "C14") (pin "E1") (pinfunction "1_E1") (pintype "output"))
    )
    (net (code "648") (name "~{WB01}") (class "Default")
      (node (ref "B20") (pin "P2") (pinfunction "P2_P2") (pintype "input"))
      (node (ref "C10") (pin "K1") (pinfunction "IN2B_K1") (pintype "input"))
      (node (ref "C14") (pin "H2") (pinfunction "1_H2") (pintype "output"))
    )
    (net (code "649") (name "~{WB02}") (class "Default")
      (node (ref "A20") (pin "P2") (pinfunction "P2_P2") (pintype "input"))
      (node (ref "C10") (pin "R1") (pinfunction "IN2B_R1") (pintype "input"))
      (node (ref "C14") (pin "L1") (pinfunction "1_L1") (pintype "output"))
    )
    (net (code "650") (name "~{WC0}") (class "Default")
      (node (ref "C06") (pin "N2") (pinfunction "OUT_N2") (pintype "output"))
      (node (ref "D11") (pin "R1") (pinfunction "S_R1") (pintype "input"))
    )
    (net (code "651") (name "~{WC}") (class "Default")
      (node (ref "B12") (pin "F2") (pinfunction "IN3_F2") (pintype "input"))
      (node (ref "C12") (pin "T2") (pinfunction "IN1_T2") (pintype "input"))
      (node (ref "D11") (pin "M2") (pinfunction "D_M2") (pintype "input"))
      (node (ref "D11") (pin "U1") (pinfunction "0_U1") (pintype "output"))
    )
    (net (code "652") (name "~{WRITE_ALL}") (class "Default")
      (node (ref "D07") (pin "M1") (pinfunction "~{O5}_M1") (pintype "output"))
    )
    (net (code "653") (name "~{WRITE_DATA}") (class "Default")
      (node (ref "B08") (pin "M2") (pinfunction "IN2_M2") (pintype "input"))
      (node (ref "D07") (pin "F1") (pinfunction "~{O4}_F1") (pintype "output"))
    )
    (net (code "654") (name "~{WRITE_OK}") (class "Default")
      (node (ref "A10") (pin "J1") (pinfunction "IN2_J1") (pintype "input"))
      (node (ref "C17") (pin "J2") (pinfunction "OUT_J2") (pintype "output"))
    )
    (net (code "655") (name "~{WRTM}") (class "Default")
      (node (ref "B08") (pin "H2") (pinfunction "IN1_H2") (pintype "input"))
      (node (ref "C10") (pin "M2") (pinfunction "IN2A_M2") (pintype "input"))
      (node (ref "D07") (pin "H1") (pinfunction "~{O6}_H1") (pintype "output"))
    )
    (net (code "656") (name "~{WR_EN}") (class "Default")
      (node (ref "B11") (pin "F1") (pinfunction "IN2_F1") (pintype "input"))
      (node (ref "C11") (pin "H2") (pinfunction "IN1_H2") (pintype "input"))
      (node (ref "C12") (pin "J2") (pinfunction "IN1_J2") (pintype "input"))
      (node (ref "C14") (pin "S1") (pinfunction "1_S1") (pintype "output"))
      (node (ref "C15") (pin "D2") (pinfunction "IN1_D2") (pintype "input"))
      (node (ref "C15") (pin "H2") (pinfunction "IN1_H2") (pintype "input"))
    )
    (net (code "657") (name "~{XSAD}") (class "Default")
      (node (ref "A11") (pin "K2") (pinfunction "IN_K2") (pintype "input"))
      (node (ref "D13") (pin "L2") (pinfunction "F2_L2") (pintype "output"))
    )
    (net (code "658") (name "~{XSTA}") (class "Default")
      (node (ref "B08") (pin "R2") (pinfunction "IN2_R2") (pintype "input"))
      (node (ref "C04") (pin "F1") (pinfunction "F1_F1") (pintype "output"))
      (node (ref "D13") (pin "H2") (pinfunction "H2_H2") (pintype "input"))
      (node (ref "D13") (pin "J2") (pinfunction "J2_J2") (pintype "input"))
      (node (ref "D13") (pin "K2") (pinfunction "K2_K2") (pintype "input"))
      (node (ref "D14") (pin "K2") (pinfunction "U1_K2") (pintype "input"))
      (node (ref "D14") (pin "L2") (pinfunction "S1_L2") (pintype "input"))
      (node (ref "D16") (pin "M2") (pinfunction "H2_M2") (pintype "input"))
      (node (ref "D16") (pin "N2") (pinfunction "J2_N2") (pintype "input"))
    )
  )
)
